# SMPS.net
KiCad netlist of a schematic drawn in Altium Designer
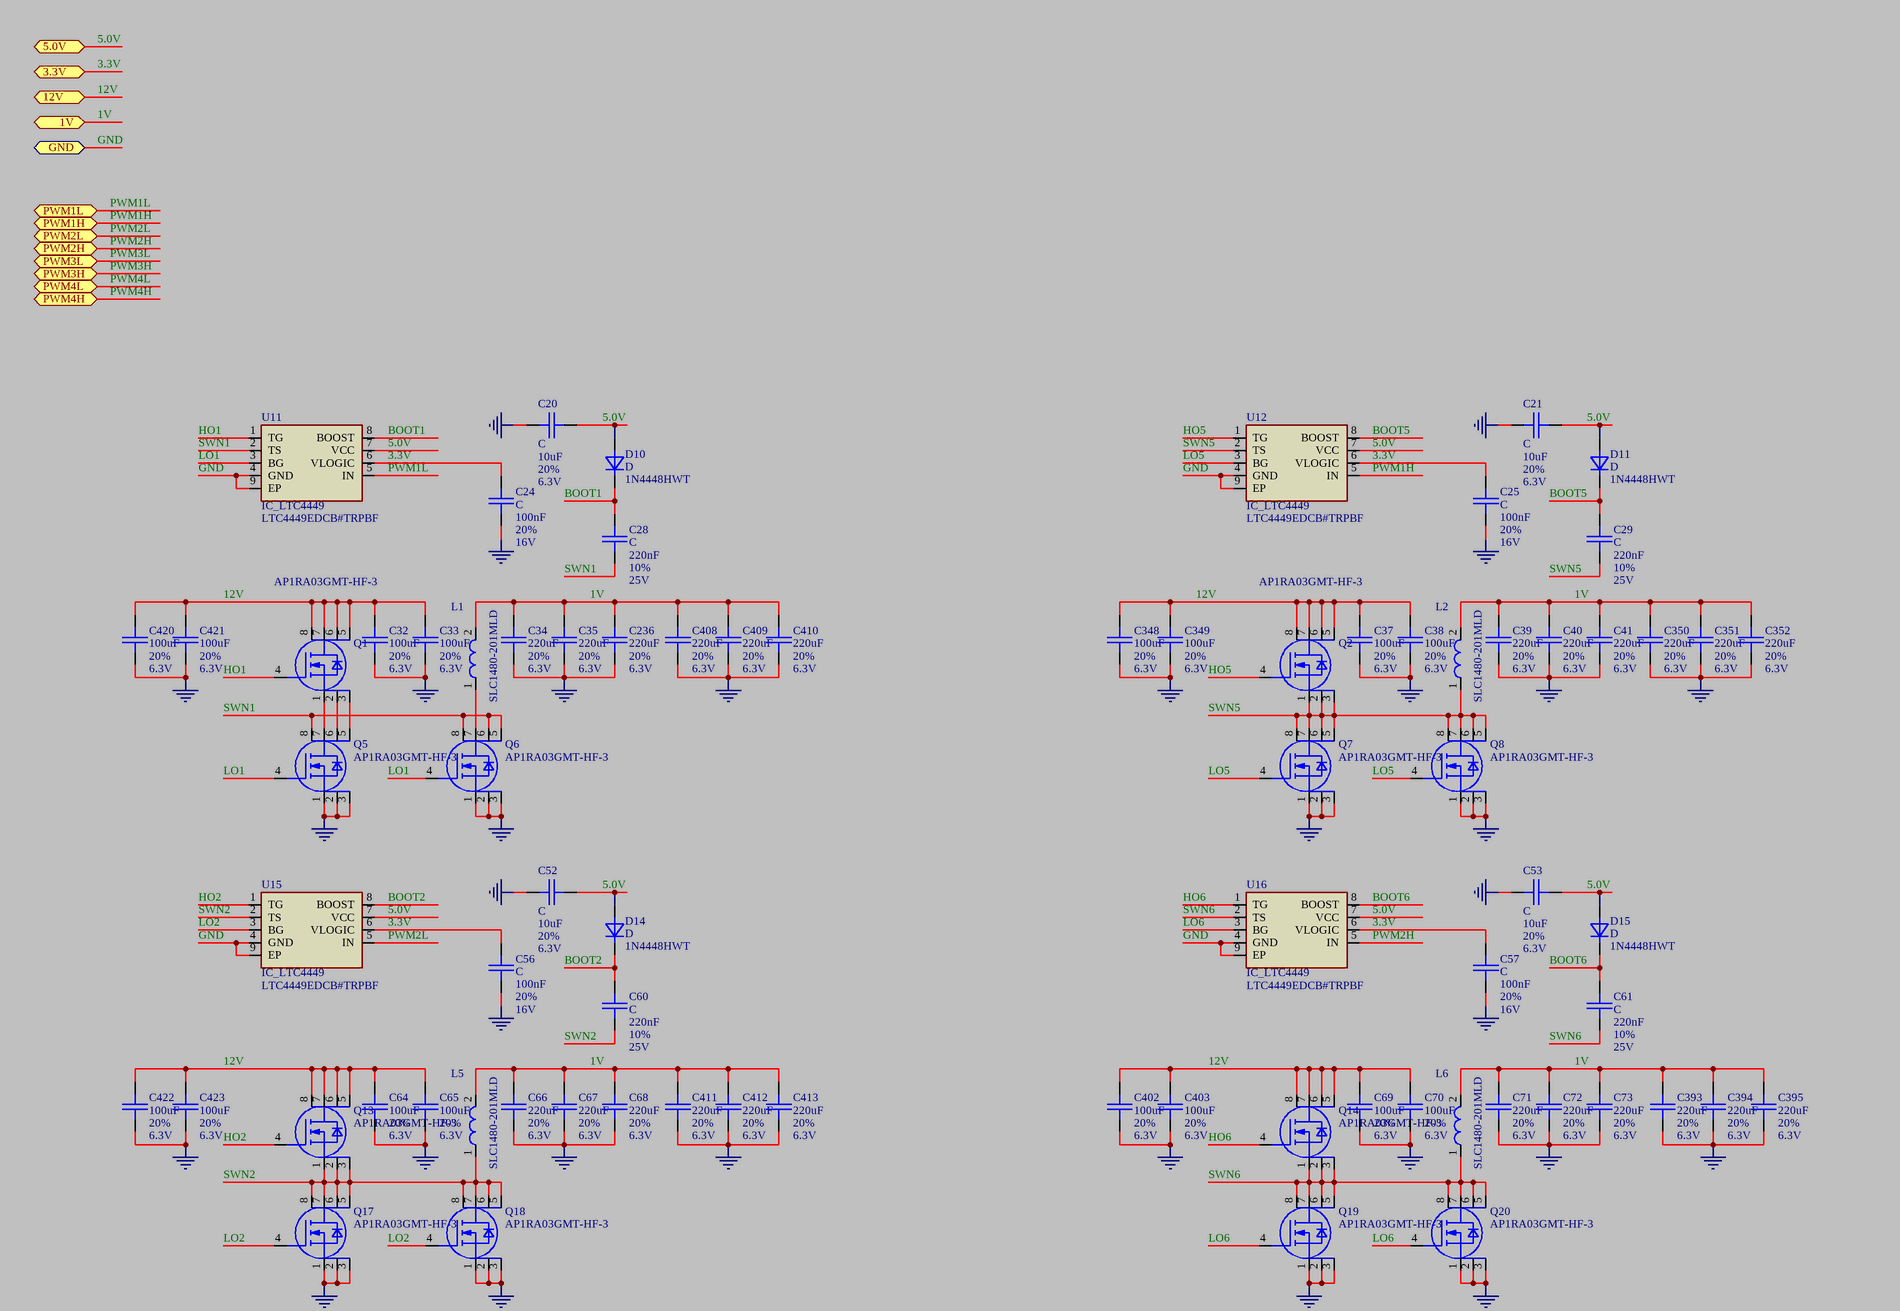
[diagram p0: SMPS.SchDoc, top left]
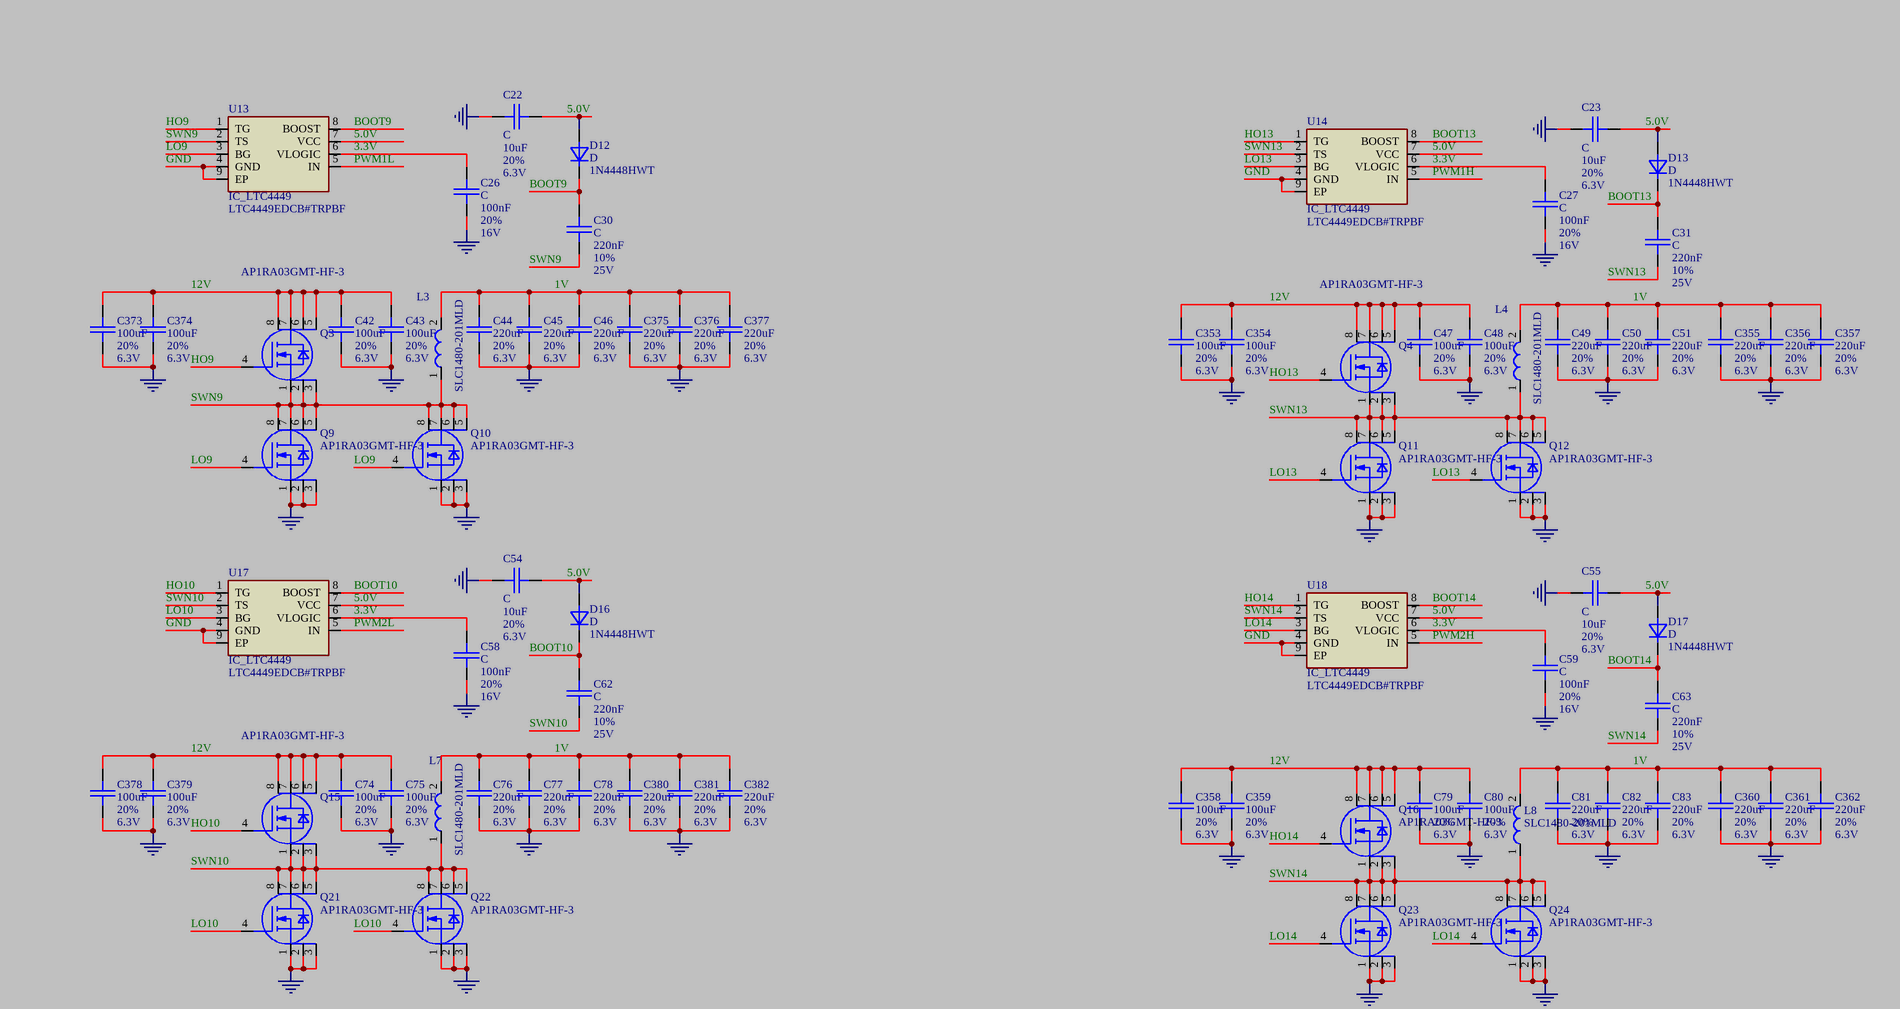
[diagram p1: SMPS.SchDoc, top right]
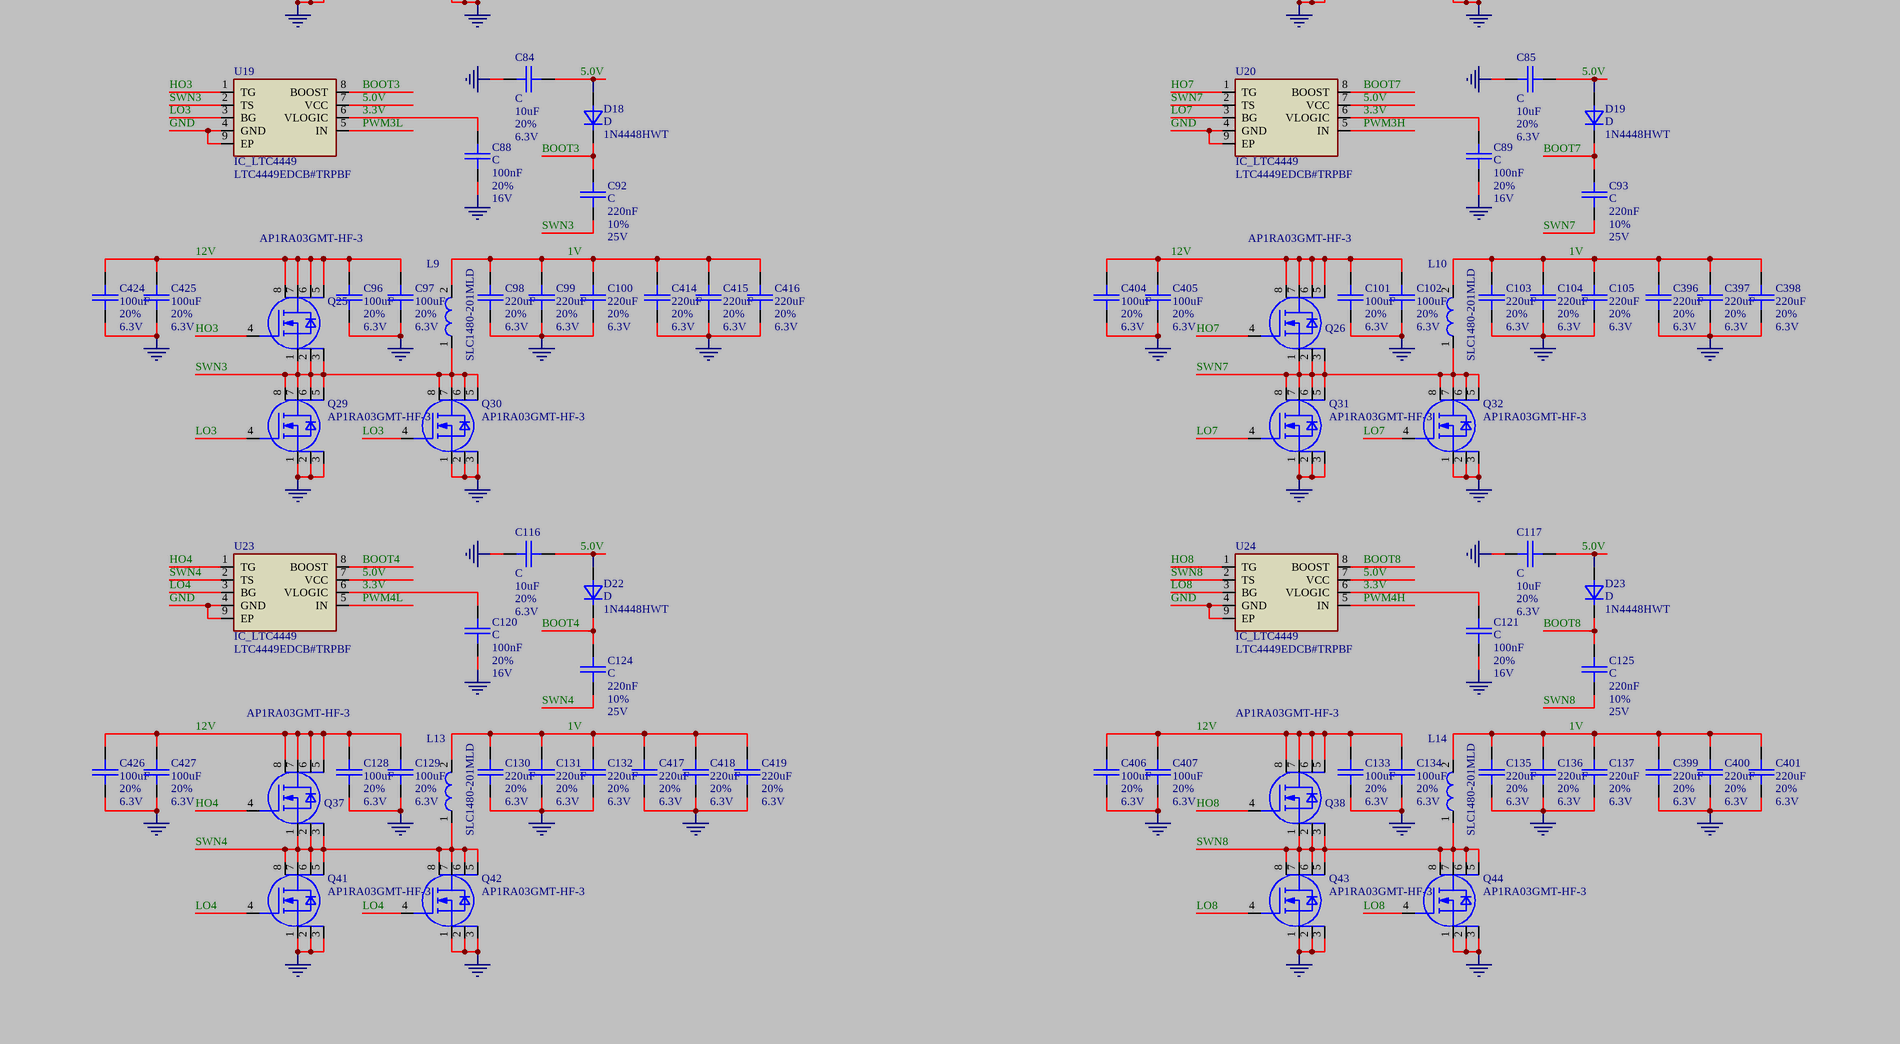
[diagram p2: SMPS.SchDoc, bottom left]
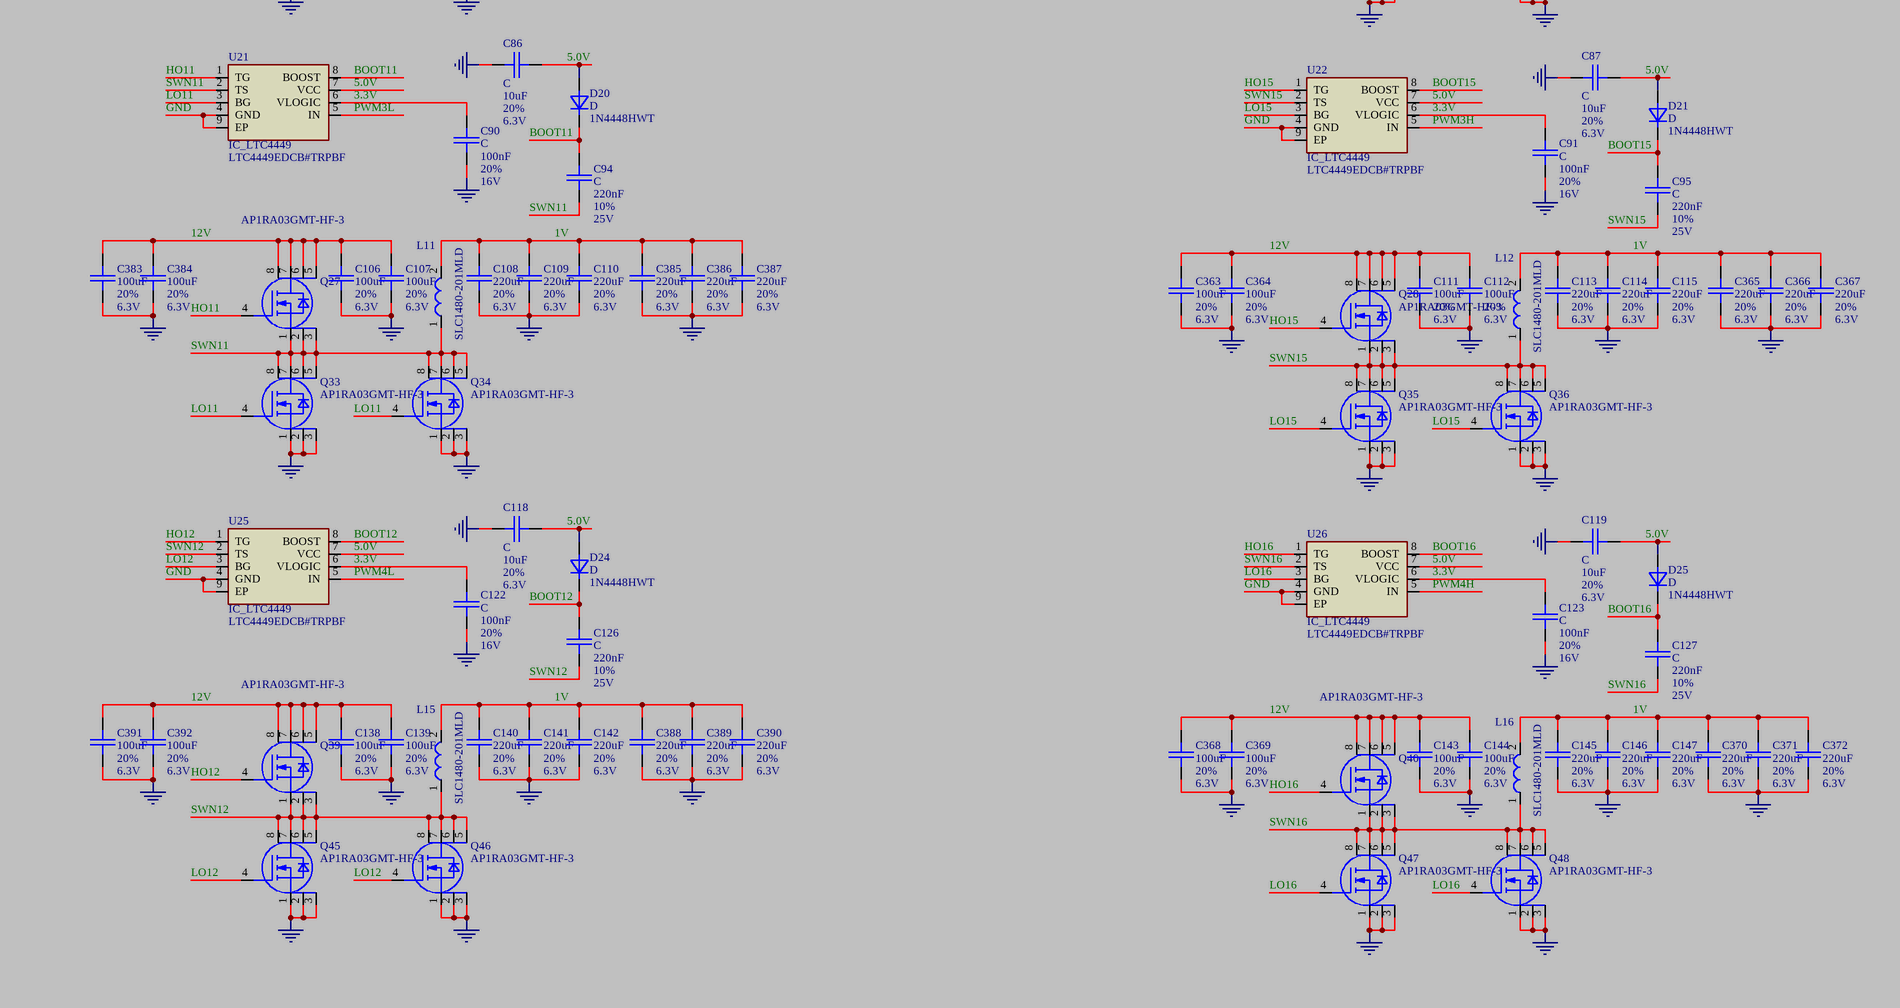
[diagram p3: SMPS.SchDoc, bottom right]

(export (version "E")
  (design (tool "Eeschema 10.0.6"))
  (components
    (comp (ref "C20")
      (value "C")
      (footprint "SMD_0603_CAPC1608X95N")
      (fields
        (field (name "DB_PART_NUMBER") "CAP000043646")
        (field (name "DB_VALUE") "10uF")
        (field (name "DB_TOLERANCE") "20%")
        (field (name "DB_VOLTAGE") "6.3V")
        (field (name "DB_MANUFACTURER_PART") "KEMET    C0603C106M9PAC")
      )
      (libsource (lib "Database_Libs1") (part "C"))
    )
    (comp (ref "C21")
      (value "C")
      (footprint "SMD_0603_CAPC1608X95N")
      (fields
        (field (name "DB_PART_NUMBER") "CAP000043646")
        (field (name "DB_VALUE") "10uF")
        (field (name "DB_TOLERANCE") "20%")
        (field (name "DB_VOLTAGE") "6.3V")
        (field (name "DB_MANUFACTURER_PART") "KEMET    C0603C106M9PAC")
      )
      (libsource (lib "Database_Libs1") (part "C"))
    )
    (comp (ref "C22")
      (value "C")
      (footprint "SMD_0603_CAPC1608X95N")
      (fields
        (field (name "DB_PART_NUMBER") "CAP000043646")
        (field (name "DB_VALUE") "10uF")
        (field (name "DB_TOLERANCE") "20%")
        (field (name "DB_VOLTAGE") "6.3V")
        (field (name "DB_MANUFACTURER_PART") "KEMET    C0603C106M9PAC")
      )
      (libsource (lib "Database_Libs1") (part "C"))
    )
    (comp (ref "C23")
      (value "C")
      (footprint "SMD_0603_CAPC1608X95N")
      (fields
        (field (name "DB_PART_NUMBER") "CAP000043646")
        (field (name "DB_VALUE") "10uF")
        (field (name "DB_TOLERANCE") "20%")
        (field (name "DB_VOLTAGE") "6.3V")
        (field (name "DB_MANUFACTURER_PART") "KEMET    C0603C106M9PAC")
      )
      (libsource (lib "Database_Libs1") (part "C"))
    )
    (comp (ref "C24")
      (value "C")
      (footprint "SMD_0402_CAPC1005X55N")
      (fields
        (field (name "DB_PART_NUMBER") "CAP000022751")
        (field (name "DB_VALUE") "100nF")
        (field (name "DB_TOLERANCE") "20%")
        (field (name "DB_VOLTAGE") "16V")
        (field (name "DB_MANUFACTURER_PART") "KEMET    C0402F104M4RAC")
      )
      (libsource (lib "Database_Libs1") (part "C"))
    )
    (comp (ref "C25")
      (value "C")
      (footprint "SMD_0402_CAPC1005X55N")
      (fields
        (field (name "DB_PART_NUMBER") "CAP000022751")
        (field (name "DB_VALUE") "100nF")
        (field (name "DB_TOLERANCE") "20%")
        (field (name "DB_VOLTAGE") "16V")
        (field (name "DB_MANUFACTURER_PART") "KEMET    C0402F104M4RAC")
      )
      (libsource (lib "Database_Libs1") (part "C"))
    )
    (comp (ref "C26")
      (value "C")
      (footprint "SMD_0402_CAPC1005X55N")
      (fields
        (field (name "DB_PART_NUMBER") "CAP000022751")
        (field (name "DB_VALUE") "100nF")
        (field (name "DB_TOLERANCE") "20%")
        (field (name "DB_VOLTAGE") "16V")
        (field (name "DB_MANUFACTURER_PART") "KEMET    C0402F104M4RAC")
      )
      (libsource (lib "Database_Libs1") (part "C"))
    )
    (comp (ref "C27")
      (value "C")
      (footprint "SMD_0402_CAPC1005X55N")
      (fields
        (field (name "DB_PART_NUMBER") "CAP000022751")
        (field (name "DB_VALUE") "100nF")
        (field (name "DB_TOLERANCE") "20%")
        (field (name "DB_VOLTAGE") "16V")
        (field (name "DB_MANUFACTURER_PART") "KEMET    C0402F104M4RAC")
      )
      (libsource (lib "Database_Libs1") (part "C"))
    )
    (comp (ref "C28")
      (value "C")
      (footprint "SMD_0603_CAPC1608X95N")
      (fields
        (field (name "DB_PART_NUMBER") "CAP000022968")
        (field (name "DB_VALUE") "220nF")
        (field (name "DB_TOLERANCE") "10%")
        (field (name "DB_VOLTAGE") "25V")
        (field (name "DB_MANUFACTURER_PART") "KEMET    C0603F224K3RAC")
      )
      (libsource (lib "Database_Libs1") (part "C"))
    )
    (comp (ref "C29")
      (value "C")
      (footprint "SMD_0603_CAPC1608X95N")
      (fields
        (field (name "DB_PART_NUMBER") "CAP000022968")
        (field (name "DB_VALUE") "220nF")
        (field (name "DB_TOLERANCE") "10%")
        (field (name "DB_VOLTAGE") "25V")
        (field (name "DB_MANUFACTURER_PART") "KEMET    C0603F224K3RAC")
      )
      (libsource (lib "Database_Libs1") (part "C"))
    )
    (comp (ref "C30")
      (value "C")
      (footprint "SMD_0603_CAPC1608X95N")
      (fields
        (field (name "DB_PART_NUMBER") "CAP000022968")
        (field (name "DB_VALUE") "220nF")
        (field (name "DB_TOLERANCE") "10%")
        (field (name "DB_VOLTAGE") "25V")
        (field (name "DB_MANUFACTURER_PART") "KEMET    C0603F224K3RAC")
      )
      (libsource (lib "Database_Libs1") (part "C"))
    )
    (comp (ref "C31")
      (value "C")
      (footprint "SMD_0603_CAPC1608X95N")
      (fields
        (field (name "DB_PART_NUMBER") "CAP000022968")
        (field (name "DB_VALUE") "220nF")
        (field (name "DB_TOLERANCE") "10%")
        (field (name "DB_VOLTAGE") "25V")
        (field (name "DB_MANUFACTURER_PART") "KEMET    C0603F224K3RAC")
      )
      (libsource (lib "Database_Libs1") (part "C"))
    )
    (comp (ref "C32")
      (value "C")
      (footprint "SMD_1210_CAPC3225X270N")
      (fields
        (field (name "DB_PART_NUMBER") "CAP000043701")
        (field (name "DB_VALUE") "100uF")
        (field (name "DB_TOLERANCE") "20%")
        (field (name "DB_VOLTAGE") "6.3V")
        (field (name "DB_MANUFACTURER_PART") "KEMET    C1210C107M9PAC")
      )
      (libsource (lib "Database_Libs1") (part "C"))
    )
    (comp (ref "C33")
      (value "C")
      (footprint "SMD_1210_CAPC3225X270N")
      (fields
        (field (name "DB_PART_NUMBER") "CAP000043701")
        (field (name "DB_VALUE") "100uF")
        (field (name "DB_TOLERANCE") "20%")
        (field (name "DB_VOLTAGE") "6.3V")
        (field (name "DB_MANUFACTURER_PART") "KEMET    C1210C107M9PAC")
      )
      (libsource (lib "Database_Libs1") (part "C"))
    )
    (comp (ref "C34")
      (value "C")
      (footprint "SMD_1210_CAPC3225X279N")
      (fields
        (field (name "DB_PART_NUMBER") "CAP000047355")
        (field (name "DB_VALUE") "220uF")
        (field (name "DB_TOLERANCE") "20%")
        (field (name "DB_VOLTAGE") "6.3V")
        (field (name "DB_MANUFACTURER_PART") "SAMSUNG    CL32A227MQVNNNE")
        (field (name "DB_APPROVED_BY") "VSN")
      )
      (libsource (lib "Database_Libs1") (part "C"))
    )
    (comp (ref "C35")
      (value "C")
      (footprint "SMD_1210_CAPC3225X279N")
      (fields
        (field (name "DB_PART_NUMBER") "CAP000047355")
        (field (name "DB_VALUE") "220uF")
        (field (name "DB_TOLERANCE") "20%")
        (field (name "DB_VOLTAGE") "6.3V")
        (field (name "DB_MANUFACTURER_PART") "SAMSUNG    CL32A227MQVNNNE")
        (field (name "DB_APPROVED_BY") "VSN")
      )
      (libsource (lib "Database_Libs1") (part "C"))
    )
    (comp (ref "C37")
      (value "C")
      (footprint "SMD_1210_CAPC3225X270N")
      (fields
        (field (name "DB_PART_NUMBER") "CAP000043701")
        (field (name "DB_VALUE") "100uF")
        (field (name "DB_TOLERANCE") "20%")
        (field (name "DB_VOLTAGE") "6.3V")
        (field (name "DB_MANUFACTURER_PART") "KEMET    C1210C107M9PAC")
      )
      (libsource (lib "Database_Libs1") (part "C"))
    )
    (comp (ref "C38")
      (value "C")
      (footprint "SMD_1210_CAPC3225X270N")
      (fields
        (field (name "DB_PART_NUMBER") "CAP000043701")
        (field (name "DB_VALUE") "100uF")
        (field (name "DB_TOLERANCE") "20%")
        (field (name "DB_VOLTAGE") "6.3V")
        (field (name "DB_MANUFACTURER_PART") "KEMET    C1210C107M9PAC")
      )
      (libsource (lib "Database_Libs1") (part "C"))
    )
    (comp (ref "C39")
      (value "C")
      (footprint "SMD_1210_CAPC3225X279N")
      (fields
        (field (name "DB_PART_NUMBER") "CAP000047355")
        (field (name "DB_VALUE") "220uF")
        (field (name "DB_TOLERANCE") "20%")
        (field (name "DB_VOLTAGE") "6.3V")
        (field (name "DB_MANUFACTURER_PART") "SAMSUNG    CL32A227MQVNNNE")
        (field (name "DB_APPROVED_BY") "VSN")
      )
      (libsource (lib "Database_Libs1") (part "C"))
    )
    (comp (ref "C40")
      (value "C")
      (footprint "SMD_1210_CAPC3225X279N")
      (fields
        (field (name "DB_PART_NUMBER") "CAP000047355")
        (field (name "DB_VALUE") "220uF")
        (field (name "DB_TOLERANCE") "20%")
        (field (name "DB_VOLTAGE") "6.3V")
        (field (name "DB_MANUFACTURER_PART") "SAMSUNG    CL32A227MQVNNNE")
        (field (name "DB_APPROVED_BY") "VSN")
      )
      (libsource (lib "Database_Libs1") (part "C"))
    )
    (comp (ref "C41")
      (value "C")
      (footprint "SMD_1210_CAPC3225X279N")
      (fields
        (field (name "DB_PART_NUMBER") "CAP000047355")
        (field (name "DB_VALUE") "220uF")
        (field (name "DB_TOLERANCE") "20%")
        (field (name "DB_VOLTAGE") "6.3V")
        (field (name "DB_MANUFACTURER_PART") "SAMSUNG    CL32A227MQVNNNE")
        (field (name "DB_APPROVED_BY") "VSN")
      )
      (libsource (lib "Database_Libs1") (part "C"))
    )
    (comp (ref "C42")
      (value "C")
      (footprint "SMD_1210_CAPC3225X270N")
      (fields
        (field (name "DB_PART_NUMBER") "CAP000043701")
        (field (name "DB_VALUE") "100uF")
        (field (name "DB_TOLERANCE") "20%")
        (field (name "DB_VOLTAGE") "6.3V")
        (field (name "DB_MANUFACTURER_PART") "KEMET    C1210C107M9PAC")
      )
      (libsource (lib "Database_Libs1") (part "C"))
    )
    (comp (ref "C43")
      (value "C")
      (footprint "SMD_1210_CAPC3225X270N")
      (fields
        (field (name "DB_PART_NUMBER") "CAP000043701")
        (field (name "DB_VALUE") "100uF")
        (field (name "DB_TOLERANCE") "20%")
        (field (name "DB_VOLTAGE") "6.3V")
        (field (name "DB_MANUFACTURER_PART") "KEMET    C1210C107M9PAC")
      )
      (libsource (lib "Database_Libs1") (part "C"))
    )
    (comp (ref "C44")
      (value "C")
      (footprint "SMD_1210_CAPC3225X279N")
      (fields
        (field (name "DB_PART_NUMBER") "CAP000047355")
        (field (name "DB_VALUE") "220uF")
        (field (name "DB_TOLERANCE") "20%")
        (field (name "DB_VOLTAGE") "6.3V")
        (field (name "DB_MANUFACTURER_PART") "SAMSUNG    CL32A227MQVNNNE")
        (field (name "DB_APPROVED_BY") "VSN")
      )
      (libsource (lib "Database_Libs1") (part "C"))
    )
    (comp (ref "C45")
      (value "C")
      (footprint "SMD_1210_CAPC3225X279N")
      (fields
        (field (name "DB_PART_NUMBER") "CAP000047355")
        (field (name "DB_VALUE") "220uF")
        (field (name "DB_TOLERANCE") "20%")
        (field (name "DB_VOLTAGE") "6.3V")
        (field (name "DB_MANUFACTURER_PART") "SAMSUNG    CL32A227MQVNNNE")
        (field (name "DB_APPROVED_BY") "VSN")
      )
      (libsource (lib "Database_Libs1") (part "C"))
    )
    (comp (ref "C46")
      (value "C")
      (footprint "SMD_1210_CAPC3225X279N")
      (fields
        (field (name "DB_PART_NUMBER") "CAP000047355")
        (field (name "DB_VALUE") "220uF")
        (field (name "DB_TOLERANCE") "20%")
        (field (name "DB_VOLTAGE") "6.3V")
        (field (name "DB_MANUFACTURER_PART") "SAMSUNG    CL32A227MQVNNNE")
        (field (name "DB_APPROVED_BY") "VSN")
      )
      (libsource (lib "Database_Libs1") (part "C"))
    )
    (comp (ref "C47")
      (value "C")
      (footprint "SMD_1210_CAPC3225X270N")
      (fields
        (field (name "DB_PART_NUMBER") "CAP000043701")
        (field (name "DB_VALUE") "100uF")
        (field (name "DB_TOLERANCE") "20%")
        (field (name "DB_VOLTAGE") "6.3V")
        (field (name "DB_MANUFACTURER_PART") "KEMET    C1210C107M9PAC")
      )
      (libsource (lib "Database_Libs1") (part "C"))
    )
    (comp (ref "C48")
      (value "C")
      (footprint "SMD_1210_CAPC3225X270N")
      (fields
        (field (name "DB_PART_NUMBER") "CAP000043701")
        (field (name "DB_VALUE") "100uF")
        (field (name "DB_TOLERANCE") "20%")
        (field (name "DB_VOLTAGE") "6.3V")
        (field (name "DB_MANUFACTURER_PART") "KEMET    C1210C107M9PAC")
      )
      (libsource (lib "Database_Libs1") (part "C"))
    )
    (comp (ref "C49")
      (value "C")
      (footprint "SMD_1210_CAPC3225X279N")
      (fields
        (field (name "DB_PART_NUMBER") "CAP000047355")
        (field (name "DB_VALUE") "220uF")
        (field (name "DB_TOLERANCE") "20%")
        (field (name "DB_VOLTAGE") "6.3V")
        (field (name "DB_MANUFACTURER_PART") "SAMSUNG    CL32A227MQVNNNE")
        (field (name "DB_APPROVED_BY") "VSN")
      )
      (libsource (lib "Database_Libs1") (part "C"))
    )
    (comp (ref "C50")
      (value "C")
      (footprint "SMD_1210_CAPC3225X279N")
      (fields
        (field (name "DB_PART_NUMBER") "CAP000047355")
        (field (name "DB_VALUE") "220uF")
        (field (name "DB_TOLERANCE") "20%")
        (field (name "DB_VOLTAGE") "6.3V")
        (field (name "DB_MANUFACTURER_PART") "SAMSUNG    CL32A227MQVNNNE")
        (field (name "DB_APPROVED_BY") "VSN")
      )
      (libsource (lib "Database_Libs1") (part "C"))
    )
    (comp (ref "C51")
      (value "C")
      (footprint "SMD_1210_CAPC3225X279N")
      (fields
        (field (name "DB_PART_NUMBER") "CAP000047355")
        (field (name "DB_VALUE") "220uF")
        (field (name "DB_TOLERANCE") "20%")
        (field (name "DB_VOLTAGE") "6.3V")
        (field (name "DB_MANUFACTURER_PART") "SAMSUNG    CL32A227MQVNNNE")
        (field (name "DB_APPROVED_BY") "VSN")
      )
      (libsource (lib "Database_Libs1") (part "C"))
    )
    (comp (ref "C52")
      (value "C")
      (footprint "SMD_0603_CAPC1608X95N")
      (fields
        (field (name "DB_PART_NUMBER") "CAP000043646")
        (field (name "DB_VALUE") "10uF")
        (field (name "DB_TOLERANCE") "20%")
        (field (name "DB_VOLTAGE") "6.3V")
        (field (name "DB_MANUFACTURER_PART") "KEMET    C0603C106M9PAC")
      )
      (libsource (lib "Database_Libs1") (part "C"))
    )
    (comp (ref "C53")
      (value "C")
      (footprint "SMD_0603_CAPC1608X95N")
      (fields
        (field (name "DB_PART_NUMBER") "CAP000043646")
        (field (name "DB_VALUE") "10uF")
        (field (name "DB_TOLERANCE") "20%")
        (field (name "DB_VOLTAGE") "6.3V")
        (field (name "DB_MANUFACTURER_PART") "KEMET    C0603C106M9PAC")
      )
      (libsource (lib "Database_Libs1") (part "C"))
    )
    (comp (ref "C54")
      (value "C")
      (footprint "SMD_0603_CAPC1608X95N")
      (fields
        (field (name "DB_PART_NUMBER") "CAP000043646")
        (field (name "DB_VALUE") "10uF")
        (field (name "DB_TOLERANCE") "20%")
        (field (name "DB_VOLTAGE") "6.3V")
        (field (name "DB_MANUFACTURER_PART") "KEMET    C0603C106M9PAC")
      )
      (libsource (lib "Database_Libs1") (part "C"))
    )
    (comp (ref "C55")
      (value "C")
      (footprint "SMD_0603_CAPC1608X95N")
      (fields
        (field (name "DB_PART_NUMBER") "CAP000043646")
        (field (name "DB_VALUE") "10uF")
        (field (name "DB_TOLERANCE") "20%")
        (field (name "DB_VOLTAGE") "6.3V")
        (field (name "DB_MANUFACTURER_PART") "KEMET    C0603C106M9PAC")
      )
      (libsource (lib "Database_Libs1") (part "C"))
    )
    (comp (ref "C56")
      (value "C")
      (footprint "SMD_0402_CAPC1005X55N")
      (fields
        (field (name "DB_PART_NUMBER") "CAP000022751")
        (field (name "DB_VALUE") "100nF")
        (field (name "DB_TOLERANCE") "20%")
        (field (name "DB_VOLTAGE") "16V")
        (field (name "DB_MANUFACTURER_PART") "KEMET    C0402F104M4RAC")
      )
      (libsource (lib "Database_Libs1") (part "C"))
    )
    (comp (ref "C57")
      (value "C")
      (footprint "SMD_0402_CAPC1005X55N")
      (fields
        (field (name "DB_PART_NUMBER") "CAP000022751")
        (field (name "DB_VALUE") "100nF")
        (field (name "DB_TOLERANCE") "20%")
        (field (name "DB_VOLTAGE") "16V")
        (field (name "DB_MANUFACTURER_PART") "KEMET    C0402F104M4RAC")
      )
      (libsource (lib "Database_Libs1") (part "C"))
    )
    (comp (ref "C58")
      (value "C")
      (footprint "SMD_0402_CAPC1005X55N")
      (fields
        (field (name "DB_PART_NUMBER") "CAP000022751")
        (field (name "DB_VALUE") "100nF")
        (field (name "DB_TOLERANCE") "20%")
        (field (name "DB_VOLTAGE") "16V")
        (field (name "DB_MANUFACTURER_PART") "KEMET    C0402F104M4RAC")
      )
      (libsource (lib "Database_Libs1") (part "C"))
    )
    (comp (ref "C59")
      (value "C")
      (footprint "SMD_0402_CAPC1005X55N")
      (fields
        (field (name "DB_PART_NUMBER") "CAP000022751")
        (field (name "DB_VALUE") "100nF")
        (field (name "DB_TOLERANCE") "20%")
        (field (name "DB_VOLTAGE") "16V")
        (field (name "DB_MANUFACTURER_PART") "KEMET    C0402F104M4RAC")
      )
      (libsource (lib "Database_Libs1") (part "C"))
    )
    (comp (ref "C60")
      (value "C")
      (footprint "SMD_0603_CAPC1608X95N")
      (fields
        (field (name "DB_PART_NUMBER") "CAP000022968")
        (field (name "DB_VALUE") "220nF")
        (field (name "DB_TOLERANCE") "10%")
        (field (name "DB_VOLTAGE") "25V")
        (field (name "DB_MANUFACTURER_PART") "KEMET    C0603F224K3RAC")
      )
      (libsource (lib "Database_Libs1") (part "C"))
    )
    (comp (ref "C61")
      (value "C")
      (footprint "SMD_0603_CAPC1608X95N")
      (fields
        (field (name "DB_PART_NUMBER") "CAP000022968")
        (field (name "DB_VALUE") "220nF")
        (field (name "DB_TOLERANCE") "10%")
        (field (name "DB_VOLTAGE") "25V")
        (field (name "DB_MANUFACTURER_PART") "KEMET    C0603F224K3RAC")
      )
      (libsource (lib "Database_Libs1") (part "C"))
    )
    (comp (ref "C62")
      (value "C")
      (footprint "SMD_0603_CAPC1608X95N")
      (fields
        (field (name "DB_PART_NUMBER") "CAP000022968")
        (field (name "DB_VALUE") "220nF")
        (field (name "DB_TOLERANCE") "10%")
        (field (name "DB_VOLTAGE") "25V")
        (field (name "DB_MANUFACTURER_PART") "KEMET    C0603F224K3RAC")
      )
      (libsource (lib "Database_Libs1") (part "C"))
    )
    (comp (ref "C63")
      (value "C")
      (footprint "SMD_0603_CAPC1608X95N")
      (fields
        (field (name "DB_PART_NUMBER") "CAP000022968")
        (field (name "DB_VALUE") "220nF")
        (field (name "DB_TOLERANCE") "10%")
        (field (name "DB_VOLTAGE") "25V")
        (field (name "DB_MANUFACTURER_PART") "KEMET    C0603F224K3RAC")
      )
      (libsource (lib "Database_Libs1") (part "C"))
    )
    (comp (ref "C64")
      (value "C")
      (footprint "SMD_1210_CAPC3225X270N")
      (fields
        (field (name "DB_PART_NUMBER") "CAP000043701")
        (field (name "DB_VALUE") "100uF")
        (field (name "DB_TOLERANCE") "20%")
        (field (name "DB_VOLTAGE") "6.3V")
        (field (name "DB_MANUFACTURER_PART") "KEMET    C1210C107M9PAC")
      )
      (libsource (lib "Database_Libs1") (part "C"))
    )
    (comp (ref "C65")
      (value "C")
      (footprint "SMD_1210_CAPC3225X270N")
      (fields
        (field (name "DB_PART_NUMBER") "CAP000043701")
        (field (name "DB_VALUE") "100uF")
        (field (name "DB_TOLERANCE") "20%")
        (field (name "DB_VOLTAGE") "6.3V")
        (field (name "DB_MANUFACTURER_PART") "KEMET    C1210C107M9PAC")
      )
      (libsource (lib "Database_Libs1") (part "C"))
    )
    (comp (ref "C66")
      (value "C")
      (footprint "SMD_1210_CAPC3225X279N")
      (fields
        (field (name "DB_PART_NUMBER") "CAP000047355")
        (field (name "DB_VALUE") "220uF")
        (field (name "DB_TOLERANCE") "20%")
        (field (name "DB_VOLTAGE") "6.3V")
        (field (name "DB_MANUFACTURER_PART") "SAMSUNG    CL32A227MQVNNNE")
        (field (name "DB_APPROVED_BY") "VSN")
      )
      (libsource (lib "Database_Libs1") (part "C"))
    )
    (comp (ref "C67")
      (value "C")
      (footprint "SMD_1210_CAPC3225X279N")
      (fields
        (field (name "DB_PART_NUMBER") "CAP000047355")
        (field (name "DB_VALUE") "220uF")
        (field (name "DB_TOLERANCE") "20%")
        (field (name "DB_VOLTAGE") "6.3V")
        (field (name "DB_MANUFACTURER_PART") "SAMSUNG    CL32A227MQVNNNE")
        (field (name "DB_APPROVED_BY") "VSN")
      )
      (libsource (lib "Database_Libs1") (part "C"))
    )
    (comp (ref "C68")
      (value "C")
      (footprint "SMD_1210_CAPC3225X279N")
      (fields
        (field (name "DB_PART_NUMBER") "CAP000047355")
        (field (name "DB_VALUE") "220uF")
        (field (name "DB_TOLERANCE") "20%")
        (field (name "DB_VOLTAGE") "6.3V")
        (field (name "DB_MANUFACTURER_PART") "SAMSUNG    CL32A227MQVNNNE")
        (field (name "DB_APPROVED_BY") "VSN")
      )
      (libsource (lib "Database_Libs1") (part "C"))
    )
    (comp (ref "C69")
      (value "C")
      (footprint "SMD_1210_CAPC3225X270N")
      (fields
        (field (name "DB_PART_NUMBER") "CAP000043701")
        (field (name "DB_VALUE") "100uF")
        (field (name "DB_TOLERANCE") "20%")
        (field (name "DB_VOLTAGE") "6.3V")
        (field (name "DB_MANUFACTURER_PART") "KEMET    C1210C107M9PAC")
      )
      (libsource (lib "Database_Libs1") (part "C"))
    )
    (comp (ref "C70")
      (value "C")
      (footprint "SMD_1210_CAPC3225X270N")
      (fields
        (field (name "DB_PART_NUMBER") "CAP000043701")
        (field (name "DB_VALUE") "100uF")
        (field (name "DB_TOLERANCE") "20%")
        (field (name "DB_VOLTAGE") "6.3V")
        (field (name "DB_MANUFACTURER_PART") "KEMET    C1210C107M9PAC")
      )
      (libsource (lib "Database_Libs1") (part "C"))
    )
    (comp (ref "C71")
      (value "C")
      (footprint "SMD_1210_CAPC3225X279N")
      (fields
        (field (name "DB_PART_NUMBER") "CAP000047355")
        (field (name "DB_VALUE") "220uF")
        (field (name "DB_TOLERANCE") "20%")
        (field (name "DB_VOLTAGE") "6.3V")
        (field (name "DB_MANUFACTURER_PART") "SAMSUNG    CL32A227MQVNNNE")
        (field (name "DB_APPROVED_BY") "VSN")
      )
      (libsource (lib "Database_Libs1") (part "C"))
    )
    (comp (ref "C72")
      (value "C")
      (footprint "SMD_1210_CAPC3225X279N")
      (fields
        (field (name "DB_PART_NUMBER") "CAP000047355")
        (field (name "DB_VALUE") "220uF")
        (field (name "DB_TOLERANCE") "20%")
        (field (name "DB_VOLTAGE") "6.3V")
        (field (name "DB_MANUFACTURER_PART") "SAMSUNG    CL32A227MQVNNNE")
        (field (name "DB_APPROVED_BY") "VSN")
      )
      (libsource (lib "Database_Libs1") (part "C"))
    )
    (comp (ref "C73")
      (value "C")
      (footprint "SMD_1210_CAPC3225X279N")
      (fields
        (field (name "DB_PART_NUMBER") "CAP000047355")
        (field (name "DB_VALUE") "220uF")
        (field (name "DB_TOLERANCE") "20%")
        (field (name "DB_VOLTAGE") "6.3V")
        (field (name "DB_MANUFACTURER_PART") "SAMSUNG    CL32A227MQVNNNE")
        (field (name "DB_APPROVED_BY") "VSN")
      )
      (libsource (lib "Database_Libs1") (part "C"))
    )
    (comp (ref "C74")
      (value "C")
      (footprint "SMD_1210_CAPC3225X270N")
      (fields
        (field (name "DB_PART_NUMBER") "CAP000043701")
        (field (name "DB_VALUE") "100uF")
        (field (name "DB_TOLERANCE") "20%")
        (field (name "DB_VOLTAGE") "6.3V")
        (field (name "DB_MANUFACTURER_PART") "KEMET    C1210C107M9PAC")
      )
      (libsource (lib "Database_Libs1") (part "C"))
    )
    (comp (ref "C75")
      (value "C")
      (footprint "SMD_1210_CAPC3225X270N")
      (fields
        (field (name "DB_PART_NUMBER") "CAP000043701")
        (field (name "DB_VALUE") "100uF")
        (field (name "DB_TOLERANCE") "20%")
        (field (name "DB_VOLTAGE") "6.3V")
        (field (name "DB_MANUFACTURER_PART") "KEMET    C1210C107M9PAC")
      )
      (libsource (lib "Database_Libs1") (part "C"))
    )
    (comp (ref "C76")
      (value "C")
      (footprint "SMD_1210_CAPC3225X279N")
      (fields
        (field (name "DB_PART_NUMBER") "CAP000047355")
        (field (name "DB_VALUE") "220uF")
        (field (name "DB_TOLERANCE") "20%")
        (field (name "DB_VOLTAGE") "6.3V")
        (field (name "DB_MANUFACTURER_PART") "SAMSUNG    CL32A227MQVNNNE")
        (field (name "DB_APPROVED_BY") "VSN")
      )
      (libsource (lib "Database_Libs1") (part "C"))
    )
    (comp (ref "C77")
      (value "C")
      (footprint "SMD_1210_CAPC3225X279N")
      (fields
        (field (name "DB_PART_NUMBER") "CAP000047355")
        (field (name "DB_VALUE") "220uF")
        (field (name "DB_TOLERANCE") "20%")
        (field (name "DB_VOLTAGE") "6.3V")
        (field (name "DB_MANUFACTURER_PART") "SAMSUNG    CL32A227MQVNNNE")
        (field (name "DB_APPROVED_BY") "VSN")
      )
      (libsource (lib "Database_Libs1") (part "C"))
    )
    (comp (ref "C78")
      (value "C")
      (footprint "SMD_1210_CAPC3225X279N")
      (fields
        (field (name "DB_PART_NUMBER") "CAP000047355")
        (field (name "DB_VALUE") "220uF")
        (field (name "DB_TOLERANCE") "20%")
        (field (name "DB_VOLTAGE") "6.3V")
        (field (name "DB_MANUFACTURER_PART") "SAMSUNG    CL32A227MQVNNNE")
        (field (name "DB_APPROVED_BY") "VSN")
      )
      (libsource (lib "Database_Libs1") (part "C"))
    )
    (comp (ref "C79")
      (value "C")
      (footprint "SMD_1210_CAPC3225X270N")
      (fields
        (field (name "DB_PART_NUMBER") "CAP000043701")
        (field (name "DB_VALUE") "100uF")
        (field (name "DB_TOLERANCE") "20%")
        (field (name "DB_VOLTAGE") "6.3V")
        (field (name "DB_MANUFACTURER_PART") "KEMET    C1210C107M9PAC")
      )
      (libsource (lib "Database_Libs1") (part "C"))
    )
    (comp (ref "C80")
      (value "C")
      (footprint "SMD_1210_CAPC3225X270N")
      (fields
        (field (name "DB_PART_NUMBER") "CAP000043701")
        (field (name "DB_VALUE") "100uF")
        (field (name "DB_TOLERANCE") "20%")
        (field (name "DB_VOLTAGE") "6.3V")
        (field (name "DB_MANUFACTURER_PART") "KEMET    C1210C107M9PAC")
      )
      (libsource (lib "Database_Libs1") (part "C"))
    )
    (comp (ref "C81")
      (value "C")
      (footprint "SMD_1210_CAPC3225X279N")
      (fields
        (field (name "DB_PART_NUMBER") "CAP000047355")
        (field (name "DB_VALUE") "220uF")
        (field (name "DB_TOLERANCE") "20%")
        (field (name "DB_VOLTAGE") "6.3V")
        (field (name "DB_MANUFACTURER_PART") "SAMSUNG    CL32A227MQVNNNE")
        (field (name "DB_APPROVED_BY") "VSN")
      )
      (libsource (lib "Database_Libs1") (part "C"))
    )
    (comp (ref "C82")
      (value "C")
      (footprint "SMD_1210_CAPC3225X279N")
      (fields
        (field (name "DB_PART_NUMBER") "CAP000047355")
        (field (name "DB_VALUE") "220uF")
        (field (name "DB_TOLERANCE") "20%")
        (field (name "DB_VOLTAGE") "6.3V")
        (field (name "DB_MANUFACTURER_PART") "SAMSUNG    CL32A227MQVNNNE")
        (field (name "DB_APPROVED_BY") "VSN")
      )
      (libsource (lib "Database_Libs1") (part "C"))
    )
    (comp (ref "C83")
      (value "C")
      (footprint "SMD_1210_CAPC3225X279N")
      (fields
        (field (name "DB_PART_NUMBER") "CAP000047355")
        (field (name "DB_VALUE") "220uF")
        (field (name "DB_TOLERANCE") "20%")
        (field (name "DB_VOLTAGE") "6.3V")
        (field (name "DB_MANUFACTURER_PART") "SAMSUNG    CL32A227MQVNNNE")
        (field (name "DB_APPROVED_BY") "VSN")
      )
      (libsource (lib "Database_Libs1") (part "C"))
    )
    (comp (ref "C84")
      (value "C")
      (footprint "SMD_0603_CAPC1608X95N")
      (fields
        (field (name "DB_PART_NUMBER") "CAP000043646")
        (field (name "DB_VALUE") "10uF")
        (field (name "DB_TOLERANCE") "20%")
        (field (name "DB_VOLTAGE") "6.3V")
        (field (name "DB_MANUFACTURER_PART") "KEMET    C0603C106M9PAC")
      )
      (libsource (lib "Database_Libs1") (part "C"))
    )
    (comp (ref "C85")
      (value "C")
      (footprint "SMD_0603_CAPC1608X95N")
      (fields
        (field (name "DB_PART_NUMBER") "CAP000043646")
        (field (name "DB_VALUE") "10uF")
        (field (name "DB_TOLERANCE") "20%")
        (field (name "DB_VOLTAGE") "6.3V")
        (field (name "DB_MANUFACTURER_PART") "KEMET    C0603C106M9PAC")
      )
      (libsource (lib "Database_Libs1") (part "C"))
    )
    (comp (ref "C86")
      (value "C")
      (footprint "SMD_0603_CAPC1608X95N")
      (fields
        (field (name "DB_PART_NUMBER") "CAP000043646")
        (field (name "DB_VALUE") "10uF")
        (field (name "DB_TOLERANCE") "20%")
        (field (name "DB_VOLTAGE") "6.3V")
        (field (name "DB_MANUFACTURER_PART") "KEMET    C0603C106M9PAC")
      )
      (libsource (lib "Database_Libs1") (part "C"))
    )
    (comp (ref "C87")
      (value "C")
      (footprint "SMD_0603_CAPC1608X95N")
      (fields
        (field (name "DB_PART_NUMBER") "CAP000043646")
        (field (name "DB_VALUE") "10uF")
        (field (name "DB_TOLERANCE") "20%")
        (field (name "DB_VOLTAGE") "6.3V")
        (field (name "DB_MANUFACTURER_PART") "KEMET    C0603C106M9PAC")
      )
      (libsource (lib "Database_Libs1") (part "C"))
    )
    (comp (ref "C88")
      (value "C")
      (footprint "SMD_0402_CAPC1005X55N")
      (fields
        (field (name "DB_PART_NUMBER") "CAP000022751")
        (field (name "DB_VALUE") "100nF")
        (field (name "DB_TOLERANCE") "20%")
        (field (name "DB_VOLTAGE") "16V")
        (field (name "DB_MANUFACTURER_PART") "KEMET    C0402F104M4RAC")
      )
      (libsource (lib "Database_Libs1") (part "C"))
    )
    (comp (ref "C89")
      (value "C")
      (footprint "SMD_0402_CAPC1005X55N")
      (fields
        (field (name "DB_PART_NUMBER") "CAP000022751")
        (field (name "DB_VALUE") "100nF")
        (field (name "DB_TOLERANCE") "20%")
        (field (name "DB_VOLTAGE") "16V")
        (field (name "DB_MANUFACTURER_PART") "KEMET    C0402F104M4RAC")
      )
      (libsource (lib "Database_Libs1") (part "C"))
    )
    (comp (ref "C90")
      (value "C")
      (footprint "SMD_0402_CAPC1005X55N")
      (fields
        (field (name "DB_PART_NUMBER") "CAP000022751")
        (field (name "DB_VALUE") "100nF")
        (field (name "DB_TOLERANCE") "20%")
        (field (name "DB_VOLTAGE") "16V")
        (field (name "DB_MANUFACTURER_PART") "KEMET    C0402F104M4RAC")
      )
      (libsource (lib "Database_Libs1") (part "C"))
    )
    (comp (ref "C91")
      (value "C")
      (footprint "SMD_0402_CAPC1005X55N")
      (fields
        (field (name "DB_PART_NUMBER") "CAP000022751")
        (field (name "DB_VALUE") "100nF")
        (field (name "DB_TOLERANCE") "20%")
        (field (name "DB_VOLTAGE") "16V")
        (field (name "DB_MANUFACTURER_PART") "KEMET    C0402F104M4RAC")
      )
      (libsource (lib "Database_Libs1") (part "C"))
    )
    (comp (ref "C92")
      (value "C")
      (footprint "SMD_0603_CAPC1608X95N")
      (fields
        (field (name "DB_PART_NUMBER") "CAP000022968")
        (field (name "DB_VALUE") "220nF")
        (field (name "DB_TOLERANCE") "10%")
        (field (name "DB_VOLTAGE") "25V")
        (field (name "DB_MANUFACTURER_PART") "KEMET    C0603F224K3RAC")
      )
      (libsource (lib "Database_Libs1") (part "C"))
    )
    (comp (ref "C93")
      (value "C")
      (footprint "SMD_0603_CAPC1608X95N")
      (fields
        (field (name "DB_PART_NUMBER") "CAP000022968")
        (field (name "DB_VALUE") "220nF")
        (field (name "DB_TOLERANCE") "10%")
        (field (name "DB_VOLTAGE") "25V")
        (field (name "DB_MANUFACTURER_PART") "KEMET    C0603F224K3RAC")
      )
      (libsource (lib "Database_Libs1") (part "C"))
    )
    (comp (ref "C94")
      (value "C")
      (footprint "SMD_0603_CAPC1608X95N")
      (fields
        (field (name "DB_PART_NUMBER") "CAP000022968")
        (field (name "DB_VALUE") "220nF")
        (field (name "DB_TOLERANCE") "10%")
        (field (name "DB_VOLTAGE") "25V")
        (field (name "DB_MANUFACTURER_PART") "KEMET    C0603F224K3RAC")
      )
      (libsource (lib "Database_Libs1") (part "C"))
    )
    (comp (ref "C95")
      (value "C")
      (footprint "SMD_0603_CAPC1608X95N")
      (fields
        (field (name "DB_PART_NUMBER") "CAP000022968")
        (field (name "DB_VALUE") "220nF")
        (field (name "DB_TOLERANCE") "10%")
        (field (name "DB_VOLTAGE") "25V")
        (field (name "DB_MANUFACTURER_PART") "KEMET    C0603F224K3RAC")
      )
      (libsource (lib "Database_Libs1") (part "C"))
    )
    (comp (ref "C96")
      (value "C")
      (footprint "SMD_1210_CAPC3225X270N")
      (fields
        (field (name "DB_PART_NUMBER") "CAP000043701")
        (field (name "DB_VALUE") "100uF")
        (field (name "DB_TOLERANCE") "20%")
        (field (name "DB_VOLTAGE") "6.3V")
        (field (name "DB_MANUFACTURER_PART") "KEMET    C1210C107M9PAC")
      )
      (libsource (lib "Database_Libs1") (part "C"))
    )
    (comp (ref "C97")
      (value "C")
      (footprint "SMD_1210_CAPC3225X270N")
      (fields
        (field (name "DB_PART_NUMBER") "CAP000043701")
        (field (name "DB_VALUE") "100uF")
        (field (name "DB_TOLERANCE") "20%")
        (field (name "DB_VOLTAGE") "6.3V")
        (field (name "DB_MANUFACTURER_PART") "KEMET    C1210C107M9PAC")
      )
      (libsource (lib "Database_Libs1") (part "C"))
    )
    (comp (ref "C98")
      (value "C")
      (footprint "SMD_1210_CAPC3225X279N")
      (fields
        (field (name "DB_PART_NUMBER") "CAP000047355")
        (field (name "DB_VALUE") "220uF")
        (field (name "DB_TOLERANCE") "20%")
        (field (name "DB_VOLTAGE") "6.3V")
        (field (name "DB_MANUFACTURER_PART") "SAMSUNG    CL32A227MQVNNNE")
        (field (name "DB_APPROVED_BY") "VSN")
      )
      (libsource (lib "Database_Libs1") (part "C"))
    )
    (comp (ref "C99")
      (value "C")
      (footprint "SMD_1210_CAPC3225X279N")
      (fields
        (field (name "DB_PART_NUMBER") "CAP000047355")
        (field (name "DB_VALUE") "220uF")
        (field (name "DB_TOLERANCE") "20%")
        (field (name "DB_VOLTAGE") "6.3V")
        (field (name "DB_MANUFACTURER_PART") "SAMSUNG    CL32A227MQVNNNE")
        (field (name "DB_APPROVED_BY") "VSN")
      )
      (libsource (lib "Database_Libs1") (part "C"))
    )
    (comp (ref "C100")
      (value "C")
      (footprint "SMD_1210_CAPC3225X279N")
      (fields
        (field (name "DB_PART_NUMBER") "CAP000047355")
        (field (name "DB_VALUE") "220uF")
        (field (name "DB_TOLERANCE") "20%")
        (field (name "DB_VOLTAGE") "6.3V")
        (field (name "DB_MANUFACTURER_PART") "SAMSUNG    CL32A227MQVNNNE")
        (field (name "DB_APPROVED_BY") "VSN")
      )
      (libsource (lib "Database_Libs1") (part "C"))
    )
    (comp (ref "C101")
      (value "C")
      (footprint "SMD_1210_CAPC3225X270N")
      (fields
        (field (name "DB_PART_NUMBER") "CAP000043701")
        (field (name "DB_VALUE") "100uF")
        (field (name "DB_TOLERANCE") "20%")
        (field (name "DB_VOLTAGE") "6.3V")
        (field (name "DB_MANUFACTURER_PART") "KEMET    C1210C107M9PAC")
      )
      (libsource (lib "Database_Libs1") (part "C"))
    )
    (comp (ref "C102")
      (value "C")
      (footprint "SMD_1210_CAPC3225X270N")
      (fields
        (field (name "DB_PART_NUMBER") "CAP000043701")
        (field (name "DB_VALUE") "100uF")
        (field (name "DB_TOLERANCE") "20%")
        (field (name "DB_VOLTAGE") "6.3V")
        (field (name "DB_MANUFACTURER_PART") "KEMET    C1210C107M9PAC")
      )
      (libsource (lib "Database_Libs1") (part "C"))
    )
    (comp (ref "C103")
      (value "C")
      (footprint "SMD_1210_CAPC3225X279N")
      (fields
        (field (name "DB_PART_NUMBER") "CAP000047355")
        (field (name "DB_VALUE") "220uF")
        (field (name "DB_TOLERANCE") "20%")
        (field (name "DB_VOLTAGE") "6.3V")
        (field (name "DB_MANUFACTURER_PART") "SAMSUNG    CL32A227MQVNNNE")
        (field (name "DB_APPROVED_BY") "VSN")
      )
      (libsource (lib "Database_Libs1") (part "C"))
    )
    (comp (ref "C104")
      (value "C")
      (footprint "SMD_1210_CAPC3225X279N")
      (fields
        (field (name "DB_PART_NUMBER") "CAP000047355")
        (field (name "DB_VALUE") "220uF")
        (field (name "DB_TOLERANCE") "20%")
        (field (name "DB_VOLTAGE") "6.3V")
        (field (name "DB_MANUFACTURER_PART") "SAMSUNG    CL32A227MQVNNNE")
        (field (name "DB_APPROVED_BY") "VSN")
      )
      (libsource (lib "Database_Libs1") (part "C"))
    )
    (comp (ref "C105")
      (value "C")
      (footprint "SMD_1210_CAPC3225X279N")
      (fields
        (field (name "DB_PART_NUMBER") "CAP000047355")
        (field (name "DB_VALUE") "220uF")
        (field (name "DB_TOLERANCE") "20%")
        (field (name "DB_VOLTAGE") "6.3V")
        (field (name "DB_MANUFACTURER_PART") "SAMSUNG    CL32A227MQVNNNE")
        (field (name "DB_APPROVED_BY") "VSN")
      )
      (libsource (lib "Database_Libs1") (part "C"))
    )
    (comp (ref "C106")
      (value "C")
      (footprint "SMD_1210_CAPC3225X270N")
      (fields
        (field (name "DB_PART_NUMBER") "CAP000043701")
        (field (name "DB_VALUE") "100uF")
        (field (name "DB_TOLERANCE") "20%")
        (field (name "DB_VOLTAGE") "6.3V")
        (field (name "DB_MANUFACTURER_PART") "KEMET    C1210C107M9PAC")
      )
      (libsource (lib "Database_Libs1") (part "C"))
    )
    (comp (ref "C107")
      (value "C")
      (footprint "SMD_1210_CAPC3225X270N")
      (fields
        (field (name "DB_PART_NUMBER") "CAP000043701")
        (field (name "DB_VALUE") "100uF")
        (field (name "DB_TOLERANCE") "20%")
        (field (name "DB_VOLTAGE") "6.3V")
        (field (name "DB_MANUFACTURER_PART") "KEMET    C1210C107M9PAC")
      )
      (libsource (lib "Database_Libs1") (part "C"))
    )
    (comp (ref "C108")
      (value "C")
      (footprint "SMD_1210_CAPC3225X279N")
      (fields
        (field (name "DB_PART_NUMBER") "CAP000047355")
        (field (name "DB_VALUE") "220uF")
        (field (name "DB_TOLERANCE") "20%")
        (field (name "DB_VOLTAGE") "6.3V")
        (field (name "DB_MANUFACTURER_PART") "SAMSUNG    CL32A227MQVNNNE")
        (field (name "DB_APPROVED_BY") "VSN")
      )
      (libsource (lib "Database_Libs1") (part "C"))
    )
    (comp (ref "C109")
      (value "C")
      (footprint "SMD_1210_CAPC3225X279N")
      (fields
        (field (name "DB_PART_NUMBER") "CAP000047355")
        (field (name "DB_VALUE") "220uF")
        (field (name "DB_TOLERANCE") "20%")
        (field (name "DB_VOLTAGE") "6.3V")
        (field (name "DB_MANUFACTURER_PART") "SAMSUNG    CL32A227MQVNNNE")
        (field (name "DB_APPROVED_BY") "VSN")
      )
      (libsource (lib "Database_Libs1") (part "C"))
    )
    (comp (ref "C110")
      (value "C")
      (footprint "SMD_1210_CAPC3225X279N")
      (fields
        (field (name "DB_PART_NUMBER") "CAP000047355")
        (field (name "DB_VALUE") "220uF")
        (field (name "DB_TOLERANCE") "20%")
        (field (name "DB_VOLTAGE") "6.3V")
        (field (name "DB_MANUFACTURER_PART") "SAMSUNG    CL32A227MQVNNNE")
        (field (name "DB_APPROVED_BY") "VSN")
      )
      (libsource (lib "Database_Libs1") (part "C"))
    )
    (comp (ref "C111")
      (value "C")
      (footprint "SMD_1210_CAPC3225X270N")
      (fields
        (field (name "DB_PART_NUMBER") "CAP000043701")
        (field (name "DB_VALUE") "100uF")
        (field (name "DB_TOLERANCE") "20%")
        (field (name "DB_VOLTAGE") "6.3V")
        (field (name "DB_MANUFACTURER_PART") "KEMET    C1210C107M9PAC")
      )
      (libsource (lib "Database_Libs1") (part "C"))
    )
    (comp (ref "C112")
      (value "C")
      (footprint "SMD_1210_CAPC3225X270N")
      (fields
        (field (name "DB_PART_NUMBER") "CAP000043701")
        (field (name "DB_VALUE") "100uF")
        (field (name "DB_TOLERANCE") "20%")
        (field (name "DB_VOLTAGE") "6.3V")
        (field (name "DB_MANUFACTURER_PART") "KEMET    C1210C107M9PAC")
      )
      (libsource (lib "Database_Libs1") (part "C"))
    )
    (comp (ref "C113")
      (value "C")
      (footprint "SMD_1210_CAPC3225X279N")
      (fields
        (field (name "DB_PART_NUMBER") "CAP000047355")
        (field (name "DB_VALUE") "220uF")
        (field (name "DB_TOLERANCE") "20%")
        (field (name "DB_VOLTAGE") "6.3V")
        (field (name "DB_MANUFACTURER_PART") "SAMSUNG    CL32A227MQVNNNE")
        (field (name "DB_APPROVED_BY") "VSN")
      )
      (libsource (lib "Database_Libs1") (part "C"))
    )
    (comp (ref "C114")
      (value "C")
      (footprint "SMD_1210_CAPC3225X279N")
      (fields
        (field (name "DB_PART_NUMBER") "CAP000047355")
        (field (name "DB_VALUE") "220uF")
        (field (name "DB_TOLERANCE") "20%")
        (field (name "DB_VOLTAGE") "6.3V")
        (field (name "DB_MANUFACTURER_PART") "SAMSUNG    CL32A227MQVNNNE")
        (field (name "DB_APPROVED_BY") "VSN")
      )
      (libsource (lib "Database_Libs1") (part "C"))
    )
    (comp (ref "C115")
      (value "C")
      (footprint "SMD_1210_CAPC3225X279N")
      (fields
        (field (name "DB_PART_NUMBER") "CAP000047355")
        (field (name "DB_VALUE") "220uF")
        (field (name "DB_TOLERANCE") "20%")
        (field (name "DB_VOLTAGE") "6.3V")
        (field (name "DB_MANUFACTURER_PART") "SAMSUNG    CL32A227MQVNNNE")
        (field (name "DB_APPROVED_BY") "VSN")
      )
      (libsource (lib "Database_Libs1") (part "C"))
    )
    (comp (ref "C116")
      (value "C")
      (footprint "SMD_0603_CAPC1608X95N")
      (fields
        (field (name "DB_PART_NUMBER") "CAP000043646")
        (field (name "DB_VALUE") "10uF")
        (field (name "DB_TOLERANCE") "20%")
        (field (name "DB_VOLTAGE") "6.3V")
        (field (name "DB_MANUFACTURER_PART") "KEMET    C0603C106M9PAC")
      )
      (libsource (lib "Database_Libs1") (part "C"))
    )
    (comp (ref "C117")
      (value "C")
      (footprint "SMD_0603_CAPC1608X95N")
      (fields
        (field (name "DB_PART_NUMBER") "CAP000043646")
        (field (name "DB_VALUE") "10uF")
        (field (name "DB_TOLERANCE") "20%")
        (field (name "DB_VOLTAGE") "6.3V")
        (field (name "DB_MANUFACTURER_PART") "KEMET    C0603C106M9PAC")
      )
      (libsource (lib "Database_Libs1") (part "C"))
    )
    (comp (ref "C118")
      (value "C")
      (footprint "SMD_0603_CAPC1608X95N")
      (fields
        (field (name "DB_PART_NUMBER") "CAP000043646")
        (field (name "DB_VALUE") "10uF")
        (field (name "DB_TOLERANCE") "20%")
        (field (name "DB_VOLTAGE") "6.3V")
        (field (name "DB_MANUFACTURER_PART") "KEMET    C0603C106M9PAC")
      )
      (libsource (lib "Database_Libs1") (part "C"))
    )
    (comp (ref "C119")
      (value "C")
      (footprint "SMD_0603_CAPC1608X95N")
      (fields
        (field (name "DB_PART_NUMBER") "CAP000043646")
        (field (name "DB_VALUE") "10uF")
        (field (name "DB_TOLERANCE") "20%")
        (field (name "DB_VOLTAGE") "6.3V")
        (field (name "DB_MANUFACTURER_PART") "KEMET    C0603C106M9PAC")
      )
      (libsource (lib "Database_Libs1") (part "C"))
    )
    (comp (ref "C120")
      (value "C")
      (footprint "SMD_0402_CAPC1005X55N")
      (fields
        (field (name "DB_PART_NUMBER") "CAP000022751")
        (field (name "DB_VALUE") "100nF")
        (field (name "DB_TOLERANCE") "20%")
        (field (name "DB_VOLTAGE") "16V")
        (field (name "DB_MANUFACTURER_PART") "KEMET    C0402F104M4RAC")
      )
      (libsource (lib "Database_Libs1") (part "C"))
    )
    (comp (ref "C121")
      (value "C")
      (footprint "SMD_0402_CAPC1005X55N")
      (fields
        (field (name "DB_PART_NUMBER") "CAP000022751")
        (field (name "DB_VALUE") "100nF")
        (field (name "DB_TOLERANCE") "20%")
        (field (name "DB_VOLTAGE") "16V")
        (field (name "DB_MANUFACTURER_PART") "KEMET    C0402F104M4RAC")
      )
      (libsource (lib "Database_Libs1") (part "C"))
    )
    (comp (ref "C122")
      (value "C")
      (footprint "SMD_0402_CAPC1005X55N")
      (fields
        (field (name "DB_PART_NUMBER") "CAP000022751")
        (field (name "DB_VALUE") "100nF")
        (field (name "DB_TOLERANCE") "20%")
        (field (name "DB_VOLTAGE") "16V")
        (field (name "DB_MANUFACTURER_PART") "KEMET    C0402F104M4RAC")
      )
      (libsource (lib "Database_Libs1") (part "C"))
    )
    (comp (ref "C123")
      (value "C")
      (footprint "SMD_0402_CAPC1005X55N")
      (fields
        (field (name "DB_PART_NUMBER") "CAP000022751")
        (field (name "DB_VALUE") "100nF")
        (field (name "DB_TOLERANCE") "20%")
        (field (name "DB_VOLTAGE") "16V")
        (field (name "DB_MANUFACTURER_PART") "KEMET    C0402F104M4RAC")
      )
      (libsource (lib "Database_Libs1") (part "C"))
    )
    (comp (ref "C124")
      (value "C")
      (footprint "SMD_0603_CAPC1608X95N")
      (fields
        (field (name "DB_PART_NUMBER") "CAP000022968")
        (field (name "DB_VALUE") "220nF")
        (field (name "DB_TOLERANCE") "10%")
        (field (name "DB_VOLTAGE") "25V")
        (field (name "DB_MANUFACTURER_PART") "KEMET    C0603F224K3RAC")
      )
      (libsource (lib "Database_Libs1") (part "C"))
    )
    (comp (ref "C125")
      (value "C")
      (footprint "SMD_0603_CAPC1608X95N")
      (fields
        (field (name "DB_PART_NUMBER") "CAP000022968")
        (field (name "DB_VALUE") "220nF")
        (field (name "DB_TOLERANCE") "10%")
        (field (name "DB_VOLTAGE") "25V")
        (field (name "DB_MANUFACTURER_PART") "KEMET    C0603F224K3RAC")
      )
      (libsource (lib "Database_Libs1") (part "C"))
    )
    (comp (ref "C126")
      (value "C")
      (footprint "SMD_0603_CAPC1608X95N")
      (fields
        (field (name "DB_PART_NUMBER") "CAP000022968")
        (field (name "DB_VALUE") "220nF")
        (field (name "DB_TOLERANCE") "10%")
        (field (name "DB_VOLTAGE") "25V")
        (field (name "DB_MANUFACTURER_PART") "KEMET    C0603F224K3RAC")
      )
      (libsource (lib "Database_Libs1") (part "C"))
    )
    (comp (ref "C127")
      (value "C")
      (footprint "SMD_0603_CAPC1608X95N")
      (fields
        (field (name "DB_PART_NUMBER") "CAP000022968")
        (field (name "DB_VALUE") "220nF")
        (field (name "DB_TOLERANCE") "10%")
        (field (name "DB_VOLTAGE") "25V")
        (field (name "DB_MANUFACTURER_PART") "KEMET    C0603F224K3RAC")
      )
      (libsource (lib "Database_Libs1") (part "C"))
    )
    (comp (ref "C128")
      (value "C")
      (footprint "SMD_1210_CAPC3225X270N")
      (fields
        (field (name "DB_PART_NUMBER") "CAP000043701")
        (field (name "DB_VALUE") "100uF")
        (field (name "DB_TOLERANCE") "20%")
        (field (name "DB_VOLTAGE") "6.3V")
        (field (name "DB_MANUFACTURER_PART") "KEMET    C1210C107M9PAC")
      )
      (libsource (lib "Database_Libs1") (part "C"))
    )
    (comp (ref "C129")
      (value "C")
      (footprint "SMD_1210_CAPC3225X270N")
      (fields
        (field (name "DB_PART_NUMBER") "CAP000043701")
        (field (name "DB_VALUE") "100uF")
        (field (name "DB_TOLERANCE") "20%")
        (field (name "DB_VOLTAGE") "6.3V")
        (field (name "DB_MANUFACTURER_PART") "KEMET    C1210C107M9PAC")
      )
      (libsource (lib "Database_Libs1") (part "C"))
    )
    (comp (ref "C130")
      (value "C")
      (footprint "SMD_1210_CAPC3225X279N")
      (fields
        (field (name "DB_PART_NUMBER") "CAP000047355")
        (field (name "DB_VALUE") "220uF")
        (field (name "DB_TOLERANCE") "20%")
        (field (name "DB_VOLTAGE") "6.3V")
        (field (name "DB_MANUFACTURER_PART") "SAMSUNG    CL32A227MQVNNNE")
        (field (name "DB_APPROVED_BY") "VSN")
      )
      (libsource (lib "Database_Libs1") (part "C"))
    )
    (comp (ref "C131")
      (value "C")
      (footprint "SMD_1210_CAPC3225X279N")
      (fields
        (field (name "DB_PART_NUMBER") "CAP000047355")
        (field (name "DB_VALUE") "220uF")
        (field (name "DB_TOLERANCE") "20%")
        (field (name "DB_VOLTAGE") "6.3V")
        (field (name "DB_MANUFACTURER_PART") "SAMSUNG    CL32A227MQVNNNE")
        (field (name "DB_APPROVED_BY") "VSN")
      )
      (libsource (lib "Database_Libs1") (part "C"))
    )
    (comp (ref "C132")
      (value "C")
      (footprint "SMD_1210_CAPC3225X279N")
      (fields
        (field (name "DB_PART_NUMBER") "CAP000047355")
        (field (name "DB_VALUE") "220uF")
        (field (name "DB_TOLERANCE") "20%")
        (field (name "DB_VOLTAGE") "6.3V")
        (field (name "DB_MANUFACTURER_PART") "SAMSUNG    CL32A227MQVNNNE")
        (field (name "DB_APPROVED_BY") "VSN")
      )
      (libsource (lib "Database_Libs1") (part "C"))
    )
    (comp (ref "C133")
      (value "C")
      (footprint "SMD_1210_CAPC3225X270N")
      (fields
        (field (name "DB_PART_NUMBER") "CAP000043701")
        (field (name "DB_VALUE") "100uF")
        (field (name "DB_TOLERANCE") "20%")
        (field (name "DB_VOLTAGE") "6.3V")
        (field (name "DB_MANUFACTURER_PART") "KEMET    C1210C107M9PAC")
      )
      (libsource (lib "Database_Libs1") (part "C"))
    )
    (comp (ref "C134")
      (value "C")
      (footprint "SMD_1210_CAPC3225X270N")
      (fields
        (field (name "DB_PART_NUMBER") "CAP000043701")
        (field (name "DB_VALUE") "100uF")
        (field (name "DB_TOLERANCE") "20%")
        (field (name "DB_VOLTAGE") "6.3V")
        (field (name "DB_MANUFACTURER_PART") "KEMET    C1210C107M9PAC")
      )
      (libsource (lib "Database_Libs1") (part "C"))
    )
    (comp (ref "C135")
      (value "C")
      (footprint "SMD_1210_CAPC3225X279N")
      (fields
        (field (name "DB_PART_NUMBER") "CAP000047355")
        (field (name "DB_VALUE") "220uF")
        (field (name "DB_TOLERANCE") "20%")
        (field (name "DB_VOLTAGE") "6.3V")
        (field (name "DB_MANUFACTURER_PART") "SAMSUNG    CL32A227MQVNNNE")
        (field (name "DB_APPROVED_BY") "VSN")
      )
      (libsource (lib "Database_Libs1") (part "C"))
    )
    (comp (ref "C136")
      (value "C")
      (footprint "SMD_1210_CAPC3225X279N")
      (fields
        (field (name "DB_PART_NUMBER") "CAP000047355")
        (field (name "DB_VALUE") "220uF")
        (field (name "DB_TOLERANCE") "20%")
        (field (name "DB_VOLTAGE") "6.3V")
        (field (name "DB_MANUFACTURER_PART") "SAMSUNG    CL32A227MQVNNNE")
        (field (name "DB_APPROVED_BY") "VSN")
      )
      (libsource (lib "Database_Libs1") (part "C"))
    )
    (comp (ref "C137")
      (value "C")
      (footprint "SMD_1210_CAPC3225X279N")
      (fields
        (field (name "DB_PART_NUMBER") "CAP000047355")
        (field (name "DB_VALUE") "220uF")
        (field (name "DB_TOLERANCE") "20%")
        (field (name "DB_VOLTAGE") "6.3V")
        (field (name "DB_MANUFACTURER_PART") "SAMSUNG    CL32A227MQVNNNE")
        (field (name "DB_APPROVED_BY") "VSN")
      )
      (libsource (lib "Database_Libs1") (part "C"))
    )
    (comp (ref "C138")
      (value "C")
      (footprint "SMD_1210_CAPC3225X270N")
      (fields
        (field (name "DB_PART_NUMBER") "CAP000043701")
        (field (name "DB_VALUE") "100uF")
        (field (name "DB_TOLERANCE") "20%")
        (field (name "DB_VOLTAGE") "6.3V")
        (field (name "DB_MANUFACTURER_PART") "KEMET    C1210C107M9PAC")
      )
      (libsource (lib "Database_Libs1") (part "C"))
    )
    (comp (ref "C139")
      (value "C")
      (footprint "SMD_1210_CAPC3225X270N")
      (fields
        (field (name "DB_PART_NUMBER") "CAP000043701")
        (field (name "DB_VALUE") "100uF")
        (field (name "DB_TOLERANCE") "20%")
        (field (name "DB_VOLTAGE") "6.3V")
        (field (name "DB_MANUFACTURER_PART") "KEMET    C1210C107M9PAC")
      )
      (libsource (lib "Database_Libs1") (part "C"))
    )
    (comp (ref "C140")
      (value "C")
      (footprint "SMD_1210_CAPC3225X279N")
      (fields
        (field (name "DB_PART_NUMBER") "CAP000047355")
        (field (name "DB_VALUE") "220uF")
        (field (name "DB_TOLERANCE") "20%")
        (field (name "DB_VOLTAGE") "6.3V")
        (field (name "DB_MANUFACTURER_PART") "SAMSUNG    CL32A227MQVNNNE")
        (field (name "DB_APPROVED_BY") "VSN")
      )
      (libsource (lib "Database_Libs1") (part "C"))
    )
    (comp (ref "C141")
      (value "C")
      (footprint "SMD_1210_CAPC3225X279N")
      (fields
        (field (name "DB_PART_NUMBER") "CAP000047355")
        (field (name "DB_VALUE") "220uF")
        (field (name "DB_TOLERANCE") "20%")
        (field (name "DB_VOLTAGE") "6.3V")
        (field (name "DB_MANUFACTURER_PART") "SAMSUNG    CL32A227MQVNNNE")
        (field (name "DB_APPROVED_BY") "VSN")
      )
      (libsource (lib "Database_Libs1") (part "C"))
    )
    (comp (ref "C142")
      (value "C")
      (footprint "SMD_1210_CAPC3225X279N")
      (fields
        (field (name "DB_PART_NUMBER") "CAP000047355")
        (field (name "DB_VALUE") "220uF")
        (field (name "DB_TOLERANCE") "20%")
        (field (name "DB_VOLTAGE") "6.3V")
        (field (name "DB_MANUFACTURER_PART") "SAMSUNG    CL32A227MQVNNNE")
        (field (name "DB_APPROVED_BY") "VSN")
      )
      (libsource (lib "Database_Libs1") (part "C"))
    )
    (comp (ref "C143")
      (value "C")
      (footprint "SMD_1210_CAPC3225X270N")
      (fields
        (field (name "DB_PART_NUMBER") "CAP000043701")
        (field (name "DB_VALUE") "100uF")
        (field (name "DB_TOLERANCE") "20%")
        (field (name "DB_VOLTAGE") "6.3V")
        (field (name "DB_MANUFACTURER_PART") "KEMET    C1210C107M9PAC")
      )
      (libsource (lib "Database_Libs1") (part "C"))
    )
    (comp (ref "C144")
      (value "C")
      (footprint "SMD_1210_CAPC3225X270N")
      (fields
        (field (name "DB_PART_NUMBER") "CAP000043701")
        (field (name "DB_VALUE") "100uF")
        (field (name "DB_TOLERANCE") "20%")
        (field (name "DB_VOLTAGE") "6.3V")
        (field (name "DB_MANUFACTURER_PART") "KEMET    C1210C107M9PAC")
      )
      (libsource (lib "Database_Libs1") (part "C"))
    )
    (comp (ref "C145")
      (value "C")
      (footprint "SMD_1210_CAPC3225X279N")
      (fields
        (field (name "DB_PART_NUMBER") "CAP000047355")
        (field (name "DB_VALUE") "220uF")
        (field (name "DB_TOLERANCE") "20%")
        (field (name "DB_VOLTAGE") "6.3V")
        (field (name "DB_MANUFACTURER_PART") "SAMSUNG    CL32A227MQVNNNE")
        (field (name "DB_APPROVED_BY") "VSN")
      )
      (libsource (lib "Database_Libs1") (part "C"))
    )
    (comp (ref "C146")
      (value "C")
      (footprint "SMD_1210_CAPC3225X279N")
      (fields
        (field (name "DB_PART_NUMBER") "CAP000047355")
        (field (name "DB_VALUE") "220uF")
        (field (name "DB_TOLERANCE") "20%")
        (field (name "DB_VOLTAGE") "6.3V")
        (field (name "DB_MANUFACTURER_PART") "SAMSUNG    CL32A227MQVNNNE")
        (field (name "DB_APPROVED_BY") "VSN")
      )
      (libsource (lib "Database_Libs1") (part "C"))
    )
    (comp (ref "C147")
      (value "C")
      (footprint "SMD_1210_CAPC3225X279N")
      (fields
        (field (name "DB_PART_NUMBER") "CAP000047355")
        (field (name "DB_VALUE") "220uF")
        (field (name "DB_TOLERANCE") "20%")
        (field (name "DB_VOLTAGE") "6.3V")
        (field (name "DB_MANUFACTURER_PART") "SAMSUNG    CL32A227MQVNNNE")
        (field (name "DB_APPROVED_BY") "VSN")
      )
      (libsource (lib "Database_Libs1") (part "C"))
    )
    (comp (ref "C236")
      (value "C")
      (footprint "SMD_1210_CAPC3225X279N")
      (fields
        (field (name "DB_PART_NUMBER") "CAP000047355")
        (field (name "DB_VALUE") "220uF")
        (field (name "DB_TOLERANCE") "20%")
        (field (name "DB_VOLTAGE") "6.3V")
        (field (name "DB_MANUFACTURER_PART") "SAMSUNG    CL32A227MQVNNNE")
        (field (name "DB_APPROVED_BY") "VSN")
      )
      (libsource (lib "Database_Libs1") (part "C"))
    )
    (comp (ref "C348")
      (value "C")
      (footprint "SMD_1210_CAPC3225X270N")
      (fields
        (field (name "DB_PART_NUMBER") "CAP000043701")
        (field (name "DB_VALUE") "100uF")
        (field (name "DB_TOLERANCE") "20%")
        (field (name "DB_VOLTAGE") "6.3V")
        (field (name "DB_MANUFACTURER_PART") "KEMET    C1210C107M9PAC")
      )
      (libsource (lib "Database_Libs1") (part "C"))
    )
    (comp (ref "C349")
      (value "C")
      (footprint "SMD_1210_CAPC3225X270N")
      (fields
        (field (name "DB_PART_NUMBER") "CAP000043701")
        (field (name "DB_VALUE") "100uF")
        (field (name "DB_TOLERANCE") "20%")
        (field (name "DB_VOLTAGE") "6.3V")
        (field (name "DB_MANUFACTURER_PART") "KEMET    C1210C107M9PAC")
      )
      (libsource (lib "Database_Libs1") (part "C"))
    )
    (comp (ref "C350")
      (value "C")
      (footprint "SMD_1210_CAPC3225X279N")
      (fields
        (field (name "DB_PART_NUMBER") "CAP000047355")
        (field (name "DB_VALUE") "220uF")
        (field (name "DB_TOLERANCE") "20%")
        (field (name "DB_VOLTAGE") "6.3V")
        (field (name "DB_MANUFACTURER_PART") "SAMSUNG    CL32A227MQVNNNE")
        (field (name "DB_APPROVED_BY") "VSN")
      )
      (libsource (lib "Database_Libs1") (part "C"))
    )
    (comp (ref "C351")
      (value "C")
      (footprint "SMD_1210_CAPC3225X279N")
      (fields
        (field (name "DB_PART_NUMBER") "CAP000047355")
        (field (name "DB_VALUE") "220uF")
        (field (name "DB_TOLERANCE") "20%")
        (field (name "DB_VOLTAGE") "6.3V")
        (field (name "DB_MANUFACTURER_PART") "SAMSUNG    CL32A227MQVNNNE")
        (field (name "DB_APPROVED_BY") "VSN")
      )
      (libsource (lib "Database_Libs1") (part "C"))
    )
    (comp (ref "C352")
      (value "C")
      (footprint "SMD_1210_CAPC3225X279N")
      (fields
        (field (name "DB_PART_NUMBER") "CAP000047355")
        (field (name "DB_VALUE") "220uF")
        (field (name "DB_TOLERANCE") "20%")
        (field (name "DB_VOLTAGE") "6.3V")
        (field (name "DB_MANUFACTURER_PART") "SAMSUNG    CL32A227MQVNNNE")
        (field (name "DB_APPROVED_BY") "VSN")
      )
      (libsource (lib "Database_Libs1") (part "C"))
    )
    (comp (ref "C353")
      (value "C")
      (footprint "SMD_1210_CAPC3225X270N")
      (fields
        (field (name "DB_PART_NUMBER") "CAP000043701")
        (field (name "DB_VALUE") "100uF")
        (field (name "DB_TOLERANCE") "20%")
        (field (name "DB_VOLTAGE") "6.3V")
        (field (name "DB_MANUFACTURER_PART") "KEMET    C1210C107M9PAC")
      )
      (libsource (lib "Database_Libs1") (part "C"))
    )
    (comp (ref "C354")
      (value "C")
      (footprint "SMD_1210_CAPC3225X270N")
      (fields
        (field (name "DB_PART_NUMBER") "CAP000043701")
        (field (name "DB_VALUE") "100uF")
        (field (name "DB_TOLERANCE") "20%")
        (field (name "DB_VOLTAGE") "6.3V")
        (field (name "DB_MANUFACTURER_PART") "KEMET    C1210C107M9PAC")
      )
      (libsource (lib "Database_Libs1") (part "C"))
    )
    (comp (ref "C355")
      (value "C")
      (footprint "SMD_1210_CAPC3225X279N")
      (fields
        (field (name "DB_PART_NUMBER") "CAP000047355")
        (field (name "DB_VALUE") "220uF")
        (field (name "DB_TOLERANCE") "20%")
        (field (name "DB_VOLTAGE") "6.3V")
        (field (name "DB_MANUFACTURER_PART") "SAMSUNG    CL32A227MQVNNNE")
        (field (name "DB_APPROVED_BY") "VSN")
      )
      (libsource (lib "Database_Libs1") (part "C"))
    )
    (comp (ref "C356")
      (value "C")
      (footprint "SMD_1210_CAPC3225X279N")
      (fields
        (field (name "DB_PART_NUMBER") "CAP000047355")
        (field (name "DB_VALUE") "220uF")
        (field (name "DB_TOLERANCE") "20%")
        (field (name "DB_VOLTAGE") "6.3V")
        (field (name "DB_MANUFACTURER_PART") "SAMSUNG    CL32A227MQVNNNE")
        (field (name "DB_APPROVED_BY") "VSN")
      )
      (libsource (lib "Database_Libs1") (part "C"))
    )
    (comp (ref "C357")
      (value "C")
      (footprint "SMD_1210_CAPC3225X279N")
      (fields
        (field (name "DB_PART_NUMBER") "CAP000047355")
        (field (name "DB_VALUE") "220uF")
        (field (name "DB_TOLERANCE") "20%")
        (field (name "DB_VOLTAGE") "6.3V")
        (field (name "DB_MANUFACTURER_PART") "SAMSUNG    CL32A227MQVNNNE")
        (field (name "DB_APPROVED_BY") "VSN")
      )
      (libsource (lib "Database_Libs1") (part "C"))
    )
    (comp (ref "C358")
      (value "C")
      (footprint "SMD_1210_CAPC3225X270N")
      (fields
        (field (name "DB_PART_NUMBER") "CAP000043701")
        (field (name "DB_VALUE") "100uF")
        (field (name "DB_TOLERANCE") "20%")
        (field (name "DB_VOLTAGE") "6.3V")
        (field (name "DB_MANUFACTURER_PART") "KEMET    C1210C107M9PAC")
      )
      (libsource (lib "Database_Libs1") (part "C"))
    )
    (comp (ref "C359")
      (value "C")
      (footprint "SMD_1210_CAPC3225X270N")
      (fields
        (field (name "DB_PART_NUMBER") "CAP000043701")
        (field (name "DB_VALUE") "100uF")
        (field (name "DB_TOLERANCE") "20%")
        (field (name "DB_VOLTAGE") "6.3V")
        (field (name "DB_MANUFACTURER_PART") "KEMET    C1210C107M9PAC")
      )
      (libsource (lib "Database_Libs1") (part "C"))
    )
    (comp (ref "C360")
      (value "C")
      (footprint "SMD_1210_CAPC3225X279N")
      (fields
        (field (name "DB_PART_NUMBER") "CAP000047355")
        (field (name "DB_VALUE") "220uF")
        (field (name "DB_TOLERANCE") "20%")
        (field (name "DB_VOLTAGE") "6.3V")
        (field (name "DB_MANUFACTURER_PART") "SAMSUNG    CL32A227MQVNNNE")
        (field (name "DB_APPROVED_BY") "VSN")
      )
      (libsource (lib "Database_Libs1") (part "C"))
    )
    (comp (ref "C361")
      (value "C")
      (footprint "SMD_1210_CAPC3225X279N")
      (fields
        (field (name "DB_PART_NUMBER") "CAP000047355")
        (field (name "DB_VALUE") "220uF")
        (field (name "DB_TOLERANCE") "20%")
        (field (name "DB_VOLTAGE") "6.3V")
        (field (name "DB_MANUFACTURER_PART") "SAMSUNG    CL32A227MQVNNNE")
        (field (name "DB_APPROVED_BY") "VSN")
      )
      (libsource (lib "Database_Libs1") (part "C"))
    )
    (comp (ref "C362")
      (value "C")
      (footprint "SMD_1210_CAPC3225X279N")
      (fields
        (field (name "DB_PART_NUMBER") "CAP000047355")
        (field (name "DB_VALUE") "220uF")
        (field (name "DB_TOLERANCE") "20%")
        (field (name "DB_VOLTAGE") "6.3V")
        (field (name "DB_MANUFACTURER_PART") "SAMSUNG    CL32A227MQVNNNE")
        (field (name "DB_APPROVED_BY") "VSN")
      )
      (libsource (lib "Database_Libs1") (part "C"))
    )
    (comp (ref "C363")
      (value "C")
      (footprint "SMD_1210_CAPC3225X270N")
      (fields
        (field (name "DB_PART_NUMBER") "CAP000043701")
        (field (name "DB_VALUE") "100uF")
        (field (name "DB_TOLERANCE") "20%")
        (field (name "DB_VOLTAGE") "6.3V")
        (field (name "DB_MANUFACTURER_PART") "KEMET    C1210C107M9PAC")
      )
      (libsource (lib "Database_Libs1") (part "C"))
    )
    (comp (ref "C364")
      (value "C")
      (footprint "SMD_1210_CAPC3225X270N")
      (fields
        (field (name "DB_PART_NUMBER") "CAP000043701")
        (field (name "DB_VALUE") "100uF")
        (field (name "DB_TOLERANCE") "20%")
        (field (name "DB_VOLTAGE") "6.3V")
        (field (name "DB_MANUFACTURER_PART") "KEMET    C1210C107M9PAC")
      )
      (libsource (lib "Database_Libs1") (part "C"))
    )
    (comp (ref "C365")
      (value "C")
      (footprint "SMD_1210_CAPC3225X279N")
      (fields
        (field (name "DB_PART_NUMBER") "CAP000047355")
        (field (name "DB_VALUE") "220uF")
        (field (name "DB_TOLERANCE") "20%")
        (field (name "DB_VOLTAGE") "6.3V")
        (field (name "DB_MANUFACTURER_PART") "SAMSUNG    CL32A227MQVNNNE")
        (field (name "DB_APPROVED_BY") "VSN")
      )
      (libsource (lib "Database_Libs1") (part "C"))
    )
    (comp (ref "C366")
      (value "C")
      (footprint "SMD_1210_CAPC3225X279N")
      (fields
        (field (name "DB_PART_NUMBER") "CAP000047355")
        (field (name "DB_VALUE") "220uF")
        (field (name "DB_TOLERANCE") "20%")
        (field (name "DB_VOLTAGE") "6.3V")
        (field (name "DB_MANUFACTURER_PART") "SAMSUNG    CL32A227MQVNNNE")
        (field (name "DB_APPROVED_BY") "VSN")
      )
      (libsource (lib "Database_Libs1") (part "C"))
    )
    (comp (ref "C367")
      (value "C")
      (footprint "SMD_1210_CAPC3225X279N")
      (fields
        (field (name "DB_PART_NUMBER") "CAP000047355")
        (field (name "DB_VALUE") "220uF")
        (field (name "DB_TOLERANCE") "20%")
        (field (name "DB_VOLTAGE") "6.3V")
        (field (name "DB_MANUFACTURER_PART") "SAMSUNG    CL32A227MQVNNNE")
        (field (name "DB_APPROVED_BY") "VSN")
      )
      (libsource (lib "Database_Libs1") (part "C"))
    )
    (comp (ref "C368")
      (value "C")
      (footprint "SMD_1210_CAPC3225X270N")
      (fields
        (field (name "DB_PART_NUMBER") "CAP000043701")
        (field (name "DB_VALUE") "100uF")
        (field (name "DB_TOLERANCE") "20%")
        (field (name "DB_VOLTAGE") "6.3V")
        (field (name "DB_MANUFACTURER_PART") "KEMET    C1210C107M9PAC")
      )
      (libsource (lib "Database_Libs1") (part "C"))
    )
    (comp (ref "C369")
      (value "C")
      (footprint "SMD_1210_CAPC3225X270N")
      (fields
        (field (name "DB_PART_NUMBER") "CAP000043701")
        (field (name "DB_VALUE") "100uF")
        (field (name "DB_TOLERANCE") "20%")
        (field (name "DB_VOLTAGE") "6.3V")
        (field (name "DB_MANUFACTURER_PART") "KEMET    C1210C107M9PAC")
      )
      (libsource (lib "Database_Libs1") (part "C"))
    )
    (comp (ref "C370")
      (value "C")
      (footprint "SMD_1210_CAPC3225X279N")
      (fields
        (field (name "DB_PART_NUMBER") "CAP000047355")
        (field (name "DB_VALUE") "220uF")
        (field (name "DB_TOLERANCE") "20%")
        (field (name "DB_VOLTAGE") "6.3V")
        (field (name "DB_MANUFACTURER_PART") "SAMSUNG    CL32A227MQVNNNE")
        (field (name "DB_APPROVED_BY") "VSN")
      )
      (libsource (lib "Database_Libs1") (part "C"))
    )
    (comp (ref "C371")
      (value "C")
      (footprint "SMD_1210_CAPC3225X279N")
      (fields
        (field (name "DB_PART_NUMBER") "CAP000047355")
        (field (name "DB_VALUE") "220uF")
        (field (name "DB_TOLERANCE") "20%")
        (field (name "DB_VOLTAGE") "6.3V")
        (field (name "DB_MANUFACTURER_PART") "SAMSUNG    CL32A227MQVNNNE")
        (field (name "DB_APPROVED_BY") "VSN")
      )
      (libsource (lib "Database_Libs1") (part "C"))
    )
    (comp (ref "C372")
      (value "C")
      (footprint "SMD_1210_CAPC3225X279N")
      (fields
        (field (name "DB_PART_NUMBER") "CAP000047355")
        (field (name "DB_VALUE") "220uF")
        (field (name "DB_TOLERANCE") "20%")
        (field (name "DB_VOLTAGE") "6.3V")
        (field (name "DB_MANUFACTURER_PART") "SAMSUNG    CL32A227MQVNNNE")
        (field (name "DB_APPROVED_BY") "VSN")
      )
      (libsource (lib "Database_Libs1") (part "C"))
    )
    (comp (ref "C373")
      (value "C")
      (footprint "SMD_1210_CAPC3225X270N")
      (fields
        (field (name "DB_PART_NUMBER") "CAP000043701")
        (field (name "DB_VALUE") "100uF")
        (field (name "DB_TOLERANCE") "20%")
        (field (name "DB_VOLTAGE") "6.3V")
        (field (name "DB_MANUFACTURER_PART") "KEMET    C1210C107M9PAC")
      )
      (libsource (lib "Database_Libs1") (part "C"))
    )
    (comp (ref "C374")
      (value "C")
      (footprint "SMD_1210_CAPC3225X270N")
      (fields
        (field (name "DB_PART_NUMBER") "CAP000043701")
        (field (name "DB_VALUE") "100uF")
        (field (name "DB_TOLERANCE") "20%")
        (field (name "DB_VOLTAGE") "6.3V")
        (field (name "DB_MANUFACTURER_PART") "KEMET    C1210C107M9PAC")
      )
      (libsource (lib "Database_Libs1") (part "C"))
    )
    (comp (ref "C375")
      (value "C")
      (footprint "SMD_1210_CAPC3225X279N")
      (fields
        (field (name "DB_PART_NUMBER") "CAP000047355")
        (field (name "DB_VALUE") "220uF")
        (field (name "DB_TOLERANCE") "20%")
        (field (name "DB_VOLTAGE") "6.3V")
        (field (name "DB_MANUFACTURER_PART") "SAMSUNG    CL32A227MQVNNNE")
        (field (name "DB_APPROVED_BY") "VSN")
      )
      (libsource (lib "Database_Libs1") (part "C"))
    )
    (comp (ref "C376")
      (value "C")
      (footprint "SMD_1210_CAPC3225X279N")
      (fields
        (field (name "DB_PART_NUMBER") "CAP000047355")
        (field (name "DB_VALUE") "220uF")
        (field (name "DB_TOLERANCE") "20%")
        (field (name "DB_VOLTAGE") "6.3V")
        (field (name "DB_MANUFACTURER_PART") "SAMSUNG    CL32A227MQVNNNE")
        (field (name "DB_APPROVED_BY") "VSN")
      )
      (libsource (lib "Database_Libs1") (part "C"))
    )
    (comp (ref "C377")
      (value "C")
      (footprint "SMD_1210_CAPC3225X279N")
      (fields
        (field (name "DB_PART_NUMBER") "CAP000047355")
        (field (name "DB_VALUE") "220uF")
        (field (name "DB_TOLERANCE") "20%")
        (field (name "DB_VOLTAGE") "6.3V")
        (field (name "DB_MANUFACTURER_PART") "SAMSUNG    CL32A227MQVNNNE")
        (field (name "DB_APPROVED_BY") "VSN")
      )
      (libsource (lib "Database_Libs1") (part "C"))
    )
    (comp (ref "C378")
      (value "C")
      (footprint "SMD_1210_CAPC3225X270N")
      (fields
        (field (name "DB_PART_NUMBER") "CAP000043701")
        (field (name "DB_VALUE") "100uF")
        (field (name "DB_TOLERANCE") "20%")
        (field (name "DB_VOLTAGE") "6.3V")
        (field (name "DB_MANUFACTURER_PART") "KEMET    C1210C107M9PAC")
      )
      (libsource (lib "Database_Libs1") (part "C"))
    )
    (comp (ref "C379")
      (value "C")
      (footprint "SMD_1210_CAPC3225X270N")
      (fields
        (field (name "DB_PART_NUMBER") "CAP000043701")
        (field (name "DB_VALUE") "100uF")
        (field (name "DB_TOLERANCE") "20%")
        (field (name "DB_VOLTAGE") "6.3V")
        (field (name "DB_MANUFACTURER_PART") "KEMET    C1210C107M9PAC")
      )
      (libsource (lib "Database_Libs1") (part "C"))
    )
    (comp (ref "C380")
      (value "C")
      (footprint "SMD_1210_CAPC3225X279N")
      (fields
        (field (name "DB_PART_NUMBER") "CAP000047355")
        (field (name "DB_VALUE") "220uF")
        (field (name "DB_TOLERANCE") "20%")
        (field (name "DB_VOLTAGE") "6.3V")
        (field (name "DB_MANUFACTURER_PART") "SAMSUNG    CL32A227MQVNNNE")
        (field (name "DB_APPROVED_BY") "VSN")
      )
      (libsource (lib "Database_Libs1") (part "C"))
    )
    (comp (ref "C381")
      (value "C")
      (footprint "SMD_1210_CAPC3225X279N")
      (fields
        (field (name "DB_PART_NUMBER") "CAP000047355")
        (field (name "DB_VALUE") "220uF")
        (field (name "DB_TOLERANCE") "20%")
        (field (name "DB_VOLTAGE") "6.3V")
        (field (name "DB_MANUFACTURER_PART") "SAMSUNG    CL32A227MQVNNNE")
        (field (name "DB_APPROVED_BY") "VSN")
      )
      (libsource (lib "Database_Libs1") (part "C"))
    )
    (comp (ref "C382")
      (value "C")
      (footprint "SMD_1210_CAPC3225X279N")
      (fields
        (field (name "DB_PART_NUMBER") "CAP000047355")
        (field (name "DB_VALUE") "220uF")
        (field (name "DB_TOLERANCE") "20%")
        (field (name "DB_VOLTAGE") "6.3V")
        (field (name "DB_MANUFACTURER_PART") "SAMSUNG    CL32A227MQVNNNE")
        (field (name "DB_APPROVED_BY") "VSN")
      )
      (libsource (lib "Database_Libs1") (part "C"))
    )
    (comp (ref "C383")
      (value "C")
      (footprint "SMD_1210_CAPC3225X270N")
      (fields
        (field (name "DB_PART_NUMBER") "CAP000043701")
        (field (name "DB_VALUE") "100uF")
        (field (name "DB_TOLERANCE") "20%")
        (field (name "DB_VOLTAGE") "6.3V")
        (field (name "DB_MANUFACTURER_PART") "KEMET    C1210C107M9PAC")
      )
      (libsource (lib "Database_Libs1") (part "C"))
    )
    (comp (ref "C384")
      (value "C")
      (footprint "SMD_1210_CAPC3225X270N")
      (fields
        (field (name "DB_PART_NUMBER") "CAP000043701")
        (field (name "DB_VALUE") "100uF")
        (field (name "DB_TOLERANCE") "20%")
        (field (name "DB_VOLTAGE") "6.3V")
        (field (name "DB_MANUFACTURER_PART") "KEMET    C1210C107M9PAC")
      )
      (libsource (lib "Database_Libs1") (part "C"))
    )
    (comp (ref "C385")
      (value "C")
      (footprint "SMD_1210_CAPC3225X279N")
      (fields
        (field (name "DB_PART_NUMBER") "CAP000047355")
        (field (name "DB_VALUE") "220uF")
        (field (name "DB_TOLERANCE") "20%")
        (field (name "DB_VOLTAGE") "6.3V")
        (field (name "DB_MANUFACTURER_PART") "SAMSUNG    CL32A227MQVNNNE")
        (field (name "DB_APPROVED_BY") "VSN")
      )
      (libsource (lib "Database_Libs1") (part "C"))
    )
    (comp (ref "C386")
      (value "C")
      (footprint "SMD_1210_CAPC3225X279N")
      (fields
        (field (name "DB_PART_NUMBER") "CAP000047355")
        (field (name "DB_VALUE") "220uF")
        (field (name "DB_TOLERANCE") "20%")
        (field (name "DB_VOLTAGE") "6.3V")
        (field (name "DB_MANUFACTURER_PART") "SAMSUNG    CL32A227MQVNNNE")
        (field (name "DB_APPROVED_BY") "VSN")
      )
      (libsource (lib "Database_Libs1") (part "C"))
    )
    (comp (ref "C387")
      (value "C")
      (footprint "SMD_1210_CAPC3225X279N")
      (fields
        (field (name "DB_PART_NUMBER") "CAP000047355")
        (field (name "DB_VALUE") "220uF")
        (field (name "DB_TOLERANCE") "20%")
        (field (name "DB_VOLTAGE") "6.3V")
        (field (name "DB_MANUFACTURER_PART") "SAMSUNG    CL32A227MQVNNNE")
        (field (name "DB_APPROVED_BY") "VSN")
      )
      (libsource (lib "Database_Libs1") (part "C"))
    )
    (comp (ref "C388")
      (value "C")
      (footprint "SMD_1210_CAPC3225X279N")
      (fields
        (field (name "DB_PART_NUMBER") "CAP000047355")
        (field (name "DB_VALUE") "220uF")
        (field (name "DB_TOLERANCE") "20%")
        (field (name "DB_VOLTAGE") "6.3V")
        (field (name "DB_MANUFACTURER_PART") "SAMSUNG    CL32A227MQVNNNE")
        (field (name "DB_APPROVED_BY") "VSN")
      )
      (libsource (lib "Database_Libs1") (part "C"))
    )
    (comp (ref "C389")
      (value "C")
      (footprint "SMD_1210_CAPC3225X279N")
      (fields
        (field (name "DB_PART_NUMBER") "CAP000047355")
        (field (name "DB_VALUE") "220uF")
        (field (name "DB_TOLERANCE") "20%")
        (field (name "DB_VOLTAGE") "6.3V")
        (field (name "DB_MANUFACTURER_PART") "SAMSUNG    CL32A227MQVNNNE")
        (field (name "DB_APPROVED_BY") "VSN")
      )
      (libsource (lib "Database_Libs1") (part "C"))
    )
    (comp (ref "C390")
      (value "C")
      (footprint "SMD_1210_CAPC3225X279N")
      (fields
        (field (name "DB_PART_NUMBER") "CAP000047355")
        (field (name "DB_VALUE") "220uF")
        (field (name "DB_TOLERANCE") "20%")
        (field (name "DB_VOLTAGE") "6.3V")
        (field (name "DB_MANUFACTURER_PART") "SAMSUNG    CL32A227MQVNNNE")
        (field (name "DB_APPROVED_BY") "VSN")
      )
      (libsource (lib "Database_Libs1") (part "C"))
    )
    (comp (ref "C391")
      (value "C")
      (footprint "SMD_1210_CAPC3225X270N")
      (fields
        (field (name "DB_PART_NUMBER") "CAP000043701")
        (field (name "DB_VALUE") "100uF")
        (field (name "DB_TOLERANCE") "20%")
        (field (name "DB_VOLTAGE") "6.3V")
        (field (name "DB_MANUFACTURER_PART") "KEMET    C1210C107M9PAC")
      )
      (libsource (lib "Database_Libs1") (part "C"))
    )
    (comp (ref "C392")
      (value "C")
      (footprint "SMD_1210_CAPC3225X270N")
      (fields
        (field (name "DB_PART_NUMBER") "CAP000043701")
        (field (name "DB_VALUE") "100uF")
        (field (name "DB_TOLERANCE") "20%")
        (field (name "DB_VOLTAGE") "6.3V")
        (field (name "DB_MANUFACTURER_PART") "KEMET    C1210C107M9PAC")
      )
      (libsource (lib "Database_Libs1") (part "C"))
    )
    (comp (ref "C393")
      (value "C")
      (footprint "SMD_1210_CAPC3225X279N")
      (fields
        (field (name "DB_PART_NUMBER") "CAP000047355")
        (field (name "DB_VALUE") "220uF")
        (field (name "DB_TOLERANCE") "20%")
        (field (name "DB_VOLTAGE") "6.3V")
        (field (name "DB_MANUFACTURER_PART") "SAMSUNG    CL32A227MQVNNNE")
        (field (name "DB_APPROVED_BY") "VSN")
      )
      (libsource (lib "Database_Libs1") (part "C"))
    )
    (comp (ref "C394")
      (value "C")
      (footprint "SMD_1210_CAPC3225X279N")
      (fields
        (field (name "DB_PART_NUMBER") "CAP000047355")
        (field (name "DB_VALUE") "220uF")
        (field (name "DB_TOLERANCE") "20%")
        (field (name "DB_VOLTAGE") "6.3V")
        (field (name "DB_MANUFACTURER_PART") "SAMSUNG    CL32A227MQVNNNE")
        (field (name "DB_APPROVED_BY") "VSN")
      )
      (libsource (lib "Database_Libs1") (part "C"))
    )
    (comp (ref "C395")
      (value "C")
      (footprint "SMD_1210_CAPC3225X279N")
      (fields
        (field (name "DB_PART_NUMBER") "CAP000047355")
        (field (name "DB_VALUE") "220uF")
        (field (name "DB_TOLERANCE") "20%")
        (field (name "DB_VOLTAGE") "6.3V")
        (field (name "DB_MANUFACTURER_PART") "SAMSUNG    CL32A227MQVNNNE")
        (field (name "DB_APPROVED_BY") "VSN")
      )
      (libsource (lib "Database_Libs1") (part "C"))
    )
    (comp (ref "C396")
      (value "C")
      (footprint "SMD_1210_CAPC3225X279N")
      (fields
        (field (name "DB_PART_NUMBER") "CAP000047355")
        (field (name "DB_VALUE") "220uF")
        (field (name "DB_TOLERANCE") "20%")
        (field (name "DB_VOLTAGE") "6.3V")
        (field (name "DB_MANUFACTURER_PART") "SAMSUNG    CL32A227MQVNNNE")
        (field (name "DB_APPROVED_BY") "VSN")
      )
      (libsource (lib "Database_Libs1") (part "C"))
    )
    (comp (ref "C397")
      (value "C")
      (footprint "SMD_1210_CAPC3225X279N")
      (fields
        (field (name "DB_PART_NUMBER") "CAP000047355")
        (field (name "DB_VALUE") "220uF")
        (field (name "DB_TOLERANCE") "20%")
        (field (name "DB_VOLTAGE") "6.3V")
        (field (name "DB_MANUFACTURER_PART") "SAMSUNG    CL32A227MQVNNNE")
        (field (name "DB_APPROVED_BY") "VSN")
      )
      (libsource (lib "Database_Libs1") (part "C"))
    )
    (comp (ref "C398")
      (value "C")
      (footprint "SMD_1210_CAPC3225X279N")
      (fields
        (field (name "DB_PART_NUMBER") "CAP000047355")
        (field (name "DB_VALUE") "220uF")
        (field (name "DB_TOLERANCE") "20%")
        (field (name "DB_VOLTAGE") "6.3V")
        (field (name "DB_MANUFACTURER_PART") "SAMSUNG    CL32A227MQVNNNE")
        (field (name "DB_APPROVED_BY") "VSN")
      )
      (libsource (lib "Database_Libs1") (part "C"))
    )
    (comp (ref "C399")
      (value "C")
      (footprint "SMD_1210_CAPC3225X279N")
      (fields
        (field (name "DB_PART_NUMBER") "CAP000047355")
        (field (name "DB_VALUE") "220uF")
        (field (name "DB_TOLERANCE") "20%")
        (field (name "DB_VOLTAGE") "6.3V")
        (field (name "DB_MANUFACTURER_PART") "SAMSUNG    CL32A227MQVNNNE")
        (field (name "DB_APPROVED_BY") "VSN")
      )
      (libsource (lib "Database_Libs1") (part "C"))
    )
    (comp (ref "C400")
      (value "C")
      (footprint "SMD_1210_CAPC3225X279N")
      (fields
        (field (name "DB_PART_NUMBER") "CAP000047355")
        (field (name "DB_VALUE") "220uF")
        (field (name "DB_TOLERANCE") "20%")
        (field (name "DB_VOLTAGE") "6.3V")
        (field (name "DB_MANUFACTURER_PART") "SAMSUNG    CL32A227MQVNNNE")
        (field (name "DB_APPROVED_BY") "VSN")
      )
      (libsource (lib "Database_Libs1") (part "C"))
    )
    (comp (ref "C401")
      (value "C")
      (footprint "SMD_1210_CAPC3225X279N")
      (fields
        (field (name "DB_PART_NUMBER") "CAP000047355")
        (field (name "DB_VALUE") "220uF")
        (field (name "DB_TOLERANCE") "20%")
        (field (name "DB_VOLTAGE") "6.3V")
        (field (name "DB_MANUFACTURER_PART") "SAMSUNG    CL32A227MQVNNNE")
        (field (name "DB_APPROVED_BY") "VSN")
      )
      (libsource (lib "Database_Libs1") (part "C"))
    )
    (comp (ref "C402")
      (value "C")
      (footprint "SMD_1210_CAPC3225X270N")
      (fields
        (field (name "DB_PART_NUMBER") "CAP000043701")
        (field (name "DB_VALUE") "100uF")
        (field (name "DB_TOLERANCE") "20%")
        (field (name "DB_VOLTAGE") "6.3V")
        (field (name "DB_MANUFACTURER_PART") "KEMET    C1210C107M9PAC")
      )
      (libsource (lib "Database_Libs1") (part "C"))
    )
    (comp (ref "C403")
      (value "C")
      (footprint "SMD_1210_CAPC3225X270N")
      (fields
        (field (name "DB_PART_NUMBER") "CAP000043701")
        (field (name "DB_VALUE") "100uF")
        (field (name "DB_TOLERANCE") "20%")
        (field (name "DB_VOLTAGE") "6.3V")
        (field (name "DB_MANUFACTURER_PART") "KEMET    C1210C107M9PAC")
      )
      (libsource (lib "Database_Libs1") (part "C"))
    )
    (comp (ref "C404")
      (value "C")
      (footprint "SMD_1210_CAPC3225X270N")
      (fields
        (field (name "DB_PART_NUMBER") "CAP000043701")
        (field (name "DB_VALUE") "100uF")
        (field (name "DB_TOLERANCE") "20%")
        (field (name "DB_VOLTAGE") "6.3V")
        (field (name "DB_MANUFACTURER_PART") "KEMET    C1210C107M9PAC")
      )
      (libsource (lib "Database_Libs1") (part "C"))
    )
    (comp (ref "C405")
      (value "C")
      (footprint "SMD_1210_CAPC3225X270N")
      (fields
        (field (name "DB_PART_NUMBER") "CAP000043701")
        (field (name "DB_VALUE") "100uF")
        (field (name "DB_TOLERANCE") "20%")
        (field (name "DB_VOLTAGE") "6.3V")
        (field (name "DB_MANUFACTURER_PART") "KEMET    C1210C107M9PAC")
      )
      (libsource (lib "Database_Libs1") (part "C"))
    )
    (comp (ref "C406")
      (value "C")
      (footprint "SMD_1210_CAPC3225X270N")
      (fields
        (field (name "DB_PART_NUMBER") "CAP000043701")
        (field (name "DB_VALUE") "100uF")
        (field (name "DB_TOLERANCE") "20%")
        (field (name "DB_VOLTAGE") "6.3V")
        (field (name "DB_MANUFACTURER_PART") "KEMET    C1210C107M9PAC")
      )
      (libsource (lib "Database_Libs1") (part "C"))
    )
    (comp (ref "C407")
      (value "C")
      (footprint "SMD_1210_CAPC3225X270N")
      (fields
        (field (name "DB_PART_NUMBER") "CAP000043701")
        (field (name "DB_VALUE") "100uF")
        (field (name "DB_TOLERANCE") "20%")
        (field (name "DB_VOLTAGE") "6.3V")
        (field (name "DB_MANUFACTURER_PART") "KEMET    C1210C107M9PAC")
      )
      (libsource (lib "Database_Libs1") (part "C"))
    )
    (comp (ref "C408")
      (value "C")
      (footprint "SMD_1210_CAPC3225X279N")
      (fields
        (field (name "DB_PART_NUMBER") "CAP000047355")
        (field (name "DB_VALUE") "220uF")
        (field (name "DB_TOLERANCE") "20%")
        (field (name "DB_VOLTAGE") "6.3V")
        (field (name "DB_MANUFACTURER_PART") "SAMSUNG    CL32A227MQVNNNE")
        (field (name "DB_APPROVED_BY") "VSN")
      )
      (libsource (lib "Database_Libs1") (part "C"))
    )
    (comp (ref "C409")
      (value "C")
      (footprint "SMD_1210_CAPC3225X279N")
      (fields
        (field (name "DB_PART_NUMBER") "CAP000047355")
        (field (name "DB_VALUE") "220uF")
        (field (name "DB_TOLERANCE") "20%")
        (field (name "DB_VOLTAGE") "6.3V")
        (field (name "DB_MANUFACTURER_PART") "SAMSUNG    CL32A227MQVNNNE")
        (field (name "DB_APPROVED_BY") "VSN")
      )
      (libsource (lib "Database_Libs1") (part "C"))
    )
    (comp (ref "C410")
      (value "C")
      (footprint "SMD_1210_CAPC3225X279N")
      (fields
        (field (name "DB_PART_NUMBER") "CAP000047355")
        (field (name "DB_VALUE") "220uF")
        (field (name "DB_TOLERANCE") "20%")
        (field (name "DB_VOLTAGE") "6.3V")
        (field (name "DB_MANUFACTURER_PART") "SAMSUNG    CL32A227MQVNNNE")
        (field (name "DB_APPROVED_BY") "VSN")
      )
      (libsource (lib "Database_Libs1") (part "C"))
    )
    (comp (ref "C411")
      (value "C")
      (footprint "SMD_1210_CAPC3225X279N")
      (fields
        (field (name "DB_PART_NUMBER") "CAP000047355")
        (field (name "DB_VALUE") "220uF")
        (field (name "DB_TOLERANCE") "20%")
        (field (name "DB_VOLTAGE") "6.3V")
        (field (name "DB_MANUFACTURER_PART") "SAMSUNG    CL32A227MQVNNNE")
        (field (name "DB_APPROVED_BY") "VSN")
      )
      (libsource (lib "Database_Libs1") (part "C"))
    )
    (comp (ref "C412")
      (value "C")
      (footprint "SMD_1210_CAPC3225X279N")
      (fields
        (field (name "DB_PART_NUMBER") "CAP000047355")
        (field (name "DB_VALUE") "220uF")
        (field (name "DB_TOLERANCE") "20%")
        (field (name "DB_VOLTAGE") "6.3V")
        (field (name "DB_MANUFACTURER_PART") "SAMSUNG    CL32A227MQVNNNE")
        (field (name "DB_APPROVED_BY") "VSN")
      )
      (libsource (lib "Database_Libs1") (part "C"))
    )
    (comp (ref "C413")
      (value "C")
      (footprint "SMD_1210_CAPC3225X279N")
      (fields
        (field (name "DB_PART_NUMBER") "CAP000047355")
        (field (name "DB_VALUE") "220uF")
        (field (name "DB_TOLERANCE") "20%")
        (field (name "DB_VOLTAGE") "6.3V")
        (field (name "DB_MANUFACTURER_PART") "SAMSUNG    CL32A227MQVNNNE")
        (field (name "DB_APPROVED_BY") "VSN")
      )
      (libsource (lib "Database_Libs1") (part "C"))
    )
    (comp (ref "C414")
      (value "C")
      (footprint "SMD_1210_CAPC3225X279N")
      (fields
        (field (name "DB_PART_NUMBER") "CAP000047355")
        (field (name "DB_VALUE") "220uF")
        (field (name "DB_TOLERANCE") "20%")
        (field (name "DB_VOLTAGE") "6.3V")
        (field (name "DB_MANUFACTURER_PART") "SAMSUNG    CL32A227MQVNNNE")
        (field (name "DB_APPROVED_BY") "VSN")
      )
      (libsource (lib "Database_Libs1") (part "C"))
    )
    (comp (ref "C415")
      (value "C")
      (footprint "SMD_1210_CAPC3225X279N")
      (fields
        (field (name "DB_PART_NUMBER") "CAP000047355")
        (field (name "DB_VALUE") "220uF")
        (field (name "DB_TOLERANCE") "20%")
        (field (name "DB_VOLTAGE") "6.3V")
        (field (name "DB_MANUFACTURER_PART") "SAMSUNG    CL32A227MQVNNNE")
        (field (name "DB_APPROVED_BY") "VSN")
      )
      (libsource (lib "Database_Libs1") (part "C"))
    )
    (comp (ref "C416")
      (value "C")
      (footprint "SMD_1210_CAPC3225X279N")
      (fields
        (field (name "DB_PART_NUMBER") "CAP000047355")
        (field (name "DB_VALUE") "220uF")
        (field (name "DB_TOLERANCE") "20%")
        (field (name "DB_VOLTAGE") "6.3V")
        (field (name "DB_MANUFACTURER_PART") "SAMSUNG    CL32A227MQVNNNE")
        (field (name "DB_APPROVED_BY") "VSN")
      )
      (libsource (lib "Database_Libs1") (part "C"))
    )
    (comp (ref "C417")
      (value "C")
      (footprint "SMD_1210_CAPC3225X279N")
      (fields
        (field (name "DB_PART_NUMBER") "CAP000047355")
        (field (name "DB_VALUE") "220uF")
        (field (name "DB_TOLERANCE") "20%")
        (field (name "DB_VOLTAGE") "6.3V")
        (field (name "DB_MANUFACTURER_PART") "SAMSUNG    CL32A227MQVNNNE")
        (field (name "DB_APPROVED_BY") "VSN")
      )
      (libsource (lib "Database_Libs1") (part "C"))
    )
    (comp (ref "C418")
      (value "C")
      (footprint "SMD_1210_CAPC3225X279N")
      (fields
        (field (name "DB_PART_NUMBER") "CAP000047355")
        (field (name "DB_VALUE") "220uF")
        (field (name "DB_TOLERANCE") "20%")
        (field (name "DB_VOLTAGE") "6.3V")
        (field (name "DB_MANUFACTURER_PART") "SAMSUNG    CL32A227MQVNNNE")
        (field (name "DB_APPROVED_BY") "VSN")
      )
      (libsource (lib "Database_Libs1") (part "C"))
    )
    (comp (ref "C419")
      (value "C")
      (footprint "SMD_1210_CAPC3225X279N")
      (fields
        (field (name "DB_PART_NUMBER") "CAP000047355")
        (field (name "DB_VALUE") "220uF")
        (field (name "DB_TOLERANCE") "20%")
        (field (name "DB_VOLTAGE") "6.3V")
        (field (name "DB_MANUFACTURER_PART") "SAMSUNG    CL32A227MQVNNNE")
        (field (name "DB_APPROVED_BY") "VSN")
      )
      (libsource (lib "Database_Libs1") (part "C"))
    )
    (comp (ref "C420")
      (value "C")
      (footprint "SMD_1210_CAPC3225X270N")
      (fields
        (field (name "DB_PART_NUMBER") "CAP000043701")
        (field (name "DB_VALUE") "100uF")
        (field (name "DB_TOLERANCE") "20%")
        (field (name "DB_VOLTAGE") "6.3V")
        (field (name "DB_MANUFACTURER_PART") "KEMET    C1210C107M9PAC")
      )
      (libsource (lib "Database_Libs1") (part "C"))
    )
    (comp (ref "C421")
      (value "C")
      (footprint "SMD_1210_CAPC3225X270N")
      (fields
        (field (name "DB_PART_NUMBER") "CAP000043701")
        (field (name "DB_VALUE") "100uF")
        (field (name "DB_TOLERANCE") "20%")
        (field (name "DB_VOLTAGE") "6.3V")
        (field (name "DB_MANUFACTURER_PART") "KEMET    C1210C107M9PAC")
      )
      (libsource (lib "Database_Libs1") (part "C"))
    )
    (comp (ref "C422")
      (value "C")
      (footprint "SMD_1210_CAPC3225X270N")
      (fields
        (field (name "DB_PART_NUMBER") "CAP000043701")
        (field (name "DB_VALUE") "100uF")
        (field (name "DB_TOLERANCE") "20%")
        (field (name "DB_VOLTAGE") "6.3V")
        (field (name "DB_MANUFACTURER_PART") "KEMET    C1210C107M9PAC")
      )
      (libsource (lib "Database_Libs1") (part "C"))
    )
    (comp (ref "C423")
      (value "C")
      (footprint "SMD_1210_CAPC3225X270N")
      (fields
        (field (name "DB_PART_NUMBER") "CAP000043701")
        (field (name "DB_VALUE") "100uF")
        (field (name "DB_TOLERANCE") "20%")
        (field (name "DB_VOLTAGE") "6.3V")
        (field (name "DB_MANUFACTURER_PART") "KEMET    C1210C107M9PAC")
      )
      (libsource (lib "Database_Libs1") (part "C"))
    )
    (comp (ref "C424")
      (value "C")
      (footprint "SMD_1210_CAPC3225X270N")
      (fields
        (field (name "DB_PART_NUMBER") "CAP000043701")
        (field (name "DB_VALUE") "100uF")
        (field (name "DB_TOLERANCE") "20%")
        (field (name "DB_VOLTAGE") "6.3V")
        (field (name "DB_MANUFACTURER_PART") "KEMET    C1210C107M9PAC")
      )
      (libsource (lib "Database_Libs1") (part "C"))
    )
    (comp (ref "C425")
      (value "C")
      (footprint "SMD_1210_CAPC3225X270N")
      (fields
        (field (name "DB_PART_NUMBER") "CAP000043701")
        (field (name "DB_VALUE") "100uF")
        (field (name "DB_TOLERANCE") "20%")
        (field (name "DB_VOLTAGE") "6.3V")
        (field (name "DB_MANUFACTURER_PART") "KEMET    C1210C107M9PAC")
      )
      (libsource (lib "Database_Libs1") (part "C"))
    )
    (comp (ref "C426")
      (value "C")
      (footprint "SMD_1210_CAPC3225X270N")
      (fields
        (field (name "DB_PART_NUMBER") "CAP000043701")
        (field (name "DB_VALUE") "100uF")
        (field (name "DB_TOLERANCE") "20%")
        (field (name "DB_VOLTAGE") "6.3V")
        (field (name "DB_MANUFACTURER_PART") "KEMET    C1210C107M9PAC")
      )
      (libsource (lib "Database_Libs1") (part "C"))
    )
    (comp (ref "C427")
      (value "C")
      (footprint "SMD_1210_CAPC3225X270N")
      (fields
        (field (name "DB_PART_NUMBER") "CAP000043701")
        (field (name "DB_VALUE") "100uF")
        (field (name "DB_TOLERANCE") "20%")
        (field (name "DB_VOLTAGE") "6.3V")
        (field (name "DB_MANUFACTURER_PART") "KEMET    C1210C107M9PAC")
      )
      (libsource (lib "Database_Libs1") (part "C"))
    )
    (comp (ref "D10")
      (value "D")
      (footprint "SMD_SOD523_SOD1608X65N")
      (fields
        (field (name "DB_PART_NUMBER") "DDE000001203")
        (field (name "DB_VALUE") "1N4448HWT")
        (field (name "DB_MANUFACTURER_PART") "Diodes        1N4448HWT")
      )
      (libsource (lib "Database_Libs1") (part "D"))
    )
    (comp (ref "D11")
      (value "D")
      (footprint "SMD_SOD523_SOD1608X65N")
      (fields
        (field (name "DB_PART_NUMBER") "DDE000001203")
        (field (name "DB_VALUE") "1N4448HWT")
        (field (name "DB_MANUFACTURER_PART") "Diodes        1N4448HWT")
      )
      (libsource (lib "Database_Libs1") (part "D"))
    )
    (comp (ref "D12")
      (value "D")
      (footprint "SMD_SOD523_SOD1608X65N")
      (fields
        (field (name "DB_PART_NUMBER") "DDE000001203")
        (field (name "DB_VALUE") "1N4448HWT")
        (field (name "DB_MANUFACTURER_PART") "Diodes        1N4448HWT")
      )
      (libsource (lib "Database_Libs1") (part "D"))
    )
    (comp (ref "D13")
      (value "D")
      (footprint "SMD_SOD523_SOD1608X65N")
      (fields
        (field (name "DB_PART_NUMBER") "DDE000001203")
        (field (name "DB_VALUE") "1N4448HWT")
        (field (name "DB_MANUFACTURER_PART") "Diodes        1N4448HWT")
      )
      (libsource (lib "Database_Libs1") (part "D"))
    )
    (comp (ref "D14")
      (value "D")
      (footprint "SMD_SOD523_SOD1608X65N")
      (fields
        (field (name "DB_PART_NUMBER") "DDE000001203")
        (field (name "DB_VALUE") "1N4448HWT")
        (field (name "DB_MANUFACTURER_PART") "Diodes        1N4448HWT")
      )
      (libsource (lib "Database_Libs1") (part "D"))
    )
    (comp (ref "D15")
      (value "D")
      (footprint "SMD_SOD523_SOD1608X65N")
      (fields
        (field (name "DB_PART_NUMBER") "DDE000001203")
        (field (name "DB_VALUE") "1N4448HWT")
        (field (name "DB_MANUFACTURER_PART") "Diodes        1N4448HWT")
      )
      (libsource (lib "Database_Libs1") (part "D"))
    )
    (comp (ref "D16")
      (value "D")
      (footprint "SMD_SOD523_SOD1608X65N")
      (fields
        (field (name "DB_PART_NUMBER") "DDE000001203")
        (field (name "DB_VALUE") "1N4448HWT")
        (field (name "DB_MANUFACTURER_PART") "Diodes        1N4448HWT")
      )
      (libsource (lib "Database_Libs1") (part "D"))
    )
    (comp (ref "D17")
      (value "D")
      (footprint "SMD_SOD523_SOD1608X65N")
      (fields
        (field (name "DB_PART_NUMBER") "DDE000001203")
        (field (name "DB_VALUE") "1N4448HWT")
        (field (name "DB_MANUFACTURER_PART") "Diodes        1N4448HWT")
      )
      (libsource (lib "Database_Libs1") (part "D"))
    )
    (comp (ref "D18")
      (value "D")
      (footprint "SMD_SOD523_SOD1608X65N")
      (fields
        (field (name "DB_PART_NUMBER") "DDE000001203")
        (field (name "DB_VALUE") "1N4448HWT")
        (field (name "DB_MANUFACTURER_PART") "Diodes        1N4448HWT")
      )
      (libsource (lib "Database_Libs1") (part "D"))
    )
    (comp (ref "D19")
      (value "D")
      (footprint "SMD_SOD523_SOD1608X65N")
      (fields
        (field (name "DB_PART_NUMBER") "DDE000001203")
        (field (name "DB_VALUE") "1N4448HWT")
        (field (name "DB_MANUFACTURER_PART") "Diodes        1N4448HWT")
      )
      (libsource (lib "Database_Libs1") (part "D"))
    )
    (comp (ref "D20")
      (value "D")
      (footprint "SMD_SOD523_SOD1608X65N")
      (fields
        (field (name "DB_PART_NUMBER") "DDE000001203")
        (field (name "DB_VALUE") "1N4448HWT")
        (field (name "DB_MANUFACTURER_PART") "Diodes        1N4448HWT")
      )
      (libsource (lib "Database_Libs1") (part "D"))
    )
    (comp (ref "D21")
      (value "D")
      (footprint "SMD_SOD523_SOD1608X65N")
      (fields
        (field (name "DB_PART_NUMBER") "DDE000001203")
        (field (name "DB_VALUE") "1N4448HWT")
        (field (name "DB_MANUFACTURER_PART") "Diodes        1N4448HWT")
      )
      (libsource (lib "Database_Libs1") (part "D"))
    )
    (comp (ref "D22")
      (value "D")
      (footprint "SMD_SOD523_SOD1608X65N")
      (fields
        (field (name "DB_PART_NUMBER") "DDE000001203")
        (field (name "DB_VALUE") "1N4448HWT")
        (field (name "DB_MANUFACTURER_PART") "Diodes        1N4448HWT")
      )
      (libsource (lib "Database_Libs1") (part "D"))
    )
    (comp (ref "D23")
      (value "D")
      (footprint "SMD_SOD523_SOD1608X65N")
      (fields
        (field (name "DB_PART_NUMBER") "DDE000001203")
        (field (name "DB_VALUE") "1N4448HWT")
        (field (name "DB_MANUFACTURER_PART") "Diodes        1N4448HWT")
      )
      (libsource (lib "Database_Libs1") (part "D"))
    )
    (comp (ref "D24")
      (value "D")
      (footprint "SMD_SOD523_SOD1608X65N")
      (fields
        (field (name "DB_PART_NUMBER") "DDE000001203")
        (field (name "DB_VALUE") "1N4448HWT")
        (field (name "DB_MANUFACTURER_PART") "Diodes        1N4448HWT")
      )
      (libsource (lib "Database_Libs1") (part "D"))
    )
    (comp (ref "D25")
      (value "D")
      (footprint "SMD_SOD523_SOD1608X65N")
      (fields
        (field (name "DB_PART_NUMBER") "DDE000001203")
        (field (name "DB_VALUE") "1N4448HWT")
        (field (name "DB_MANUFACTURER_PART") "Diodes        1N4448HWT")
      )
      (libsource (lib "Database_Libs1") (part "D"))
    )
    (comp (ref "L1")
      (value "SLC1480-201MLD")
      (footprint "SMT_INDM135130X800N")
      (libsource (lib "EPIQ_DND_CIS_Library") (part "L"))
    )
    (comp (ref "L2")
      (value "SLC1480-201MLD")
      (footprint "SMT_INDM135130X800N")
      (libsource (lib "EPIQ_DND_CIS_Library") (part "L"))
    )
    (comp (ref "L3")
      (value "SLC1480-201MLD")
      (footprint "SMT_INDM135130X800N")
      (libsource (lib "EPIQ_DND_CIS_Library") (part "L"))
    )
    (comp (ref "L4")
      (value "SLC1480-201MLD")
      (footprint "SMT_INDM135130X800N")
      (libsource (lib "EPIQ_DND_CIS_Library") (part "L"))
    )
    (comp (ref "L5")
      (value "SLC1480-201MLD")
      (footprint "SMT_INDM135130X800N")
      (libsource (lib "EPIQ_DND_CIS_Library") (part "L"))
    )
    (comp (ref "L6")
      (value "SLC1480-201MLD")
      (footprint "SMT_INDM135130X800N")
      (libsource (lib "EPIQ_DND_CIS_Library") (part "L"))
    )
    (comp (ref "L7")
      (value "SLC1480-201MLD")
      (footprint "SMT_INDM135130X800N")
      (libsource (lib "EPIQ_DND_CIS_Library") (part "L"))
    )
    (comp (ref "L8")
      (value "SLC1480-201MLD")
      (footprint "SMT_INDM135130X800N")
      (libsource (lib "EPIQ_DND_CIS_Library") (part "L"))
    )
    (comp (ref "L9")
      (value "SLC1480-201MLD")
      (footprint "SMT_INDM135130X800N")
      (libsource (lib "EPIQ_DND_CIS_Library") (part "L"))
    )
    (comp (ref "L10")
      (value "SLC1480-201MLD")
      (footprint "SMT_INDM135130X800N")
      (libsource (lib "EPIQ_DND_CIS_Library") (part "L"))
    )
    (comp (ref "L11")
      (value "SLC1480-201MLD")
      (footprint "SMT_INDM135130X800N")
      (libsource (lib "EPIQ_DND_CIS_Library") (part "L"))
    )
    (comp (ref "L12")
      (value "SLC1480-201MLD")
      (footprint "SMT_INDM135130X800N")
      (libsource (lib "EPIQ_DND_CIS_Library") (part "L"))
    )
    (comp (ref "L13")
      (value "SLC1480-201MLD")
      (footprint "SMT_INDM135130X800N")
      (libsource (lib "EPIQ_DND_CIS_Library") (part "L"))
    )
    (comp (ref "L14")
      (value "SLC1480-201MLD")
      (footprint "SMT_INDM135130X800N")
      (libsource (lib "EPIQ_DND_CIS_Library") (part "L"))
    )
    (comp (ref "L15")
      (value "SLC1480-201MLD")
      (footprint "SMT_INDM135130X800N")
      (libsource (lib "EPIQ_DND_CIS_Library") (part "L"))
    )
    (comp (ref "L16")
      (value "SLC1480-201MLD")
      (footprint "SMT_INDM135130X800N")
      (libsource (lib "EPIQ_DND_CIS_Library") (part "L"))
    )
    (comp (ref "Q1")
      (value "MOS_N_D1_S1S2S3G4D5D6D7D8")
      (footprint "SMD_SOIC127P600X110-9AN")
      (fields
        (field (name "DB_PART_NUMBER") "TRA000001604")
        (field (name "DB_VALUE") "AP1RA03GMT-HF-3")
        (field (name "DB_MANUFACTURER_PART") "ADVANCED POWER ELECTRONICS CORP      AP1RA03GMT-HF-3")
        (field (name "DB_APPROVED_BY") "VSN")
      )
      (libsource (lib "Database_Libs1") (part "MOS_N_D1_S1S2S3G4D5D6D7D8"))
    )
    (comp (ref "Q2")
      (value "MOS_N_D1_S1S2S3G4D5D6D7D8")
      (footprint "SMD_SOIC127P600X110-9AN")
      (fields
        (field (name "DB_PART_NUMBER") "TRA000001604")
        (field (name "DB_VALUE") "AP1RA03GMT-HF-3")
        (field (name "DB_MANUFACTURER_PART") "ADVANCED POWER ELECTRONICS CORP      AP1RA03GMT-HF-3")
        (field (name "DB_APPROVED_BY") "VSN")
      )
      (libsource (lib "Database_Libs1") (part "MOS_N_D1_S1S2S3G4D5D6D7D8"))
    )
    (comp (ref "Q3")
      (value "MOS_N_D1_S1S2S3G4D5D6D7D8")
      (footprint "SMD_SOIC127P600X110-9AN")
      (fields
        (field (name "DB_PART_NUMBER") "TRA000001604")
        (field (name "DB_VALUE") "AP1RA03GMT-HF-3")
        (field (name "DB_MANUFACTURER_PART") "ADVANCED POWER ELECTRONICS CORP      AP1RA03GMT-HF-3")
        (field (name "DB_APPROVED_BY") "VSN")
      )
      (libsource (lib "Database_Libs1") (part "MOS_N_D1_S1S2S3G4D5D6D7D8"))
    )
    (comp (ref "Q4")
      (value "MOS_N_D1_S1S2S3G4D5D6D7D8")
      (footprint "SMD_SOIC127P600X110-9AN")
      (fields
        (field (name "DB_PART_NUMBER") "TRA000001604")
        (field (name "DB_VALUE") "AP1RA03GMT-HF-3")
        (field (name "DB_MANUFACTURER_PART") "ADVANCED POWER ELECTRONICS CORP      AP1RA03GMT-HF-3")
        (field (name "DB_APPROVED_BY") "VSN")
      )
      (libsource (lib "Database_Libs1") (part "MOS_N_D1_S1S2S3G4D5D6D7D8"))
    )
    (comp (ref "Q5")
      (value "MOS_N_D1_S1S2S3G4D5D6D7D8")
      (footprint "SMD_SOIC127P600X110-9AN")
      (fields
        (field (name "DB_PART_NUMBER") "TRA000001604")
        (field (name "DB_VALUE") "AP1RA03GMT-HF-3")
        (field (name "DB_MANUFACTURER_PART") "ADVANCED POWER ELECTRONICS CORP      AP1RA03GMT-HF-3")
        (field (name "DB_APPROVED_BY") "VSN")
      )
      (libsource (lib "Database_Libs1") (part "MOS_N_D1_S1S2S3G4D5D6D7D8"))
    )
    (comp (ref "Q6")
      (value "MOS_N_D1_S1S2S3G4D5D6D7D8")
      (footprint "SMD_SOIC127P600X110-9AN")
      (fields
        (field (name "DB_PART_NUMBER") "TRA000001604")
        (field (name "DB_VALUE") "AP1RA03GMT-HF-3")
        (field (name "DB_MANUFACTURER_PART") "ADVANCED POWER ELECTRONICS CORP      AP1RA03GMT-HF-3")
        (field (name "DB_APPROVED_BY") "VSN")
      )
      (libsource (lib "Database_Libs1") (part "MOS_N_D1_S1S2S3G4D5D6D7D8"))
    )
    (comp (ref "Q7")
      (value "MOS_N_D1_S1S2S3G4D5D6D7D8")
      (footprint "SMD_SOIC127P600X110-9AN")
      (fields
        (field (name "DB_PART_NUMBER") "TRA000001604")
        (field (name "DB_VALUE") "AP1RA03GMT-HF-3")
        (field (name "DB_MANUFACTURER_PART") "ADVANCED POWER ELECTRONICS CORP      AP1RA03GMT-HF-3")
        (field (name "DB_APPROVED_BY") "VSN")
      )
      (libsource (lib "Database_Libs1") (part "MOS_N_D1_S1S2S3G4D5D6D7D8"))
    )
    (comp (ref "Q8")
      (value "MOS_N_D1_S1S2S3G4D5D6D7D8")
      (footprint "SMD_SOIC127P600X110-9AN")
      (fields
        (field (name "DB_PART_NUMBER") "TRA000001604")
        (field (name "DB_VALUE") "AP1RA03GMT-HF-3")
        (field (name "DB_MANUFACTURER_PART") "ADVANCED POWER ELECTRONICS CORP      AP1RA03GMT-HF-3")
        (field (name "DB_APPROVED_BY") "VSN")
      )
      (libsource (lib "Database_Libs1") (part "MOS_N_D1_S1S2S3G4D5D6D7D8"))
    )
    (comp (ref "Q9")
      (value "MOS_N_D1_S1S2S3G4D5D6D7D8")
      (footprint "SMD_SOIC127P600X110-9AN")
      (fields
        (field (name "DB_PART_NUMBER") "TRA000001604")
        (field (name "DB_VALUE") "AP1RA03GMT-HF-3")
        (field (name "DB_MANUFACTURER_PART") "ADVANCED POWER ELECTRONICS CORP      AP1RA03GMT-HF-3")
        (field (name "DB_APPROVED_BY") "VSN")
      )
      (libsource (lib "Database_Libs1") (part "MOS_N_D1_S1S2S3G4D5D6D7D8"))
    )
    (comp (ref "Q10")
      (value "MOS_N_D1_S1S2S3G4D5D6D7D8")
      (footprint "SMD_SOIC127P600X110-9AN")
      (fields
        (field (name "DB_PART_NUMBER") "TRA000001604")
        (field (name "DB_VALUE") "AP1RA03GMT-HF-3")
        (field (name "DB_MANUFACTURER_PART") "ADVANCED POWER ELECTRONICS CORP      AP1RA03GMT-HF-3")
        (field (name "DB_APPROVED_BY") "VSN")
      )
      (libsource (lib "Database_Libs1") (part "MOS_N_D1_S1S2S3G4D5D6D7D8"))
    )
    (comp (ref "Q11")
      (value "MOS_N_D1_S1S2S3G4D5D6D7D8")
      (footprint "SMD_SOIC127P600X110-9AN")
      (fields
        (field (name "DB_PART_NUMBER") "TRA000001604")
        (field (name "DB_VALUE") "AP1RA03GMT-HF-3")
        (field (name "DB_MANUFACTURER_PART") "ADVANCED POWER ELECTRONICS CORP      AP1RA03GMT-HF-3")
        (field (name "DB_APPROVED_BY") "VSN")
      )
      (libsource (lib "Database_Libs1") (part "MOS_N_D1_S1S2S3G4D5D6D7D8"))
    )
    (comp (ref "Q12")
      (value "MOS_N_D1_S1S2S3G4D5D6D7D8")
      (footprint "SMD_SOIC127P600X110-9AN")
      (fields
        (field (name "DB_PART_NUMBER") "TRA000001604")
        (field (name "DB_VALUE") "AP1RA03GMT-HF-3")
        (field (name "DB_MANUFACTURER_PART") "ADVANCED POWER ELECTRONICS CORP      AP1RA03GMT-HF-3")
        (field (name "DB_APPROVED_BY") "VSN")
      )
      (libsource (lib "Database_Libs1") (part "MOS_N_D1_S1S2S3G4D5D6D7D8"))
    )
    (comp (ref "Q13")
      (value "MOS_N_D1_S1S2S3G4D5D6D7D8")
      (footprint "SMD_SOIC127P600X110-9AN")
      (fields
        (field (name "DB_PART_NUMBER") "TRA000001604")
        (field (name "DB_VALUE") "AP1RA03GMT-HF-3")
        (field (name "DB_MANUFACTURER_PART") "ADVANCED POWER ELECTRONICS CORP      AP1RA03GMT-HF-3")
        (field (name "DB_APPROVED_BY") "VSN")
      )
      (libsource (lib "Database_Libs1") (part "MOS_N_D1_S1S2S3G4D5D6D7D8"))
    )
    (comp (ref "Q14")
      (value "MOS_N_D1_S1S2S3G4D5D6D7D8")
      (footprint "SMD_SOIC127P600X110-9AN")
      (fields
        (field (name "DB_PART_NUMBER") "TRA000001604")
        (field (name "DB_VALUE") "AP1RA03GMT-HF-3")
        (field (name "DB_MANUFACTURER_PART") "ADVANCED POWER ELECTRONICS CORP      AP1RA03GMT-HF-3")
        (field (name "DB_APPROVED_BY") "VSN")
      )
      (libsource (lib "Database_Libs1") (part "MOS_N_D1_S1S2S3G4D5D6D7D8"))
    )
    (comp (ref "Q15")
      (value "MOS_N_D1_S1S2S3G4D5D6D7D8")
      (footprint "SMD_SOIC127P600X110-9AN")
      (fields
        (field (name "DB_PART_NUMBER") "TRA000001604")
        (field (name "DB_VALUE") "AP1RA03GMT-HF-3")
        (field (name "DB_MANUFACTURER_PART") "ADVANCED POWER ELECTRONICS CORP      AP1RA03GMT-HF-3")
        (field (name "DB_APPROVED_BY") "VSN")
      )
      (libsource (lib "Database_Libs1") (part "MOS_N_D1_S1S2S3G4D5D6D7D8"))
    )
    (comp (ref "Q16")
      (value "MOS_N_D1_S1S2S3G4D5D6D7D8")
      (footprint "SMD_SOIC127P600X110-9AN")
      (fields
        (field (name "DB_PART_NUMBER") "TRA000001604")
        (field (name "DB_VALUE") "AP1RA03GMT-HF-3")
        (field (name "DB_MANUFACTURER_PART") "ADVANCED POWER ELECTRONICS CORP      AP1RA03GMT-HF-3")
        (field (name "DB_APPROVED_BY") "VSN")
      )
      (libsource (lib "Database_Libs1") (part "MOS_N_D1_S1S2S3G4D5D6D7D8"))
    )
    (comp (ref "Q17")
      (value "MOS_N_D1_S1S2S3G4D5D6D7D8")
      (footprint "SMD_SOIC127P600X110-9AN")
      (fields
        (field (name "DB_PART_NUMBER") "TRA000001604")
        (field (name "DB_VALUE") "AP1RA03GMT-HF-3")
        (field (name "DB_MANUFACTURER_PART") "ADVANCED POWER ELECTRONICS CORP      AP1RA03GMT-HF-3")
        (field (name "DB_APPROVED_BY") "VSN")
      )
      (libsource (lib "Database_Libs1") (part "MOS_N_D1_S1S2S3G4D5D6D7D8"))
    )
    (comp (ref "Q18")
      (value "MOS_N_D1_S1S2S3G4D5D6D7D8")
      (footprint "SMD_SOIC127P600X110-9AN")
      (fields
        (field (name "DB_PART_NUMBER") "TRA000001604")
        (field (name "DB_VALUE") "AP1RA03GMT-HF-3")
        (field (name "DB_MANUFACTURER_PART") "ADVANCED POWER ELECTRONICS CORP      AP1RA03GMT-HF-3")
        (field (name "DB_APPROVED_BY") "VSN")
      )
      (libsource (lib "Database_Libs1") (part "MOS_N_D1_S1S2S3G4D5D6D7D8"))
    )
    (comp (ref "Q19")
      (value "MOS_N_D1_S1S2S3G4D5D6D7D8")
      (footprint "SMD_SOIC127P600X110-9AN")
      (fields
        (field (name "DB_PART_NUMBER") "TRA000001604")
        (field (name "DB_VALUE") "AP1RA03GMT-HF-3")
        (field (name "DB_MANUFACTURER_PART") "ADVANCED POWER ELECTRONICS CORP      AP1RA03GMT-HF-3")
        (field (name "DB_APPROVED_BY") "VSN")
      )
      (libsource (lib "Database_Libs1") (part "MOS_N_D1_S1S2S3G4D5D6D7D8"))
    )
    (comp (ref "Q20")
      (value "MOS_N_D1_S1S2S3G4D5D6D7D8")
      (footprint "SMD_SOIC127P600X110-9AN")
      (fields
        (field (name "DB_PART_NUMBER") "TRA000001604")
        (field (name "DB_VALUE") "AP1RA03GMT-HF-3")
        (field (name "DB_MANUFACTURER_PART") "ADVANCED POWER ELECTRONICS CORP      AP1RA03GMT-HF-3")
        (field (name "DB_APPROVED_BY") "VSN")
      )
      (libsource (lib "Database_Libs1") (part "MOS_N_D1_S1S2S3G4D5D6D7D8"))
    )
    (comp (ref "Q21")
      (value "MOS_N_D1_S1S2S3G4D5D6D7D8")
      (footprint "SMD_SOIC127P600X110-9AN")
      (fields
        (field (name "DB_PART_NUMBER") "TRA000001604")
        (field (name "DB_VALUE") "AP1RA03GMT-HF-3")
        (field (name "DB_MANUFACTURER_PART") "ADVANCED POWER ELECTRONICS CORP      AP1RA03GMT-HF-3")
        (field (name "DB_APPROVED_BY") "VSN")
      )
      (libsource (lib "Database_Libs1") (part "MOS_N_D1_S1S2S3G4D5D6D7D8"))
    )
    (comp (ref "Q22")
      (value "MOS_N_D1_S1S2S3G4D5D6D7D8")
      (footprint "SMD_SOIC127P600X110-9AN")
      (fields
        (field (name "DB_PART_NUMBER") "TRA000001604")
        (field (name "DB_VALUE") "AP1RA03GMT-HF-3")
        (field (name "DB_MANUFACTURER_PART") "ADVANCED POWER ELECTRONICS CORP      AP1RA03GMT-HF-3")
        (field (name "DB_APPROVED_BY") "VSN")
      )
      (libsource (lib "Database_Libs1") (part "MOS_N_D1_S1S2S3G4D5D6D7D8"))
    )
    (comp (ref "Q23")
      (value "MOS_N_D1_S1S2S3G4D5D6D7D8")
      (footprint "SMD_SOIC127P600X110-9AN")
      (fields
        (field (name "DB_PART_NUMBER") "TRA000001604")
        (field (name "DB_VALUE") "AP1RA03GMT-HF-3")
        (field (name "DB_MANUFACTURER_PART") "ADVANCED POWER ELECTRONICS CORP      AP1RA03GMT-HF-3")
        (field (name "DB_APPROVED_BY") "VSN")
      )
      (libsource (lib "Database_Libs1") (part "MOS_N_D1_S1S2S3G4D5D6D7D8"))
    )
    (comp (ref "Q24")
      (value "MOS_N_D1_S1S2S3G4D5D6D7D8")
      (footprint "SMD_SOIC127P600X110-9AN")
      (fields
        (field (name "DB_PART_NUMBER") "TRA000001604")
        (field (name "DB_VALUE") "AP1RA03GMT-HF-3")
        (field (name "DB_MANUFACTURER_PART") "ADVANCED POWER ELECTRONICS CORP      AP1RA03GMT-HF-3")
        (field (name "DB_APPROVED_BY") "VSN")
      )
      (libsource (lib "Database_Libs1") (part "MOS_N_D1_S1S2S3G4D5D6D7D8"))
    )
    (comp (ref "Q25")
      (value "MOS_N_D1_S1S2S3G4D5D6D7D8")
      (footprint "SMD_SOIC127P600X110-9AN")
      (fields
        (field (name "DB_PART_NUMBER") "TRA000001604")
        (field (name "DB_VALUE") "AP1RA03GMT-HF-3")
        (field (name "DB_MANUFACTURER_PART") "ADVANCED POWER ELECTRONICS CORP      AP1RA03GMT-HF-3")
        (field (name "DB_APPROVED_BY") "VSN")
      )
      (libsource (lib "Database_Libs1") (part "MOS_N_D1_S1S2S3G4D5D6D7D8"))
    )
    (comp (ref "Q26")
      (value "MOS_N_D1_S1S2S3G4D5D6D7D8")
      (footprint "SMD_SOIC127P600X110-9AN")
      (fields
        (field (name "DB_PART_NUMBER") "TRA000001604")
        (field (name "DB_VALUE") "AP1RA03GMT-HF-3")
        (field (name "DB_MANUFACTURER_PART") "ADVANCED POWER ELECTRONICS CORP      AP1RA03GMT-HF-3")
        (field (name "DB_APPROVED_BY") "VSN")
      )
      (libsource (lib "Database_Libs1") (part "MOS_N_D1_S1S2S3G4D5D6D7D8"))
    )
    (comp (ref "Q27")
      (value "MOS_N_D1_S1S2S3G4D5D6D7D8")
      (footprint "SMD_SOIC127P600X110-9AN")
      (fields
        (field (name "DB_PART_NUMBER") "TRA000001604")
        (field (name "DB_VALUE") "AP1RA03GMT-HF-3")
        (field (name "DB_MANUFACTURER_PART") "ADVANCED POWER ELECTRONICS CORP      AP1RA03GMT-HF-3")
        (field (name "DB_APPROVED_BY") "VSN")
      )
      (libsource (lib "Database_Libs1") (part "MOS_N_D1_S1S2S3G4D5D6D7D8"))
    )
    (comp (ref "Q28")
      (value "MOS_N_D1_S1S2S3G4D5D6D7D8")
      (footprint "SMD_SOIC127P600X110-9AN")
      (fields
        (field (name "DB_PART_NUMBER") "TRA000001604")
        (field (name "DB_VALUE") "AP1RA03GMT-HF-3")
        (field (name "DB_MANUFACTURER_PART") "ADVANCED POWER ELECTRONICS CORP      AP1RA03GMT-HF-3")
        (field (name "DB_APPROVED_BY") "VSN")
      )
      (libsource (lib "Database_Libs1") (part "MOS_N_D1_S1S2S3G4D5D6D7D8"))
    )
    (comp (ref "Q29")
      (value "MOS_N_D1_S1S2S3G4D5D6D7D8")
      (footprint "SMD_SOIC127P600X110-9AN")
      (fields
        (field (name "DB_PART_NUMBER") "TRA000001604")
        (field (name "DB_VALUE") "AP1RA03GMT-HF-3")
        (field (name "DB_MANUFACTURER_PART") "ADVANCED POWER ELECTRONICS CORP      AP1RA03GMT-HF-3")
        (field (name "DB_APPROVED_BY") "VSN")
      )
      (libsource (lib "Database_Libs1") (part "MOS_N_D1_S1S2S3G4D5D6D7D8"))
    )
    (comp (ref "Q30")
      (value "MOS_N_D1_S1S2S3G4D5D6D7D8")
      (footprint "SMD_SOIC127P600X110-9AN")
      (fields
        (field (name "DB_PART_NUMBER") "TRA000001604")
        (field (name "DB_VALUE") "AP1RA03GMT-HF-3")
        (field (name "DB_MANUFACTURER_PART") "ADVANCED POWER ELECTRONICS CORP      AP1RA03GMT-HF-3")
        (field (name "DB_APPROVED_BY") "VSN")
      )
      (libsource (lib "Database_Libs1") (part "MOS_N_D1_S1S2S3G4D5D6D7D8"))
    )
    (comp (ref "Q31")
      (value "MOS_N_D1_S1S2S3G4D5D6D7D8")
      (footprint "SMD_SOIC127P600X110-9AN")
      (fields
        (field (name "DB_PART_NUMBER") "TRA000001604")
        (field (name "DB_VALUE") "AP1RA03GMT-HF-3")
        (field (name "DB_MANUFACTURER_PART") "ADVANCED POWER ELECTRONICS CORP      AP1RA03GMT-HF-3")
        (field (name "DB_APPROVED_BY") "VSN")
      )
      (libsource (lib "Database_Libs1") (part "MOS_N_D1_S1S2S3G4D5D6D7D8"))
    )
    (comp (ref "Q32")
      (value "MOS_N_D1_S1S2S3G4D5D6D7D8")
      (footprint "SMD_SOIC127P600X110-9AN")
      (fields
        (field (name "DB_PART_NUMBER") "TRA000001604")
        (field (name "DB_VALUE") "AP1RA03GMT-HF-3")
        (field (name "DB_MANUFACTURER_PART") "ADVANCED POWER ELECTRONICS CORP      AP1RA03GMT-HF-3")
        (field (name "DB_APPROVED_BY") "VSN")
      )
      (libsource (lib "Database_Libs1") (part "MOS_N_D1_S1S2S3G4D5D6D7D8"))
    )
    (comp (ref "Q33")
      (value "MOS_N_D1_S1S2S3G4D5D6D7D8")
      (footprint "SMD_SOIC127P600X110-9AN")
      (fields
        (field (name "DB_PART_NUMBER") "TRA000001604")
        (field (name "DB_VALUE") "AP1RA03GMT-HF-3")
        (field (name "DB_MANUFACTURER_PART") "ADVANCED POWER ELECTRONICS CORP      AP1RA03GMT-HF-3")
        (field (name "DB_APPROVED_BY") "VSN")
      )
      (libsource (lib "Database_Libs1") (part "MOS_N_D1_S1S2S3G4D5D6D7D8"))
    )
    (comp (ref "Q34")
      (value "MOS_N_D1_S1S2S3G4D5D6D7D8")
      (footprint "SMD_SOIC127P600X110-9AN")
      (fields
        (field (name "DB_PART_NUMBER") "TRA000001604")
        (field (name "DB_VALUE") "AP1RA03GMT-HF-3")
        (field (name "DB_MANUFACTURER_PART") "ADVANCED POWER ELECTRONICS CORP      AP1RA03GMT-HF-3")
        (field (name "DB_APPROVED_BY") "VSN")
      )
      (libsource (lib "Database_Libs1") (part "MOS_N_D1_S1S2S3G4D5D6D7D8"))
    )
    (comp (ref "Q35")
      (value "MOS_N_D1_S1S2S3G4D5D6D7D8")
      (footprint "SMD_SOIC127P600X110-9AN")
      (fields
        (field (name "DB_PART_NUMBER") "TRA000001604")
        (field (name "DB_VALUE") "AP1RA03GMT-HF-3")
        (field (name "DB_MANUFACTURER_PART") "ADVANCED POWER ELECTRONICS CORP      AP1RA03GMT-HF-3")
        (field (name "DB_APPROVED_BY") "VSN")
      )
      (libsource (lib "Database_Libs1") (part "MOS_N_D1_S1S2S3G4D5D6D7D8"))
    )
    (comp (ref "Q36")
      (value "MOS_N_D1_S1S2S3G4D5D6D7D8")
      (footprint "SMD_SOIC127P600X110-9AN")
      (fields
        (field (name "DB_PART_NUMBER") "TRA000001604")
        (field (name "DB_VALUE") "AP1RA03GMT-HF-3")
        (field (name "DB_MANUFACTURER_PART") "ADVANCED POWER ELECTRONICS CORP      AP1RA03GMT-HF-3")
        (field (name "DB_APPROVED_BY") "VSN")
      )
      (libsource (lib "Database_Libs1") (part "MOS_N_D1_S1S2S3G4D5D6D7D8"))
    )
    (comp (ref "Q37")
      (value "MOS_N_D1_S1S2S3G4D5D6D7D8")
      (footprint "SMD_SOIC127P600X110-9AN")
      (fields
        (field (name "DB_PART_NUMBER") "TRA000001604")
        (field (name "DB_VALUE") "AP1RA03GMT-HF-3")
        (field (name "DB_MANUFACTURER_PART") "ADVANCED POWER ELECTRONICS CORP      AP1RA03GMT-HF-3")
        (field (name "DB_APPROVED_BY") "VSN")
      )
      (libsource (lib "Database_Libs1") (part "MOS_N_D1_S1S2S3G4D5D6D7D8"))
    )
    (comp (ref "Q38")
      (value "MOS_N_D1_S1S2S3G4D5D6D7D8")
      (footprint "SMD_SOIC127P600X110-9AN")
      (fields
        (field (name "DB_PART_NUMBER") "TRA000001604")
        (field (name "DB_VALUE") "AP1RA03GMT-HF-3")
        (field (name "DB_MANUFACTURER_PART") "ADVANCED POWER ELECTRONICS CORP      AP1RA03GMT-HF-3")
        (field (name "DB_APPROVED_BY") "VSN")
      )
      (libsource (lib "Database_Libs1") (part "MOS_N_D1_S1S2S3G4D5D6D7D8"))
    )
    (comp (ref "Q39")
      (value "MOS_N_D1_S1S2S3G4D5D6D7D8")
      (footprint "SMD_SOIC127P600X110-9AN")
      (fields
        (field (name "DB_PART_NUMBER") "TRA000001604")
        (field (name "DB_VALUE") "AP1RA03GMT-HF-3")
        (field (name "DB_MANUFACTURER_PART") "ADVANCED POWER ELECTRONICS CORP      AP1RA03GMT-HF-3")
        (field (name "DB_APPROVED_BY") "VSN")
      )
      (libsource (lib "Database_Libs1") (part "MOS_N_D1_S1S2S3G4D5D6D7D8"))
    )
    (comp (ref "Q40")
      (value "MOS_N_D1_S1S2S3G4D5D6D7D8")
      (footprint "SMD_SOIC127P600X110-9AN")
      (fields
        (field (name "DB_PART_NUMBER") "TRA000001604")
        (field (name "DB_VALUE") "AP1RA03GMT-HF-3")
        (field (name "DB_MANUFACTURER_PART") "ADVANCED POWER ELECTRONICS CORP      AP1RA03GMT-HF-3")
        (field (name "DB_APPROVED_BY") "VSN")
      )
      (libsource (lib "Database_Libs1") (part "MOS_N_D1_S1S2S3G4D5D6D7D8"))
    )
    (comp (ref "Q41")
      (value "MOS_N_D1_S1S2S3G4D5D6D7D8")
      (footprint "SMD_SOIC127P600X110-9AN")
      (fields
        (field (name "DB_PART_NUMBER") "TRA000001604")
        (field (name "DB_VALUE") "AP1RA03GMT-HF-3")
        (field (name "DB_MANUFACTURER_PART") "ADVANCED POWER ELECTRONICS CORP      AP1RA03GMT-HF-3")
        (field (name "DB_APPROVED_BY") "VSN")
      )
      (libsource (lib "Database_Libs1") (part "MOS_N_D1_S1S2S3G4D5D6D7D8"))
    )
    (comp (ref "Q42")
      (value "MOS_N_D1_S1S2S3G4D5D6D7D8")
      (footprint "SMD_SOIC127P600X110-9AN")
      (fields
        (field (name "DB_PART_NUMBER") "TRA000001604")
        (field (name "DB_VALUE") "AP1RA03GMT-HF-3")
        (field (name "DB_MANUFACTURER_PART") "ADVANCED POWER ELECTRONICS CORP      AP1RA03GMT-HF-3")
        (field (name "DB_APPROVED_BY") "VSN")
      )
      (libsource (lib "Database_Libs1") (part "MOS_N_D1_S1S2S3G4D5D6D7D8"))
    )
    (comp (ref "Q43")
      (value "MOS_N_D1_S1S2S3G4D5D6D7D8")
      (footprint "SMD_SOIC127P600X110-9AN")
      (fields
        (field (name "DB_PART_NUMBER") "TRA000001604")
        (field (name "DB_VALUE") "AP1RA03GMT-HF-3")
        (field (name "DB_MANUFACTURER_PART") "ADVANCED POWER ELECTRONICS CORP      AP1RA03GMT-HF-3")
        (field (name "DB_APPROVED_BY") "VSN")
      )
      (libsource (lib "Database_Libs1") (part "MOS_N_D1_S1S2S3G4D5D6D7D8"))
    )
    (comp (ref "Q44")
      (value "MOS_N_D1_S1S2S3G4D5D6D7D8")
      (footprint "SMD_SOIC127P600X110-9AN")
      (fields
        (field (name "DB_PART_NUMBER") "TRA000001604")
        (field (name "DB_VALUE") "AP1RA03GMT-HF-3")
        (field (name "DB_MANUFACTURER_PART") "ADVANCED POWER ELECTRONICS CORP      AP1RA03GMT-HF-3")
        (field (name "DB_APPROVED_BY") "VSN")
      )
      (libsource (lib "Database_Libs1") (part "MOS_N_D1_S1S2S3G4D5D6D7D8"))
    )
    (comp (ref "Q45")
      (value "MOS_N_D1_S1S2S3G4D5D6D7D8")
      (footprint "SMD_SOIC127P600X110-9AN")
      (fields
        (field (name "DB_PART_NUMBER") "TRA000001604")
        (field (name "DB_VALUE") "AP1RA03GMT-HF-3")
        (field (name "DB_MANUFACTURER_PART") "ADVANCED POWER ELECTRONICS CORP      AP1RA03GMT-HF-3")
        (field (name "DB_APPROVED_BY") "VSN")
      )
      (libsource (lib "Database_Libs1") (part "MOS_N_D1_S1S2S3G4D5D6D7D8"))
    )
    (comp (ref "Q46")
      (value "MOS_N_D1_S1S2S3G4D5D6D7D8")
      (footprint "SMD_SOIC127P600X110-9AN")
      (fields
        (field (name "DB_PART_NUMBER") "TRA000001604")
        (field (name "DB_VALUE") "AP1RA03GMT-HF-3")
        (field (name "DB_MANUFACTURER_PART") "ADVANCED POWER ELECTRONICS CORP      AP1RA03GMT-HF-3")
        (field (name "DB_APPROVED_BY") "VSN")
      )
      (libsource (lib "Database_Libs1") (part "MOS_N_D1_S1S2S3G4D5D6D7D8"))
    )
    (comp (ref "Q47")
      (value "MOS_N_D1_S1S2S3G4D5D6D7D8")
      (footprint "SMD_SOIC127P600X110-9AN")
      (fields
        (field (name "DB_PART_NUMBER") "TRA000001604")
        (field (name "DB_VALUE") "AP1RA03GMT-HF-3")
        (field (name "DB_MANUFACTURER_PART") "ADVANCED POWER ELECTRONICS CORP      AP1RA03GMT-HF-3")
        (field (name "DB_APPROVED_BY") "VSN")
      )
      (libsource (lib "Database_Libs1") (part "MOS_N_D1_S1S2S3G4D5D6D7D8"))
    )
    (comp (ref "Q48")
      (value "MOS_N_D1_S1S2S3G4D5D6D7D8")
      (footprint "SMD_SOIC127P600X110-9AN")
      (fields
        (field (name "DB_PART_NUMBER") "TRA000001604")
        (field (name "DB_VALUE") "AP1RA03GMT-HF-3")
        (field (name "DB_MANUFACTURER_PART") "ADVANCED POWER ELECTRONICS CORP      AP1RA03GMT-HF-3")
        (field (name "DB_APPROVED_BY") "VSN")
      )
      (libsource (lib "Database_Libs1") (part "MOS_N_D1_S1S2S3G4D5D6D7D8"))
    )
    (comp (ref "U11")
      (value "IC_LTC4449")
      (footprint "SMD_SON45P300X200X80-9N")
      (fields
        (field (name "DB_PART_NUMBER") "DRV000000079")
        (field (name "DB_VALUE") "LTC4449EDCB#TRPBF")
        (field (name "DB_MANUFACTURER_PART") "LINEAR       LTC4449EDCB#TRPBF")
        (field (name "DB_APPROVED_BY") "VSN")
      )
      (libsource (lib "Database_Libs1") (part "IC_LTC4449"))
    )
    (comp (ref "U12")
      (value "IC_LTC4449")
      (footprint "SMD_SON45P300X200X80-9N")
      (fields
        (field (name "DB_PART_NUMBER") "DRV000000079")
        (field (name "DB_VALUE") "LTC4449EDCB#TRPBF")
        (field (name "DB_MANUFACTURER_PART") "LINEAR       LTC4449EDCB#TRPBF")
        (field (name "DB_APPROVED_BY") "VSN")
      )
      (libsource (lib "Database_Libs1") (part "IC_LTC4449"))
    )
    (comp (ref "U13")
      (value "IC_LTC4449")
      (footprint "SMD_SON45P300X200X80-9N")
      (fields
        (field (name "DB_PART_NUMBER") "DRV000000079")
        (field (name "DB_VALUE") "LTC4449EDCB#TRPBF")
        (field (name "DB_MANUFACTURER_PART") "LINEAR       LTC4449EDCB#TRPBF")
        (field (name "DB_APPROVED_BY") "VSN")
      )
      (libsource (lib "Database_Libs1") (part "IC_LTC4449"))
    )
    (comp (ref "U14")
      (value "IC_LTC4449")
      (footprint "SMD_SON45P300X200X80-9N")
      (fields
        (field (name "DB_PART_NUMBER") "DRV000000079")
        (field (name "DB_VALUE") "LTC4449EDCB#TRPBF")
        (field (name "DB_MANUFACTURER_PART") "LINEAR       LTC4449EDCB#TRPBF")
        (field (name "DB_APPROVED_BY") "VSN")
      )
      (libsource (lib "Database_Libs1") (part "IC_LTC4449"))
    )
    (comp (ref "U15")
      (value "IC_LTC4449")
      (footprint "SMD_SON45P300X200X80-9N")
      (fields
        (field (name "DB_PART_NUMBER") "DRV000000079")
        (field (name "DB_VALUE") "LTC4449EDCB#TRPBF")
        (field (name "DB_MANUFACTURER_PART") "LINEAR       LTC4449EDCB#TRPBF")
        (field (name "DB_APPROVED_BY") "VSN")
      )
      (libsource (lib "Database_Libs1") (part "IC_LTC4449"))
    )
    (comp (ref "U16")
      (value "IC_LTC4449")
      (footprint "SMD_SON45P300X200X80-9N")
      (fields
        (field (name "DB_PART_NUMBER") "DRV000000079")
        (field (name "DB_VALUE") "LTC4449EDCB#TRPBF")
        (field (name "DB_MANUFACTURER_PART") "LINEAR       LTC4449EDCB#TRPBF")
        (field (name "DB_APPROVED_BY") "VSN")
      )
      (libsource (lib "Database_Libs1") (part "IC_LTC4449"))
    )
    (comp (ref "U17")
      (value "IC_LTC4449")
      (footprint "SMD_SON45P300X200X80-9N")
      (fields
        (field (name "DB_PART_NUMBER") "DRV000000079")
        (field (name "DB_VALUE") "LTC4449EDCB#TRPBF")
        (field (name "DB_MANUFACTURER_PART") "LINEAR       LTC4449EDCB#TRPBF")
        (field (name "DB_APPROVED_BY") "VSN")
      )
      (libsource (lib "Database_Libs1") (part "IC_LTC4449"))
    )
    (comp (ref "U18")
      (value "IC_LTC4449")
      (footprint "SMD_SON45P300X200X80-9N")
      (fields
        (field (name "DB_PART_NUMBER") "DRV000000079")
        (field (name "DB_VALUE") "LTC4449EDCB#TRPBF")
        (field (name "DB_MANUFACTURER_PART") "LINEAR       LTC4449EDCB#TRPBF")
        (field (name "DB_APPROVED_BY") "VSN")
      )
      (libsource (lib "Database_Libs1") (part "IC_LTC4449"))
    )
    (comp (ref "U19")
      (value "IC_LTC4449")
      (footprint "SMD_SON45P300X200X80-9N")
      (fields
        (field (name "DB_PART_NUMBER") "DRV000000079")
        (field (name "DB_VALUE") "LTC4449EDCB#TRPBF")
        (field (name "DB_MANUFACTURER_PART") "LINEAR       LTC4449EDCB#TRPBF")
        (field (name "DB_APPROVED_BY") "VSN")
      )
      (libsource (lib "Database_Libs1") (part "IC_LTC4449"))
    )
    (comp (ref "U20")
      (value "IC_LTC4449")
      (footprint "SMD_SON45P300X200X80-9N")
      (fields
        (field (name "DB_PART_NUMBER") "DRV000000079")
        (field (name "DB_VALUE") "LTC4449EDCB#TRPBF")
        (field (name "DB_MANUFACTURER_PART") "LINEAR       LTC4449EDCB#TRPBF")
        (field (name "DB_APPROVED_BY") "VSN")
      )
      (libsource (lib "Database_Libs1") (part "IC_LTC4449"))
    )
    (comp (ref "U21")
      (value "IC_LTC4449")
      (footprint "SMD_SON45P300X200X80-9N")
      (fields
        (field (name "DB_PART_NUMBER") "DRV000000079")
        (field (name "DB_VALUE") "LTC4449EDCB#TRPBF")
        (field (name "DB_MANUFACTURER_PART") "LINEAR       LTC4449EDCB#TRPBF")
        (field (name "DB_APPROVED_BY") "VSN")
      )
      (libsource (lib "Database_Libs1") (part "IC_LTC4449"))
    )
    (comp (ref "U22")
      (value "IC_LTC4449")
      (footprint "SMD_SON45P300X200X80-9N")
      (fields
        (field (name "DB_PART_NUMBER") "DRV000000079")
        (field (name "DB_VALUE") "LTC4449EDCB#TRPBF")
        (field (name "DB_MANUFACTURER_PART") "LINEAR       LTC4449EDCB#TRPBF")
        (field (name "DB_APPROVED_BY") "VSN")
      )
      (libsource (lib "Database_Libs1") (part "IC_LTC4449"))
    )
    (comp (ref "U23")
      (value "IC_LTC4449")
      (footprint "SMD_SON45P300X200X80-9N")
      (fields
        (field (name "DB_PART_NUMBER") "DRV000000079")
        (field (name "DB_VALUE") "LTC4449EDCB#TRPBF")
        (field (name "DB_MANUFACTURER_PART") "LINEAR       LTC4449EDCB#TRPBF")
        (field (name "DB_APPROVED_BY") "VSN")
      )
      (libsource (lib "Database_Libs1") (part "IC_LTC4449"))
    )
    (comp (ref "U24")
      (value "IC_LTC4449")
      (footprint "SMD_SON45P300X200X80-9N")
      (fields
        (field (name "DB_PART_NUMBER") "DRV000000079")
        (field (name "DB_VALUE") "LTC4449EDCB#TRPBF")
        (field (name "DB_MANUFACTURER_PART") "LINEAR       LTC4449EDCB#TRPBF")
        (field (name "DB_APPROVED_BY") "VSN")
      )
      (libsource (lib "Database_Libs1") (part "IC_LTC4449"))
    )
    (comp (ref "U25")
      (value "IC_LTC4449")
      (footprint "SMD_SON45P300X200X80-9N")
      (fields
        (field (name "DB_PART_NUMBER") "DRV000000079")
        (field (name "DB_VALUE") "LTC4449EDCB#TRPBF")
        (field (name "DB_MANUFACTURER_PART") "LINEAR       LTC4449EDCB#TRPBF")
        (field (name "DB_APPROVED_BY") "VSN")
      )
      (libsource (lib "Database_Libs1") (part "IC_LTC4449"))
    )
    (comp (ref "U26")
      (value "IC_LTC4449")
      (footprint "SMD_SON45P300X200X80-9N")
      (fields
        (field (name "DB_PART_NUMBER") "DRV000000079")
        (field (name "DB_VALUE") "LTC4449EDCB#TRPBF")
        (field (name "DB_MANUFACTURER_PART") "LINEAR       LTC4449EDCB#TRPBF")
        (field (name "DB_APPROVED_BY") "VSN")
      )
      (libsource (lib "Database_Libs1") (part "IC_LTC4449"))
    )
  )
  (nets
    (net (code "1") (name "/1V") (class "Default")
      (node (ref "C100") (pin "2") (pinfunction "2_2") (pintype "passive"))
      (node (ref "C103") (pin "2") (pinfunction "2_2") (pintype "passive"))
      (node (ref "C104") (pin "2") (pinfunction "2_2") (pintype "passive"))
      (node (ref "C105") (pin "2") (pinfunction "2_2") (pintype "passive"))
      (node (ref "C108") (pin "2") (pinfunction "2_2") (pintype "passive"))
      (node (ref "C109") (pin "2") (pinfunction "2_2") (pintype "passive"))
      (node (ref "C110") (pin "2") (pinfunction "2_2") (pintype "passive"))
      (node (ref "C113") (pin "2") (pinfunction "2_2") (pintype "passive"))
      (node (ref "C114") (pin "2") (pinfunction "2_2") (pintype "passive"))
      (node (ref "C115") (pin "2") (pinfunction "2_2") (pintype "passive"))
      (node (ref "C130") (pin "2") (pinfunction "2_2") (pintype "passive"))
      (node (ref "C131") (pin "2") (pinfunction "2_2") (pintype "passive"))
      (node (ref "C132") (pin "2") (pinfunction "2_2") (pintype "passive"))
      (node (ref "C135") (pin "2") (pinfunction "2_2") (pintype "passive"))
      (node (ref "C136") (pin "2") (pinfunction "2_2") (pintype "passive"))
      (node (ref "C137") (pin "2") (pinfunction "2_2") (pintype "passive"))
      (node (ref "C140") (pin "2") (pinfunction "2_2") (pintype "passive"))
      (node (ref "C141") (pin "2") (pinfunction "2_2") (pintype "passive"))
      (node (ref "C142") (pin "2") (pinfunction "2_2") (pintype "passive"))
      (node (ref "C145") (pin "2") (pinfunction "2_2") (pintype "passive"))
      (node (ref "C146") (pin "2") (pinfunction "2_2") (pintype "passive"))
      (node (ref "C147") (pin "2") (pinfunction "2_2") (pintype "passive"))
      (node (ref "C236") (pin "2") (pinfunction "2_2") (pintype "passive"))
      (node (ref "C34") (pin "2") (pinfunction "2_2") (pintype "passive"))
      (node (ref "C35") (pin "2") (pinfunction "2_2") (pintype "passive"))
      (node (ref "C350") (pin "2") (pinfunction "2_2") (pintype "passive"))
      (node (ref "C351") (pin "2") (pinfunction "2_2") (pintype "passive"))
      (node (ref "C352") (pin "2") (pinfunction "2_2") (pintype "passive"))
      (node (ref "C355") (pin "2") (pinfunction "2_2") (pintype "passive"))
      (node (ref "C356") (pin "2") (pinfunction "2_2") (pintype "passive"))
      (node (ref "C357") (pin "2") (pinfunction "2_2") (pintype "passive"))
      (node (ref "C360") (pin "2") (pinfunction "2_2") (pintype "passive"))
      (node (ref "C361") (pin "2") (pinfunction "2_2") (pintype "passive"))
      (node (ref "C362") (pin "2") (pinfunction "2_2") (pintype "passive"))
      (node (ref "C365") (pin "2") (pinfunction "2_2") (pintype "passive"))
      (node (ref "C366") (pin "2") (pinfunction "2_2") (pintype "passive"))
      (node (ref "C367") (pin "2") (pinfunction "2_2") (pintype "passive"))
      (node (ref "C370") (pin "2") (pinfunction "2_2") (pintype "passive"))
      (node (ref "C371") (pin "2") (pinfunction "2_2") (pintype "passive"))
      (node (ref "C372") (pin "2") (pinfunction "2_2") (pintype "passive"))
      (node (ref "C375") (pin "2") (pinfunction "2_2") (pintype "passive"))
      (node (ref "C376") (pin "2") (pinfunction "2_2") (pintype "passive"))
      (node (ref "C377") (pin "2") (pinfunction "2_2") (pintype "passive"))
      (node (ref "C380") (pin "2") (pinfunction "2_2") (pintype "passive"))
      (node (ref "C381") (pin "2") (pinfunction "2_2") (pintype "passive"))
      (node (ref "C382") (pin "2") (pinfunction "2_2") (pintype "passive"))
      (node (ref "C385") (pin "2") (pinfunction "2_2") (pintype "passive"))
      (node (ref "C386") (pin "2") (pinfunction "2_2") (pintype "passive"))
      (node (ref "C387") (pin "2") (pinfunction "2_2") (pintype "passive"))
      (node (ref "C388") (pin "2") (pinfunction "2_2") (pintype "passive"))
      (node (ref "C389") (pin "2") (pinfunction "2_2") (pintype "passive"))
      (node (ref "C39") (pin "2") (pinfunction "2_2") (pintype "passive"))
      (node (ref "C390") (pin "2") (pinfunction "2_2") (pintype "passive"))
      (node (ref "C393") (pin "2") (pinfunction "2_2") (pintype "passive"))
      (node (ref "C394") (pin "2") (pinfunction "2_2") (pintype "passive"))
      (node (ref "C395") (pin "2") (pinfunction "2_2") (pintype "passive"))
      (node (ref "C396") (pin "2") (pinfunction "2_2") (pintype "passive"))
      (node (ref "C397") (pin "2") (pinfunction "2_2") (pintype "passive"))
      (node (ref "C398") (pin "2") (pinfunction "2_2") (pintype "passive"))
      (node (ref "C399") (pin "2") (pinfunction "2_2") (pintype "passive"))
      (node (ref "C40") (pin "2") (pinfunction "2_2") (pintype "passive"))
      (node (ref "C400") (pin "2") (pinfunction "2_2") (pintype "passive"))
      (node (ref "C401") (pin "2") (pinfunction "2_2") (pintype "passive"))
      (node (ref "C408") (pin "2") (pinfunction "2_2") (pintype "passive"))
      (node (ref "C409") (pin "2") (pinfunction "2_2") (pintype "passive"))
      (node (ref "C41") (pin "2") (pinfunction "2_2") (pintype "passive"))
      (node (ref "C410") (pin "2") (pinfunction "2_2") (pintype "passive"))
      (node (ref "C411") (pin "2") (pinfunction "2_2") (pintype "passive"))
      (node (ref "C412") (pin "2") (pinfunction "2_2") (pintype "passive"))
      (node (ref "C413") (pin "2") (pinfunction "2_2") (pintype "passive"))
      (node (ref "C414") (pin "2") (pinfunction "2_2") (pintype "passive"))
      (node (ref "C415") (pin "2") (pinfunction "2_2") (pintype "passive"))
      (node (ref "C416") (pin "2") (pinfunction "2_2") (pintype "passive"))
      (node (ref "C417") (pin "2") (pinfunction "2_2") (pintype "passive"))
      (node (ref "C418") (pin "2") (pinfunction "2_2") (pintype "passive"))
      (node (ref "C419") (pin "2") (pinfunction "2_2") (pintype "passive"))
      (node (ref "C44") (pin "2") (pinfunction "2_2") (pintype "passive"))
      (node (ref "C45") (pin "2") (pinfunction "2_2") (pintype "passive"))
      (node (ref "C46") (pin "2") (pinfunction "2_2") (pintype "passive"))
      (node (ref "C49") (pin "2") (pinfunction "2_2") (pintype "passive"))
      (node (ref "C50") (pin "2") (pinfunction "2_2") (pintype "passive"))
      (node (ref "C51") (pin "2") (pinfunction "2_2") (pintype "passive"))
      (node (ref "C66") (pin "2") (pinfunction "2_2") (pintype "passive"))
      (node (ref "C67") (pin "2") (pinfunction "2_2") (pintype "passive"))
      (node (ref "C68") (pin "2") (pinfunction "2_2") (pintype "passive"))
      (node (ref "C71") (pin "2") (pinfunction "2_2") (pintype "passive"))
      (node (ref "C72") (pin "2") (pinfunction "2_2") (pintype "passive"))
      (node (ref "C73") (pin "2") (pinfunction "2_2") (pintype "passive"))
      (node (ref "C76") (pin "2") (pinfunction "2_2") (pintype "passive"))
      (node (ref "C77") (pin "2") (pinfunction "2_2") (pintype "passive"))
      (node (ref "C78") (pin "2") (pinfunction "2_2") (pintype "passive"))
      (node (ref "C81") (pin "2") (pinfunction "2_2") (pintype "passive"))
      (node (ref "C82") (pin "2") (pinfunction "2_2") (pintype "passive"))
      (node (ref "C83") (pin "2") (pinfunction "2_2") (pintype "passive"))
      (node (ref "C98") (pin "2") (pinfunction "2_2") (pintype "passive"))
      (node (ref "C99") (pin "2") (pinfunction "2_2") (pintype "passive"))
      (node (ref "L1") (pin "2") (pinfunction "2_2") (pintype "passive"))
      (node (ref "L10") (pin "2") (pinfunction "2_2") (pintype "passive"))
      (node (ref "L11") (pin "2") (pinfunction "2_2") (pintype "passive"))
      (node (ref "L12") (pin "2") (pinfunction "2_2") (pintype "passive"))
      (node (ref "L13") (pin "2") (pinfunction "2_2") (pintype "passive"))
      (node (ref "L14") (pin "2") (pinfunction "2_2") (pintype "passive"))
      (node (ref "L15") (pin "2") (pinfunction "2_2") (pintype "passive"))
      (node (ref "L16") (pin "2") (pinfunction "2_2") (pintype "passive"))
      (node (ref "L2") (pin "2") (pinfunction "2_2") (pintype "passive"))
      (node (ref "L3") (pin "2") (pinfunction "2_2") (pintype "passive"))
      (node (ref "L4") (pin "2") (pinfunction "2_2") (pintype "passive"))
      (node (ref "L5") (pin "2") (pinfunction "2_2") (pintype "passive"))
      (node (ref "L6") (pin "2") (pinfunction "2_2") (pintype "passive"))
      (node (ref "L7") (pin "2") (pinfunction "2_2") (pintype "passive"))
      (node (ref "L8") (pin "2") (pinfunction "2_2") (pintype "passive"))
      (node (ref "L9") (pin "2") (pinfunction "2_2") (pintype "passive"))
    )
    (net (code "2") (name "/3.3V") (class "Default")
      (node (ref "C120") (pin "1") (pinfunction "1_1") (pintype "passive"))
      (node (ref "C121") (pin "1") (pinfunction "1_1") (pintype "passive"))
      (node (ref "C122") (pin "1") (pinfunction "1_1") (pintype "passive"))
      (node (ref "C123") (pin "1") (pinfunction "1_1") (pintype "passive"))
      (node (ref "C24") (pin "1") (pinfunction "1_1") (pintype "passive"))
      (node (ref "C25") (pin "1") (pinfunction "1_1") (pintype "passive"))
      (node (ref "C26") (pin "1") (pinfunction "1_1") (pintype "passive"))
      (node (ref "C27") (pin "1") (pinfunction "1_1") (pintype "passive"))
      (node (ref "C56") (pin "1") (pinfunction "1_1") (pintype "passive"))
      (node (ref "C57") (pin "1") (pinfunction "1_1") (pintype "passive"))
      (node (ref "C58") (pin "1") (pinfunction "1_1") (pintype "passive"))
      (node (ref "C59") (pin "1") (pinfunction "1_1") (pintype "passive"))
      (node (ref "C88") (pin "1") (pinfunction "1_1") (pintype "passive"))
      (node (ref "C89") (pin "1") (pinfunction "1_1") (pintype "passive"))
      (node (ref "C90") (pin "1") (pinfunction "1_1") (pintype "passive"))
      (node (ref "C91") (pin "1") (pinfunction "1_1") (pintype "passive"))
      (node (ref "U11") (pin "6") (pinfunction "VLOGIC_6") (pintype "passive"))
      (node (ref "U12") (pin "6") (pinfunction "VLOGIC_6") (pintype "passive"))
      (node (ref "U13") (pin "6") (pinfunction "VLOGIC_6") (pintype "passive"))
      (node (ref "U14") (pin "6") (pinfunction "VLOGIC_6") (pintype "passive"))
      (node (ref "U15") (pin "6") (pinfunction "VLOGIC_6") (pintype "passive"))
      (node (ref "U16") (pin "6") (pinfunction "VLOGIC_6") (pintype "passive"))
      (node (ref "U17") (pin "6") (pinfunction "VLOGIC_6") (pintype "passive"))
      (node (ref "U18") (pin "6") (pinfunction "VLOGIC_6") (pintype "passive"))
      (node (ref "U19") (pin "6") (pinfunction "VLOGIC_6") (pintype "passive"))
      (node (ref "U20") (pin "6") (pinfunction "VLOGIC_6") (pintype "passive"))
      (node (ref "U21") (pin "6") (pinfunction "VLOGIC_6") (pintype "passive"))
      (node (ref "U22") (pin "6") (pinfunction "VLOGIC_6") (pintype "passive"))
      (node (ref "U23") (pin "6") (pinfunction "VLOGIC_6") (pintype "passive"))
      (node (ref "U24") (pin "6") (pinfunction "VLOGIC_6") (pintype "passive"))
      (node (ref "U25") (pin "6") (pinfunction "VLOGIC_6") (pintype "passive"))
      (node (ref "U26") (pin "6") (pinfunction "VLOGIC_6") (pintype "passive"))
    )
    (net (code "3") (name "/5.0V") (class "Default")
      (node (ref "C116") (pin "2") (pinfunction "2_2") (pintype "passive"))
      (node (ref "C117") (pin "2") (pinfunction "2_2") (pintype "passive"))
      (node (ref "C118") (pin "2") (pinfunction "2_2") (pintype "passive"))
      (node (ref "C119") (pin "2") (pinfunction "2_2") (pintype "passive"))
      (node (ref "C20") (pin "2") (pinfunction "2_2") (pintype "passive"))
      (node (ref "C21") (pin "2") (pinfunction "2_2") (pintype "passive"))
      (node (ref "C22") (pin "2") (pinfunction "2_2") (pintype "passive"))
      (node (ref "C23") (pin "2") (pinfunction "2_2") (pintype "passive"))
      (node (ref "C52") (pin "2") (pinfunction "2_2") (pintype "passive"))
      (node (ref "C53") (pin "2") (pinfunction "2_2") (pintype "passive"))
      (node (ref "C54") (pin "2") (pinfunction "2_2") (pintype "passive"))
      (node (ref "C55") (pin "2") (pinfunction "2_2") (pintype "passive"))
      (node (ref "C84") (pin "2") (pinfunction "2_2") (pintype "passive"))
      (node (ref "C85") (pin "2") (pinfunction "2_2") (pintype "passive"))
      (node (ref "C86") (pin "2") (pinfunction "2_2") (pintype "passive"))
      (node (ref "C87") (pin "2") (pinfunction "2_2") (pintype "passive"))
      (node (ref "D10") (pin "2") (pinfunction "A_2") (pintype "passive"))
      (node (ref "D11") (pin "2") (pinfunction "A_2") (pintype "passive"))
      (node (ref "D12") (pin "2") (pinfunction "A_2") (pintype "passive"))
      (node (ref "D13") (pin "2") (pinfunction "A_2") (pintype "passive"))
      (node (ref "D14") (pin "2") (pinfunction "A_2") (pintype "passive"))
      (node (ref "D15") (pin "2") (pinfunction "A_2") (pintype "passive"))
      (node (ref "D16") (pin "2") (pinfunction "A_2") (pintype "passive"))
      (node (ref "D17") (pin "2") (pinfunction "A_2") (pintype "passive"))
      (node (ref "D18") (pin "2") (pinfunction "A_2") (pintype "passive"))
      (node (ref "D19") (pin "2") (pinfunction "A_2") (pintype "passive"))
      (node (ref "D20") (pin "2") (pinfunction "A_2") (pintype "passive"))
      (node (ref "D21") (pin "2") (pinfunction "A_2") (pintype "passive"))
      (node (ref "D22") (pin "2") (pinfunction "A_2") (pintype "passive"))
      (node (ref "D23") (pin "2") (pinfunction "A_2") (pintype "passive"))
      (node (ref "D24") (pin "2") (pinfunction "A_2") (pintype "passive"))
      (node (ref "D25") (pin "2") (pinfunction "A_2") (pintype "passive"))
      (node (ref "U11") (pin "7") (pinfunction "VCC_7") (pintype "passive"))
      (node (ref "U12") (pin "7") (pinfunction "VCC_7") (pintype "passive"))
      (node (ref "U13") (pin "7") (pinfunction "VCC_7") (pintype "passive"))
      (node (ref "U14") (pin "7") (pinfunction "VCC_7") (pintype "passive"))
      (node (ref "U15") (pin "7") (pinfunction "VCC_7") (pintype "passive"))
      (node (ref "U16") (pin "7") (pinfunction "VCC_7") (pintype "passive"))
      (node (ref "U17") (pin "7") (pinfunction "VCC_7") (pintype "passive"))
      (node (ref "U18") (pin "7") (pinfunction "VCC_7") (pintype "passive"))
      (node (ref "U19") (pin "7") (pinfunction "VCC_7") (pintype "passive"))
      (node (ref "U20") (pin "7") (pinfunction "VCC_7") (pintype "passive"))
      (node (ref "U21") (pin "7") (pinfunction "VCC_7") (pintype "passive"))
      (node (ref "U22") (pin "7") (pinfunction "VCC_7") (pintype "passive"))
      (node (ref "U23") (pin "7") (pinfunction "VCC_7") (pintype "passive"))
      (node (ref "U24") (pin "7") (pinfunction "VCC_7") (pintype "passive"))
      (node (ref "U25") (pin "7") (pinfunction "VCC_7") (pintype "passive"))
      (node (ref "U26") (pin "7") (pinfunction "VCC_7") (pintype "passive"))
    )
    (net (code "4") (name "/12V") (class "Default")
      (node (ref "C101") (pin "2") (pinfunction "2_2") (pintype "passive"))
      (node (ref "C102") (pin "2") (pinfunction "2_2") (pintype "passive"))
      (node (ref "C106") (pin "2") (pinfunction "2_2") (pintype "passive"))
      (node (ref "C107") (pin "2") (pinfunction "2_2") (pintype "passive"))
      (node (ref "C111") (pin "2") (pinfunction "2_2") (pintype "passive"))
      (node (ref "C112") (pin "2") (pinfunction "2_2") (pintype "passive"))
      (node (ref "C128") (pin "2") (pinfunction "2_2") (pintype "passive"))
      (node (ref "C129") (pin "2") (pinfunction "2_2") (pintype "passive"))
      (node (ref "C133") (pin "2") (pinfunction "2_2") (pintype "passive"))
      (node (ref "C134") (pin "2") (pinfunction "2_2") (pintype "passive"))
      (node (ref "C138") (pin "2") (pinfunction "2_2") (pintype "passive"))
      (node (ref "C139") (pin "2") (pinfunction "2_2") (pintype "passive"))
      (node (ref "C143") (pin "2") (pinfunction "2_2") (pintype "passive"))
      (node (ref "C144") (pin "2") (pinfunction "2_2") (pintype "passive"))
      (node (ref "C32") (pin "2") (pinfunction "2_2") (pintype "passive"))
      (node (ref "C33") (pin "2") (pinfunction "2_2") (pintype "passive"))
      (node (ref "C348") (pin "2") (pinfunction "2_2") (pintype "passive"))
      (node (ref "C349") (pin "2") (pinfunction "2_2") (pintype "passive"))
      (node (ref "C353") (pin "2") (pinfunction "2_2") (pintype "passive"))
      (node (ref "C354") (pin "2") (pinfunction "2_2") (pintype "passive"))
      (node (ref "C358") (pin "2") (pinfunction "2_2") (pintype "passive"))
      (node (ref "C359") (pin "2") (pinfunction "2_2") (pintype "passive"))
      (node (ref "C363") (pin "2") (pinfunction "2_2") (pintype "passive"))
      (node (ref "C364") (pin "2") (pinfunction "2_2") (pintype "passive"))
      (node (ref "C368") (pin "2") (pinfunction "2_2") (pintype "passive"))
      (node (ref "C369") (pin "2") (pinfunction "2_2") (pintype "passive"))
      (node (ref "C37") (pin "2") (pinfunction "2_2") (pintype "passive"))
      (node (ref "C373") (pin "2") (pinfunction "2_2") (pintype "passive"))
      (node (ref "C374") (pin "2") (pinfunction "2_2") (pintype "passive"))
      (node (ref "C378") (pin "2") (pinfunction "2_2") (pintype "passive"))
      (node (ref "C379") (pin "2") (pinfunction "2_2") (pintype "passive"))
      (node (ref "C38") (pin "2") (pinfunction "2_2") (pintype "passive"))
      (node (ref "C383") (pin "2") (pinfunction "2_2") (pintype "passive"))
      (node (ref "C384") (pin "2") (pinfunction "2_2") (pintype "passive"))
      (node (ref "C391") (pin "2") (pinfunction "2_2") (pintype "passive"))
      (node (ref "C392") (pin "2") (pinfunction "2_2") (pintype "passive"))
      (node (ref "C402") (pin "2") (pinfunction "2_2") (pintype "passive"))
      (node (ref "C403") (pin "2") (pinfunction "2_2") (pintype "passive"))
      (node (ref "C404") (pin "2") (pinfunction "2_2") (pintype "passive"))
      (node (ref "C405") (pin "2") (pinfunction "2_2") (pintype "passive"))
      (node (ref "C406") (pin "2") (pinfunction "2_2") (pintype "passive"))
      (node (ref "C407") (pin "2") (pinfunction "2_2") (pintype "passive"))
      (node (ref "C42") (pin "2") (pinfunction "2_2") (pintype "passive"))
      (node (ref "C420") (pin "2") (pinfunction "2_2") (pintype "passive"))
      (node (ref "C421") (pin "2") (pinfunction "2_2") (pintype "passive"))
      (node (ref "C422") (pin "2") (pinfunction "2_2") (pintype "passive"))
      (node (ref "C423") (pin "2") (pinfunction "2_2") (pintype "passive"))
      (node (ref "C424") (pin "2") (pinfunction "2_2") (pintype "passive"))
      (node (ref "C425") (pin "2") (pinfunction "2_2") (pintype "passive"))
      (node (ref "C426") (pin "2") (pinfunction "2_2") (pintype "passive"))
      (node (ref "C427") (pin "2") (pinfunction "2_2") (pintype "passive"))
      (node (ref "C43") (pin "2") (pinfunction "2_2") (pintype "passive"))
      (node (ref "C47") (pin "2") (pinfunction "2_2") (pintype "passive"))
      (node (ref "C48") (pin "2") (pinfunction "2_2") (pintype "passive"))
      (node (ref "C64") (pin "2") (pinfunction "2_2") (pintype "passive"))
      (node (ref "C65") (pin "2") (pinfunction "2_2") (pintype "passive"))
      (node (ref "C69") (pin "2") (pinfunction "2_2") (pintype "passive"))
      (node (ref "C70") (pin "2") (pinfunction "2_2") (pintype "passive"))
      (node (ref "C74") (pin "2") (pinfunction "2_2") (pintype "passive"))
      (node (ref "C75") (pin "2") (pinfunction "2_2") (pintype "passive"))
      (node (ref "C79") (pin "2") (pinfunction "2_2") (pintype "passive"))
      (node (ref "C80") (pin "2") (pinfunction "2_2") (pintype "passive"))
      (node (ref "C96") (pin "2") (pinfunction "2_2") (pintype "passive"))
      (node (ref "C97") (pin "2") (pinfunction "2_2") (pintype "passive"))
      (node (ref "Q1") (pin "5") (pinfunction "D_5") (pintype "passive"))
      (node (ref "Q1") (pin "6") (pinfunction "D_6") (pintype "passive"))
      (node (ref "Q1") (pin "7") (pinfunction "D_7") (pintype "passive"))
      (node (ref "Q1") (pin "8") (pinfunction "D_8") (pintype "passive"))
      (node (ref "Q13") (pin "5") (pinfunction "D_5") (pintype "passive"))
      (node (ref "Q13") (pin "6") (pinfunction "D_6") (pintype "passive"))
      (node (ref "Q13") (pin "7") (pinfunction "D_7") (pintype "passive"))
      (node (ref "Q13") (pin "8") (pinfunction "D_8") (pintype "passive"))
      (node (ref "Q14") (pin "5") (pinfunction "D_5") (pintype "passive"))
      (node (ref "Q14") (pin "6") (pinfunction "D_6") (pintype "passive"))
      (node (ref "Q14") (pin "7") (pinfunction "D_7") (pintype "passive"))
      (node (ref "Q14") (pin "8") (pinfunction "D_8") (pintype "passive"))
      (node (ref "Q15") (pin "5") (pinfunction "D_5") (pintype "passive"))
      (node (ref "Q15") (pin "6") (pinfunction "D_6") (pintype "passive"))
      (node (ref "Q15") (pin "7") (pinfunction "D_7") (pintype "passive"))
      (node (ref "Q15") (pin "8") (pinfunction "D_8") (pintype "passive"))
      (node (ref "Q16") (pin "5") (pinfunction "D_5") (pintype "passive"))
      (node (ref "Q16") (pin "6") (pinfunction "D_6") (pintype "passive"))
      (node (ref "Q16") (pin "7") (pinfunction "D_7") (pintype "passive"))
      (node (ref "Q16") (pin "8") (pinfunction "D_8") (pintype "passive"))
      (node (ref "Q2") (pin "5") (pinfunction "D_5") (pintype "passive"))
      (node (ref "Q2") (pin "6") (pinfunction "D_6") (pintype "passive"))
      (node (ref "Q2") (pin "7") (pinfunction "D_7") (pintype "passive"))
      (node (ref "Q2") (pin "8") (pinfunction "D_8") (pintype "passive"))
      (node (ref "Q25") (pin "5") (pinfunction "D_5") (pintype "passive"))
      (node (ref "Q25") (pin "6") (pinfunction "D_6") (pintype "passive"))
      (node (ref "Q25") (pin "7") (pinfunction "D_7") (pintype "passive"))
      (node (ref "Q25") (pin "8") (pinfunction "D_8") (pintype "passive"))
      (node (ref "Q26") (pin "5") (pinfunction "D_5") (pintype "passive"))
      (node (ref "Q26") (pin "6") (pinfunction "D_6") (pintype "passive"))
      (node (ref "Q26") (pin "7") (pinfunction "D_7") (pintype "passive"))
      (node (ref "Q26") (pin "8") (pinfunction "D_8") (pintype "passive"))
      (node (ref "Q27") (pin "5") (pinfunction "D_5") (pintype "passive"))
      (node (ref "Q27") (pin "6") (pinfunction "D_6") (pintype "passive"))
      (node (ref "Q27") (pin "7") (pinfunction "D_7") (pintype "passive"))
      (node (ref "Q27") (pin "8") (pinfunction "D_8") (pintype "passive"))
      (node (ref "Q28") (pin "5") (pinfunction "D_5") (pintype "passive"))
      (node (ref "Q28") (pin "6") (pinfunction "D_6") (pintype "passive"))
      (node (ref "Q28") (pin "7") (pinfunction "D_7") (pintype "passive"))
      (node (ref "Q28") (pin "8") (pinfunction "D_8") (pintype "passive"))
      (node (ref "Q3") (pin "5") (pinfunction "D_5") (pintype "passive"))
      (node (ref "Q3") (pin "6") (pinfunction "D_6") (pintype "passive"))
      (node (ref "Q3") (pin "7") (pinfunction "D_7") (pintype "passive"))
      (node (ref "Q3") (pin "8") (pinfunction "D_8") (pintype "passive"))
      (node (ref "Q37") (pin "5") (pinfunction "D_5") (pintype "passive"))
      (node (ref "Q37") (pin "6") (pinfunction "D_6") (pintype "passive"))
      (node (ref "Q37") (pin "7") (pinfunction "D_7") (pintype "passive"))
      (node (ref "Q37") (pin "8") (pinfunction "D_8") (pintype "passive"))
      (node (ref "Q38") (pin "5") (pinfunction "D_5") (pintype "passive"))
      (node (ref "Q38") (pin "6") (pinfunction "D_6") (pintype "passive"))
      (node (ref "Q38") (pin "7") (pinfunction "D_7") (pintype "passive"))
      (node (ref "Q38") (pin "8") (pinfunction "D_8") (pintype "passive"))
      (node (ref "Q39") (pin "5") (pinfunction "D_5") (pintype "passive"))
      (node (ref "Q39") (pin "6") (pinfunction "D_6") (pintype "passive"))
      (node (ref "Q39") (pin "7") (pinfunction "D_7") (pintype "passive"))
      (node (ref "Q39") (pin "8") (pinfunction "D_8") (pintype "passive"))
      (node (ref "Q4") (pin "5") (pinfunction "D_5") (pintype "passive"))
      (node (ref "Q4") (pin "6") (pinfunction "D_6") (pintype "passive"))
      (node (ref "Q4") (pin "7") (pinfunction "D_7") (pintype "passive"))
      (node (ref "Q4") (pin "8") (pinfunction "D_8") (pintype "passive"))
      (node (ref "Q40") (pin "5") (pinfunction "D_5") (pintype "passive"))
      (node (ref "Q40") (pin "6") (pinfunction "D_6") (pintype "passive"))
      (node (ref "Q40") (pin "7") (pinfunction "D_7") (pintype "passive"))
      (node (ref "Q40") (pin "8") (pinfunction "D_8") (pintype "passive"))
    )
    (net (code "5") (name "/BOOT1") (class "Default")
      (node (ref "C28") (pin "1") (pinfunction "1_1") (pintype "passive"))
      (node (ref "D10") (pin "1") (pinfunction "C_1") (pintype "passive"))
      (node (ref "U11") (pin "8") (pinfunction "BOOST_8") (pintype "passive"))
    )
    (net (code "6") (name "/BOOT2") (class "Default")
      (node (ref "C60") (pin "1") (pinfunction "1_1") (pintype "passive"))
      (node (ref "D14") (pin "1") (pinfunction "C_1") (pintype "passive"))
      (node (ref "U15") (pin "8") (pinfunction "BOOST_8") (pintype "passive"))
    )
    (net (code "7") (name "/BOOT3") (class "Default")
      (node (ref "C92") (pin "1") (pinfunction "1_1") (pintype "passive"))
      (node (ref "D18") (pin "1") (pinfunction "C_1") (pintype "passive"))
      (node (ref "U19") (pin "8") (pinfunction "BOOST_8") (pintype "passive"))
    )
    (net (code "8") (name "/BOOT4") (class "Default")
      (node (ref "C124") (pin "1") (pinfunction "1_1") (pintype "passive"))
      (node (ref "D22") (pin "1") (pinfunction "C_1") (pintype "passive"))
      (node (ref "U23") (pin "8") (pinfunction "BOOST_8") (pintype "passive"))
    )
    (net (code "9") (name "/BOOT5") (class "Default")
      (node (ref "C29") (pin "1") (pinfunction "1_1") (pintype "passive"))
      (node (ref "D11") (pin "1") (pinfunction "C_1") (pintype "passive"))
      (node (ref "U12") (pin "8") (pinfunction "BOOST_8") (pintype "passive"))
    )
    (net (code "10") (name "/BOOT6") (class "Default")
      (node (ref "C61") (pin "1") (pinfunction "1_1") (pintype "passive"))
      (node (ref "D15") (pin "1") (pinfunction "C_1") (pintype "passive"))
      (node (ref "U16") (pin "8") (pinfunction "BOOST_8") (pintype "passive"))
    )
    (net (code "11") (name "/BOOT7") (class "Default")
      (node (ref "C93") (pin "1") (pinfunction "1_1") (pintype "passive"))
      (node (ref "D19") (pin "1") (pinfunction "C_1") (pintype "passive"))
      (node (ref "U20") (pin "8") (pinfunction "BOOST_8") (pintype "passive"))
    )
    (net (code "12") (name "/BOOT8") (class "Default")
      (node (ref "C125") (pin "1") (pinfunction "1_1") (pintype "passive"))
      (node (ref "D23") (pin "1") (pinfunction "C_1") (pintype "passive"))
      (node (ref "U24") (pin "8") (pinfunction "BOOST_8") (pintype "passive"))
    )
    (net (code "13") (name "/BOOT9") (class "Default")
      (node (ref "C30") (pin "1") (pinfunction "1_1") (pintype "passive"))
      (node (ref "D12") (pin "1") (pinfunction "C_1") (pintype "passive"))
      (node (ref "U13") (pin "8") (pinfunction "BOOST_8") (pintype "passive"))
    )
    (net (code "14") (name "/BOOT10") (class "Default")
      (node (ref "C62") (pin "1") (pinfunction "1_1") (pintype "passive"))
      (node (ref "D16") (pin "1") (pinfunction "C_1") (pintype "passive"))
      (node (ref "U17") (pin "8") (pinfunction "BOOST_8") (pintype "passive"))
    )
    (net (code "15") (name "/BOOT11") (class "Default")
      (node (ref "C94") (pin "1") (pinfunction "1_1") (pintype "passive"))
      (node (ref "D20") (pin "1") (pinfunction "C_1") (pintype "passive"))
      (node (ref "U21") (pin "8") (pinfunction "BOOST_8") (pintype "passive"))
    )
    (net (code "16") (name "/BOOT12") (class "Default")
      (node (ref "C126") (pin "1") (pinfunction "1_1") (pintype "passive"))
      (node (ref "D24") (pin "1") (pinfunction "C_1") (pintype "passive"))
      (node (ref "U25") (pin "8") (pinfunction "BOOST_8") (pintype "passive"))
    )
    (net (code "17") (name "/BOOT13") (class "Default")
      (node (ref "C31") (pin "1") (pinfunction "1_1") (pintype "passive"))
      (node (ref "D13") (pin "1") (pinfunction "C_1") (pintype "passive"))
      (node (ref "U14") (pin "8") (pinfunction "BOOST_8") (pintype "passive"))
    )
    (net (code "18") (name "/BOOT14") (class "Default")
      (node (ref "C63") (pin "1") (pinfunction "1_1") (pintype "passive"))
      (node (ref "D17") (pin "1") (pinfunction "C_1") (pintype "passive"))
      (node (ref "U18") (pin "8") (pinfunction "BOOST_8") (pintype "passive"))
    )
    (net (code "19") (name "/BOOT15") (class "Default")
      (node (ref "C95") (pin "1") (pinfunction "1_1") (pintype "passive"))
      (node (ref "D21") (pin "1") (pinfunction "C_1") (pintype "passive"))
      (node (ref "U22") (pin "8") (pinfunction "BOOST_8") (pintype "passive"))
    )
    (net (code "20") (name "/BOOT16") (class "Default")
      (node (ref "C127") (pin "1") (pinfunction "1_1") (pintype "passive"))
      (node (ref "D25") (pin "1") (pinfunction "C_1") (pintype "passive"))
      (node (ref "U26") (pin "8") (pinfunction "BOOST_8") (pintype "passive"))
    )
    (net (code "21") (name "/HO1") (class "Default")
      (node (ref "Q1") (pin "4") (pinfunction "G_4") (pintype "passive"))
      (node (ref "U11") (pin "1") (pinfunction "TG_1") (pintype "passive"))
    )
    (net (code "22") (name "/HO2") (class "Default")
      (node (ref "Q13") (pin "4") (pinfunction "G_4") (pintype "passive"))
      (node (ref "U15") (pin "1") (pinfunction "TG_1") (pintype "passive"))
    )
    (net (code "23") (name "/HO3") (class "Default")
      (node (ref "Q25") (pin "4") (pinfunction "G_4") (pintype "passive"))
      (node (ref "U19") (pin "1") (pinfunction "TG_1") (pintype "passive"))
    )
    (net (code "24") (name "/HO4") (class "Default")
      (node (ref "Q37") (pin "4") (pinfunction "G_4") (pintype "passive"))
      (node (ref "U23") (pin "1") (pinfunction "TG_1") (pintype "passive"))
    )
    (net (code "25") (name "/HO5") (class "Default")
      (node (ref "Q2") (pin "4") (pinfunction "G_4") (pintype "passive"))
      (node (ref "U12") (pin "1") (pinfunction "TG_1") (pintype "passive"))
    )
    (net (code "26") (name "/HO6") (class "Default")
      (node (ref "Q14") (pin "4") (pinfunction "G_4") (pintype "passive"))
      (node (ref "U16") (pin "1") (pinfunction "TG_1") (pintype "passive"))
    )
    (net (code "27") (name "/HO7") (class "Default")
      (node (ref "Q26") (pin "4") (pinfunction "G_4") (pintype "passive"))
      (node (ref "U20") (pin "1") (pinfunction "TG_1") (pintype "passive"))
    )
    (net (code "28") (name "/HO8") (class "Default")
      (node (ref "Q38") (pin "4") (pinfunction "G_4") (pintype "passive"))
      (node (ref "U24") (pin "1") (pinfunction "TG_1") (pintype "passive"))
    )
    (net (code "29") (name "/HO9") (class "Default")
      (node (ref "Q3") (pin "4") (pinfunction "G_4") (pintype "passive"))
      (node (ref "U13") (pin "1") (pinfunction "TG_1") (pintype "passive"))
    )
    (net (code "30") (name "/HO10") (class "Default")
      (node (ref "Q15") (pin "4") (pinfunction "G_4") (pintype "passive"))
      (node (ref "U17") (pin "1") (pinfunction "TG_1") (pintype "passive"))
    )
    (net (code "31") (name "/HO11") (class "Default")
      (node (ref "Q27") (pin "4") (pinfunction "G_4") (pintype "passive"))
      (node (ref "U21") (pin "1") (pinfunction "TG_1") (pintype "passive"))
    )
    (net (code "32") (name "/HO12") (class "Default")
      (node (ref "Q39") (pin "4") (pinfunction "G_4") (pintype "passive"))
      (node (ref "U25") (pin "1") (pinfunction "TG_1") (pintype "passive"))
    )
    (net (code "33") (name "/HO13") (class "Default")
      (node (ref "Q4") (pin "4") (pinfunction "G_4") (pintype "passive"))
      (node (ref "U14") (pin "1") (pinfunction "TG_1") (pintype "passive"))
    )
    (net (code "34") (name "/HO14") (class "Default")
      (node (ref "Q16") (pin "4") (pinfunction "G_4") (pintype "passive"))
      (node (ref "U18") (pin "1") (pinfunction "TG_1") (pintype "passive"))
    )
    (net (code "35") (name "/HO15") (class "Default")
      (node (ref "Q28") (pin "4") (pinfunction "G_4") (pintype "passive"))
      (node (ref "U22") (pin "1") (pinfunction "TG_1") (pintype "passive"))
    )
    (net (code "36") (name "/HO16") (class "Default")
      (node (ref "Q40") (pin "4") (pinfunction "G_4") (pintype "passive"))
      (node (ref "U26") (pin "1") (pinfunction "TG_1") (pintype "passive"))
    )
    (net (code "37") (name "/LO1") (class "Default")
      (node (ref "Q5") (pin "4") (pinfunction "G_4") (pintype "passive"))
      (node (ref "Q6") (pin "4") (pinfunction "G_4") (pintype "passive"))
      (node (ref "U11") (pin "3") (pinfunction "BG_3") (pintype "passive"))
    )
    (net (code "38") (name "/LO2") (class "Default")
      (node (ref "Q17") (pin "4") (pinfunction "G_4") (pintype "passive"))
      (node (ref "Q18") (pin "4") (pinfunction "G_4") (pintype "passive"))
      (node (ref "U15") (pin "3") (pinfunction "BG_3") (pintype "passive"))
    )
    (net (code "39") (name "/LO3") (class "Default")
      (node (ref "Q29") (pin "4") (pinfunction "G_4") (pintype "passive"))
      (node (ref "Q30") (pin "4") (pinfunction "G_4") (pintype "passive"))
      (node (ref "U19") (pin "3") (pinfunction "BG_3") (pintype "passive"))
    )
    (net (code "40") (name "/LO4") (class "Default")
      (node (ref "Q41") (pin "4") (pinfunction "G_4") (pintype "passive"))
      (node (ref "Q42") (pin "4") (pinfunction "G_4") (pintype "passive"))
      (node (ref "U23") (pin "3") (pinfunction "BG_3") (pintype "passive"))
    )
    (net (code "41") (name "/LO5") (class "Default")
      (node (ref "Q7") (pin "4") (pinfunction "G_4") (pintype "passive"))
      (node (ref "Q8") (pin "4") (pinfunction "G_4") (pintype "passive"))
      (node (ref "U12") (pin "3") (pinfunction "BG_3") (pintype "passive"))
    )
    (net (code "42") (name "/LO6") (class "Default")
      (node (ref "Q19") (pin "4") (pinfunction "G_4") (pintype "passive"))
      (node (ref "Q20") (pin "4") (pinfunction "G_4") (pintype "passive"))
      (node (ref "U16") (pin "3") (pinfunction "BG_3") (pintype "passive"))
    )
    (net (code "43") (name "/LO7") (class "Default")
      (node (ref "Q31") (pin "4") (pinfunction "G_4") (pintype "passive"))
      (node (ref "Q32") (pin "4") (pinfunction "G_4") (pintype "passive"))
      (node (ref "U20") (pin "3") (pinfunction "BG_3") (pintype "passive"))
    )
    (net (code "44") (name "/LO8") (class "Default")
      (node (ref "Q43") (pin "4") (pinfunction "G_4") (pintype "passive"))
      (node (ref "Q44") (pin "4") (pinfunction "G_4") (pintype "passive"))
      (node (ref "U24") (pin "3") (pinfunction "BG_3") (pintype "passive"))
    )
    (net (code "45") (name "/LO9") (class "Default")
      (node (ref "Q10") (pin "4") (pinfunction "G_4") (pintype "passive"))
      (node (ref "Q9") (pin "4") (pinfunction "G_4") (pintype "passive"))
      (node (ref "U13") (pin "3") (pinfunction "BG_3") (pintype "passive"))
    )
    (net (code "46") (name "/LO10") (class "Default")
      (node (ref "Q21") (pin "4") (pinfunction "G_4") (pintype "passive"))
      (node (ref "Q22") (pin "4") (pinfunction "G_4") (pintype "passive"))
      (node (ref "U17") (pin "3") (pinfunction "BG_3") (pintype "passive"))
    )
    (net (code "47") (name "/LO11") (class "Default")
      (node (ref "Q33") (pin "4") (pinfunction "G_4") (pintype "passive"))
      (node (ref "Q34") (pin "4") (pinfunction "G_4") (pintype "passive"))
      (node (ref "U21") (pin "3") (pinfunction "BG_3") (pintype "passive"))
    )
    (net (code "48") (name "/LO12") (class "Default")
      (node (ref "Q45") (pin "4") (pinfunction "G_4") (pintype "passive"))
      (node (ref "Q46") (pin "4") (pinfunction "G_4") (pintype "passive"))
      (node (ref "U25") (pin "3") (pinfunction "BG_3") (pintype "passive"))
    )
    (net (code "49") (name "/LO13") (class "Default")
      (node (ref "Q11") (pin "4") (pinfunction "G_4") (pintype "passive"))
      (node (ref "Q12") (pin "4") (pinfunction "G_4") (pintype "passive"))
      (node (ref "U14") (pin "3") (pinfunction "BG_3") (pintype "passive"))
    )
    (net (code "50") (name "/LO14") (class "Default")
      (node (ref "Q23") (pin "4") (pinfunction "G_4") (pintype "passive"))
      (node (ref "Q24") (pin "4") (pinfunction "G_4") (pintype "passive"))
      (node (ref "U18") (pin "3") (pinfunction "BG_3") (pintype "passive"))
    )
    (net (code "51") (name "/LO15") (class "Default")
      (node (ref "Q35") (pin "4") (pinfunction "G_4") (pintype "passive"))
      (node (ref "Q36") (pin "4") (pinfunction "G_4") (pintype "passive"))
      (node (ref "U22") (pin "3") (pinfunction "BG_3") (pintype "passive"))
    )
    (net (code "52") (name "/LO16") (class "Default")
      (node (ref "Q47") (pin "4") (pinfunction "G_4") (pintype "passive"))
      (node (ref "Q48") (pin "4") (pinfunction "G_4") (pintype "passive"))
      (node (ref "U26") (pin "3") (pinfunction "BG_3") (pintype "passive"))
    )
    (net (code "53") (name "/PWM1H") (class "Default")
      (node (ref "U12") (pin "5") (pinfunction "IN_5") (pintype "passive"))
      (node (ref "U14") (pin "5") (pinfunction "IN_5") (pintype "passive"))
    )
    (net (code "54") (name "/PWM1L") (class "Default")
      (node (ref "U11") (pin "5") (pinfunction "IN_5") (pintype "passive"))
      (node (ref "U13") (pin "5") (pinfunction "IN_5") (pintype "passive"))
    )
    (net (code "55") (name "/PWM2H") (class "Default")
      (node (ref "U16") (pin "5") (pinfunction "IN_5") (pintype "passive"))
      (node (ref "U18") (pin "5") (pinfunction "IN_5") (pintype "passive"))
    )
    (net (code "56") (name "/PWM2L") (class "Default")
      (node (ref "U15") (pin "5") (pinfunction "IN_5") (pintype "passive"))
      (node (ref "U17") (pin "5") (pinfunction "IN_5") (pintype "passive"))
    )
    (net (code "57") (name "/PWM3H") (class "Default")
      (node (ref "U20") (pin "5") (pinfunction "IN_5") (pintype "passive"))
      (node (ref "U22") (pin "5") (pinfunction "IN_5") (pintype "passive"))
    )
    (net (code "58") (name "/PWM3L") (class "Default")
      (node (ref "U19") (pin "5") (pinfunction "IN_5") (pintype "passive"))
      (node (ref "U21") (pin "5") (pinfunction "IN_5") (pintype "passive"))
    )
    (net (code "59") (name "/PWM4H") (class "Default")
      (node (ref "U24") (pin "5") (pinfunction "IN_5") (pintype "passive"))
      (node (ref "U26") (pin "5") (pinfunction "IN_5") (pintype "passive"))
    )
    (net (code "60") (name "/PWM4L") (class "Default")
      (node (ref "U23") (pin "5") (pinfunction "IN_5") (pintype "passive"))
      (node (ref "U25") (pin "5") (pinfunction "IN_5") (pintype "passive"))
    )
    (net (code "61") (name "/SWN1") (class "Default")
      (node (ref "C28") (pin "2") (pinfunction "2_2") (pintype "passive"))
      (node (ref "Q5") (pin "8") (pinfunction "D_8") (pintype "passive"))
      (node (ref "Q6") (pin "5") (pinfunction "D_5") (pintype "passive"))
      (node (ref "Q6") (pin "6") (pinfunction "D_6") (pintype "passive"))
      (node (ref "Q6") (pin "8") (pinfunction "D_8") (pintype "passive"))
      (node (ref "U11") (pin "2") (pinfunction "TS_2") (pintype "passive"))
    )
    (net (code "62") (name "/SWN2") (class "Default")
      (node (ref "C60") (pin "2") (pinfunction "2_2") (pintype "passive"))
      (node (ref "L5") (pin "1") (pinfunction "1_1") (pintype "passive"))
      (node (ref "Q13") (pin "1") (pinfunction "S_1") (pintype "passive"))
      (node (ref "Q13") (pin "2") (pinfunction "S_2") (pintype "passive"))
      (node (ref "Q13") (pin "3") (pinfunction "S_3") (pintype "passive"))
      (node (ref "Q17") (pin "5") (pinfunction "D_5") (pintype "passive"))
      (node (ref "Q17") (pin "6") (pinfunction "D_6") (pintype "passive"))
      (node (ref "Q17") (pin "7") (pinfunction "D_7") (pintype "passive"))
      (node (ref "Q17") (pin "8") (pinfunction "D_8") (pintype "passive"))
      (node (ref "Q18") (pin "5") (pinfunction "D_5") (pintype "passive"))
      (node (ref "Q18") (pin "6") (pinfunction "D_6") (pintype "passive"))
      (node (ref "Q18") (pin "7") (pinfunction "D_7") (pintype "passive"))
      (node (ref "Q18") (pin "8") (pinfunction "D_8") (pintype "passive"))
      (node (ref "U15") (pin "2") (pinfunction "TS_2") (pintype "passive"))
    )
    (net (code "63") (name "/SWN3") (class "Default")
      (node (ref "C92") (pin "2") (pinfunction "2_2") (pintype "passive"))
      (node (ref "L9") (pin "1") (pinfunction "1_1") (pintype "passive"))
      (node (ref "Q25") (pin "1") (pinfunction "S_1") (pintype "passive"))
      (node (ref "Q25") (pin "2") (pinfunction "S_2") (pintype "passive"))
      (node (ref "Q25") (pin "3") (pinfunction "S_3") (pintype "passive"))
      (node (ref "Q29") (pin "5") (pinfunction "D_5") (pintype "passive"))
      (node (ref "Q29") (pin "6") (pinfunction "D_6") (pintype "passive"))
      (node (ref "Q29") (pin "7") (pinfunction "D_7") (pintype "passive"))
      (node (ref "Q29") (pin "8") (pinfunction "D_8") (pintype "passive"))
      (node (ref "Q30") (pin "5") (pinfunction "D_5") (pintype "passive"))
      (node (ref "Q30") (pin "6") (pinfunction "D_6") (pintype "passive"))
      (node (ref "Q30") (pin "7") (pinfunction "D_7") (pintype "passive"))
      (node (ref "Q30") (pin "8") (pinfunction "D_8") (pintype "passive"))
      (node (ref "U19") (pin "2") (pinfunction "TS_2") (pintype "passive"))
    )
    (net (code "64") (name "/SWN4") (class "Default")
      (node (ref "C124") (pin "2") (pinfunction "2_2") (pintype "passive"))
      (node (ref "L13") (pin "1") (pinfunction "1_1") (pintype "passive"))
      (node (ref "Q37") (pin "1") (pinfunction "S_1") (pintype "passive"))
      (node (ref "Q37") (pin "2") (pinfunction "S_2") (pintype "passive"))
      (node (ref "Q37") (pin "3") (pinfunction "S_3") (pintype "passive"))
      (node (ref "Q41") (pin "5") (pinfunction "D_5") (pintype "passive"))
      (node (ref "Q41") (pin "6") (pinfunction "D_6") (pintype "passive"))
      (node (ref "Q41") (pin "7") (pinfunction "D_7") (pintype "passive"))
      (node (ref "Q41") (pin "8") (pinfunction "D_8") (pintype "passive"))
      (node (ref "Q42") (pin "5") (pinfunction "D_5") (pintype "passive"))
      (node (ref "Q42") (pin "6") (pinfunction "D_6") (pintype "passive"))
      (node (ref "Q42") (pin "7") (pinfunction "D_7") (pintype "passive"))
      (node (ref "Q42") (pin "8") (pinfunction "D_8") (pintype "passive"))
      (node (ref "U23") (pin "2") (pinfunction "TS_2") (pintype "passive"))
    )
    (net (code "65") (name "/SWN5") (class "Default")
      (node (ref "C29") (pin "2") (pinfunction "2_2") (pintype "passive"))
      (node (ref "L2") (pin "1") (pinfunction "1_1") (pintype "passive"))
      (node (ref "Q2") (pin "1") (pinfunction "S_1") (pintype "passive"))
      (node (ref "Q2") (pin "2") (pinfunction "S_2") (pintype "passive"))
      (node (ref "Q2") (pin "3") (pinfunction "S_3") (pintype "passive"))
      (node (ref "Q7") (pin "5") (pinfunction "D_5") (pintype "passive"))
      (node (ref "Q7") (pin "6") (pinfunction "D_6") (pintype "passive"))
      (node (ref "Q7") (pin "7") (pinfunction "D_7") (pintype "passive"))
      (node (ref "Q7") (pin "8") (pinfunction "D_8") (pintype "passive"))
      (node (ref "Q8") (pin "5") (pinfunction "D_5") (pintype "passive"))
      (node (ref "Q8") (pin "6") (pinfunction "D_6") (pintype "passive"))
      (node (ref "Q8") (pin "7") (pinfunction "D_7") (pintype "passive"))
      (node (ref "Q8") (pin "8") (pinfunction "D_8") (pintype "passive"))
      (node (ref "U12") (pin "2") (pinfunction "TS_2") (pintype "passive"))
    )
    (net (code "66") (name "/SWN6") (class "Default")
      (node (ref "C61") (pin "2") (pinfunction "2_2") (pintype "passive"))
      (node (ref "L6") (pin "1") (pinfunction "1_1") (pintype "passive"))
      (node (ref "Q14") (pin "1") (pinfunction "S_1") (pintype "passive"))
      (node (ref "Q14") (pin "2") (pinfunction "S_2") (pintype "passive"))
      (node (ref "Q14") (pin "3") (pinfunction "S_3") (pintype "passive"))
      (node (ref "Q19") (pin "5") (pinfunction "D_5") (pintype "passive"))
      (node (ref "Q19") (pin "6") (pinfunction "D_6") (pintype "passive"))
      (node (ref "Q19") (pin "7") (pinfunction "D_7") (pintype "passive"))
      (node (ref "Q19") (pin "8") (pinfunction "D_8") (pintype "passive"))
      (node (ref "Q20") (pin "5") (pinfunction "D_5") (pintype "passive"))
      (node (ref "Q20") (pin "6") (pinfunction "D_6") (pintype "passive"))
      (node (ref "Q20") (pin "7") (pinfunction "D_7") (pintype "passive"))
      (node (ref "Q20") (pin "8") (pinfunction "D_8") (pintype "passive"))
      (node (ref "U16") (pin "2") (pinfunction "TS_2") (pintype "passive"))
    )
    (net (code "67") (name "/SWN7") (class "Default")
      (node (ref "C93") (pin "2") (pinfunction "2_2") (pintype "passive"))
      (node (ref "L10") (pin "1") (pinfunction "1_1") (pintype "passive"))
      (node (ref "Q26") (pin "1") (pinfunction "S_1") (pintype "passive"))
      (node (ref "Q26") (pin "2") (pinfunction "S_2") (pintype "passive"))
      (node (ref "Q26") (pin "3") (pinfunction "S_3") (pintype "passive"))
      (node (ref "Q31") (pin "5") (pinfunction "D_5") (pintype "passive"))
      (node (ref "Q31") (pin "6") (pinfunction "D_6") (pintype "passive"))
      (node (ref "Q31") (pin "7") (pinfunction "D_7") (pintype "passive"))
      (node (ref "Q31") (pin "8") (pinfunction "D_8") (pintype "passive"))
      (node (ref "Q32") (pin "5") (pinfunction "D_5") (pintype "passive"))
      (node (ref "Q32") (pin "6") (pinfunction "D_6") (pintype "passive"))
      (node (ref "Q32") (pin "7") (pinfunction "D_7") (pintype "passive"))
      (node (ref "Q32") (pin "8") (pinfunction "D_8") (pintype "passive"))
      (node (ref "U20") (pin "2") (pinfunction "TS_2") (pintype "passive"))
    )
    (net (code "68") (name "/SWN8") (class "Default")
      (node (ref "C125") (pin "2") (pinfunction "2_2") (pintype "passive"))
      (node (ref "L14") (pin "1") (pinfunction "1_1") (pintype "passive"))
      (node (ref "Q38") (pin "1") (pinfunction "S_1") (pintype "passive"))
      (node (ref "Q38") (pin "2") (pinfunction "S_2") (pintype "passive"))
      (node (ref "Q38") (pin "3") (pinfunction "S_3") (pintype "passive"))
      (node (ref "Q43") (pin "5") (pinfunction "D_5") (pintype "passive"))
      (node (ref "Q43") (pin "6") (pinfunction "D_6") (pintype "passive"))
      (node (ref "Q43") (pin "7") (pinfunction "D_7") (pintype "passive"))
      (node (ref "Q43") (pin "8") (pinfunction "D_8") (pintype "passive"))
      (node (ref "Q44") (pin "5") (pinfunction "D_5") (pintype "passive"))
      (node (ref "Q44") (pin "6") (pinfunction "D_6") (pintype "passive"))
      (node (ref "Q44") (pin "7") (pinfunction "D_7") (pintype "passive"))
      (node (ref "Q44") (pin "8") (pinfunction "D_8") (pintype "passive"))
      (node (ref "U24") (pin "2") (pinfunction "TS_2") (pintype "passive"))
    )
    (net (code "69") (name "/SWN9") (class "Default")
      (node (ref "C30") (pin "2") (pinfunction "2_2") (pintype "passive"))
      (node (ref "L3") (pin "1") (pinfunction "1_1") (pintype "passive"))
      (node (ref "Q10") (pin "5") (pinfunction "D_5") (pintype "passive"))
      (node (ref "Q10") (pin "6") (pinfunction "D_6") (pintype "passive"))
      (node (ref "Q10") (pin "7") (pinfunction "D_7") (pintype "passive"))
      (node (ref "Q10") (pin "8") (pinfunction "D_8") (pintype "passive"))
      (node (ref "Q3") (pin "1") (pinfunction "S_1") (pintype "passive"))
      (node (ref "Q3") (pin "2") (pinfunction "S_2") (pintype "passive"))
      (node (ref "Q3") (pin "3") (pinfunction "S_3") (pintype "passive"))
      (node (ref "Q9") (pin "5") (pinfunction "D_5") (pintype "passive"))
      (node (ref "Q9") (pin "6") (pinfunction "D_6") (pintype "passive"))
      (node (ref "Q9") (pin "7") (pinfunction "D_7") (pintype "passive"))
      (node (ref "Q9") (pin "8") (pinfunction "D_8") (pintype "passive"))
      (node (ref "U13") (pin "2") (pinfunction "TS_2") (pintype "passive"))
    )
    (net (code "70") (name "/SWN10") (class "Default")
      (node (ref "C62") (pin "2") (pinfunction "2_2") (pintype "passive"))
      (node (ref "L7") (pin "1") (pinfunction "1_1") (pintype "passive"))
      (node (ref "Q15") (pin "1") (pinfunction "S_1") (pintype "passive"))
      (node (ref "Q15") (pin "2") (pinfunction "S_2") (pintype "passive"))
      (node (ref "Q15") (pin "3") (pinfunction "S_3") (pintype "passive"))
      (node (ref "Q21") (pin "5") (pinfunction "D_5") (pintype "passive"))
      (node (ref "Q21") (pin "6") (pinfunction "D_6") (pintype "passive"))
      (node (ref "Q21") (pin "7") (pinfunction "D_7") (pintype "passive"))
      (node (ref "Q21") (pin "8") (pinfunction "D_8") (pintype "passive"))
      (node (ref "Q22") (pin "5") (pinfunction "D_5") (pintype "passive"))
      (node (ref "Q22") (pin "6") (pinfunction "D_6") (pintype "passive"))
      (node (ref "Q22") (pin "7") (pinfunction "D_7") (pintype "passive"))
      (node (ref "Q22") (pin "8") (pinfunction "D_8") (pintype "passive"))
      (node (ref "U17") (pin "2") (pinfunction "TS_2") (pintype "passive"))
    )
    (net (code "71") (name "/SWN11") (class "Default")
      (node (ref "C94") (pin "2") (pinfunction "2_2") (pintype "passive"))
      (node (ref "L11") (pin "1") (pinfunction "1_1") (pintype "passive"))
      (node (ref "Q27") (pin "1") (pinfunction "S_1") (pintype "passive"))
      (node (ref "Q27") (pin "2") (pinfunction "S_2") (pintype "passive"))
      (node (ref "Q27") (pin "3") (pinfunction "S_3") (pintype "passive"))
      (node (ref "Q33") (pin "5") (pinfunction "D_5") (pintype "passive"))
      (node (ref "Q33") (pin "6") (pinfunction "D_6") (pintype "passive"))
      (node (ref "Q33") (pin "7") (pinfunction "D_7") (pintype "passive"))
      (node (ref "Q33") (pin "8") (pinfunction "D_8") (pintype "passive"))
      (node (ref "Q34") (pin "5") (pinfunction "D_5") (pintype "passive"))
      (node (ref "Q34") (pin "6") (pinfunction "D_6") (pintype "passive"))
      (node (ref "Q34") (pin "7") (pinfunction "D_7") (pintype "passive"))
      (node (ref "Q34") (pin "8") (pinfunction "D_8") (pintype "passive"))
      (node (ref "U21") (pin "2") (pinfunction "TS_2") (pintype "passive"))
    )
    (net (code "72") (name "/SWN12") (class "Default")
      (node (ref "C126") (pin "2") (pinfunction "2_2") (pintype "passive"))
      (node (ref "L15") (pin "1") (pinfunction "1_1") (pintype "passive"))
      (node (ref "Q39") (pin "1") (pinfunction "S_1") (pintype "passive"))
      (node (ref "Q39") (pin "2") (pinfunction "S_2") (pintype "passive"))
      (node (ref "Q39") (pin "3") (pinfunction "S_3") (pintype "passive"))
      (node (ref "Q45") (pin "5") (pinfunction "D_5") (pintype "passive"))
      (node (ref "Q45") (pin "6") (pinfunction "D_6") (pintype "passive"))
      (node (ref "Q45") (pin "7") (pinfunction "D_7") (pintype "passive"))
      (node (ref "Q45") (pin "8") (pinfunction "D_8") (pintype "passive"))
      (node (ref "Q46") (pin "5") (pinfunction "D_5") (pintype "passive"))
      (node (ref "Q46") (pin "6") (pinfunction "D_6") (pintype "passive"))
      (node (ref "Q46") (pin "7") (pinfunction "D_7") (pintype "passive"))
      (node (ref "Q46") (pin "8") (pinfunction "D_8") (pintype "passive"))
      (node (ref "U25") (pin "2") (pinfunction "TS_2") (pintype "passive"))
    )
    (net (code "73") (name "/SWN13") (class "Default")
      (node (ref "C31") (pin "2") (pinfunction "2_2") (pintype "passive"))
      (node (ref "L4") (pin "1") (pinfunction "1_1") (pintype "passive"))
      (node (ref "Q11") (pin "5") (pinfunction "D_5") (pintype "passive"))
      (node (ref "Q11") (pin "6") (pinfunction "D_6") (pintype "passive"))
      (node (ref "Q11") (pin "7") (pinfunction "D_7") (pintype "passive"))
      (node (ref "Q11") (pin "8") (pinfunction "D_8") (pintype "passive"))
      (node (ref "Q12") (pin "5") (pinfunction "D_5") (pintype "passive"))
      (node (ref "Q12") (pin "6") (pinfunction "D_6") (pintype "passive"))
      (node (ref "Q12") (pin "7") (pinfunction "D_7") (pintype "passive"))
      (node (ref "Q12") (pin "8") (pinfunction "D_8") (pintype "passive"))
      (node (ref "Q4") (pin "1") (pinfunction "S_1") (pintype "passive"))
      (node (ref "Q4") (pin "2") (pinfunction "S_2") (pintype "passive"))
      (node (ref "Q4") (pin "3") (pinfunction "S_3") (pintype "passive"))
      (node (ref "U14") (pin "2") (pinfunction "TS_2") (pintype "passive"))
    )
    (net (code "74") (name "/SWN14") (class "Default")
      (node (ref "C63") (pin "2") (pinfunction "2_2") (pintype "passive"))
      (node (ref "L8") (pin "1") (pinfunction "1_1") (pintype "passive"))
      (node (ref "Q16") (pin "1") (pinfunction "S_1") (pintype "passive"))
      (node (ref "Q16") (pin "2") (pinfunction "S_2") (pintype "passive"))
      (node (ref "Q16") (pin "3") (pinfunction "S_3") (pintype "passive"))
      (node (ref "Q23") (pin "5") (pinfunction "D_5") (pintype "passive"))
      (node (ref "Q23") (pin "6") (pinfunction "D_6") (pintype "passive"))
      (node (ref "Q23") (pin "7") (pinfunction "D_7") (pintype "passive"))
      (node (ref "Q23") (pin "8") (pinfunction "D_8") (pintype "passive"))
      (node (ref "Q24") (pin "5") (pinfunction "D_5") (pintype "passive"))
      (node (ref "Q24") (pin "6") (pinfunction "D_6") (pintype "passive"))
      (node (ref "Q24") (pin "7") (pinfunction "D_7") (pintype "passive"))
      (node (ref "Q24") (pin "8") (pinfunction "D_8") (pintype "passive"))
      (node (ref "U18") (pin "2") (pinfunction "TS_2") (pintype "passive"))
    )
    (net (code "75") (name "/SWN15") (class "Default")
      (node (ref "C95") (pin "2") (pinfunction "2_2") (pintype "passive"))
      (node (ref "L12") (pin "1") (pinfunction "1_1") (pintype "passive"))
      (node (ref "Q28") (pin "1") (pinfunction "S_1") (pintype "passive"))
      (node (ref "Q28") (pin "2") (pinfunction "S_2") (pintype "passive"))
      (node (ref "Q28") (pin "3") (pinfunction "S_3") (pintype "passive"))
      (node (ref "Q35") (pin "5") (pinfunction "D_5") (pintype "passive"))
      (node (ref "Q35") (pin "6") (pinfunction "D_6") (pintype "passive"))
      (node (ref "Q35") (pin "7") (pinfunction "D_7") (pintype "passive"))
      (node (ref "Q35") (pin "8") (pinfunction "D_8") (pintype "passive"))
      (node (ref "Q36") (pin "5") (pinfunction "D_5") (pintype "passive"))
      (node (ref "Q36") (pin "6") (pinfunction "D_6") (pintype "passive"))
      (node (ref "Q36") (pin "7") (pinfunction "D_7") (pintype "passive"))
      (node (ref "Q36") (pin "8") (pinfunction "D_8") (pintype "passive"))
      (node (ref "U22") (pin "2") (pinfunction "TS_2") (pintype "passive"))
    )
    (net (code "76") (name "/SWN16") (class "Default")
      (node (ref "C127") (pin "2") (pinfunction "2_2") (pintype "passive"))
      (node (ref "L16") (pin "1") (pinfunction "1_1") (pintype "passive"))
      (node (ref "Q40") (pin "1") (pinfunction "S_1") (pintype "passive"))
      (node (ref "Q40") (pin "2") (pinfunction "S_2") (pintype "passive"))
      (node (ref "Q40") (pin "3") (pinfunction "S_3") (pintype "passive"))
      (node (ref "Q47") (pin "5") (pinfunction "D_5") (pintype "passive"))
      (node (ref "Q47") (pin "6") (pinfunction "D_6") (pintype "passive"))
      (node (ref "Q47") (pin "7") (pinfunction "D_7") (pintype "passive"))
      (node (ref "Q47") (pin "8") (pinfunction "D_8") (pintype "passive"))
      (node (ref "Q48") (pin "5") (pinfunction "D_5") (pintype "passive"))
      (node (ref "Q48") (pin "6") (pinfunction "D_6") (pintype "passive"))
      (node (ref "Q48") (pin "7") (pinfunction "D_7") (pintype "passive"))
      (node (ref "Q48") (pin "8") (pinfunction "D_8") (pintype "passive"))
      (node (ref "U26") (pin "2") (pinfunction "TS_2") (pintype "passive"))
    )
    (net (code "77") (name "GND") (class "Default")
      (node (ref "C100") (pin "1") (pinfunction "1_1") (pintype "passive"))
      (node (ref "C101") (pin "1") (pinfunction "1_1") (pintype "passive"))
      (node (ref "C102") (pin "1") (pinfunction "1_1") (pintype "passive"))
      (node (ref "C103") (pin "1") (pinfunction "1_1") (pintype "passive"))
      (node (ref "C104") (pin "1") (pinfunction "1_1") (pintype "passive"))
      (node (ref "C105") (pin "1") (pinfunction "1_1") (pintype "passive"))
      (node (ref "C106") (pin "1") (pinfunction "1_1") (pintype "passive"))
      (node (ref "C107") (pin "1") (pinfunction "1_1") (pintype "passive"))
      (node (ref "C108") (pin "1") (pinfunction "1_1") (pintype "passive"))
      (node (ref "C109") (pin "1") (pinfunction "1_1") (pintype "passive"))
      (node (ref "C110") (pin "1") (pinfunction "1_1") (pintype "passive"))
      (node (ref "C111") (pin "1") (pinfunction "1_1") (pintype "passive"))
      (node (ref "C112") (pin "1") (pinfunction "1_1") (pintype "passive"))
      (node (ref "C113") (pin "1") (pinfunction "1_1") (pintype "passive"))
      (node (ref "C114") (pin "1") (pinfunction "1_1") (pintype "passive"))
      (node (ref "C115") (pin "1") (pinfunction "1_1") (pintype "passive"))
      (node (ref "C116") (pin "1") (pinfunction "1_1") (pintype "passive"))
      (node (ref "C117") (pin "1") (pinfunction "1_1") (pintype "passive"))
      (node (ref "C118") (pin "1") (pinfunction "1_1") (pintype "passive"))
      (node (ref "C119") (pin "1") (pinfunction "1_1") (pintype "passive"))
      (node (ref "C120") (pin "2") (pinfunction "2_2") (pintype "passive"))
      (node (ref "C121") (pin "2") (pinfunction "2_2") (pintype "passive"))
      (node (ref "C122") (pin "2") (pinfunction "2_2") (pintype "passive"))
      (node (ref "C123") (pin "2") (pinfunction "2_2") (pintype "passive"))
      (node (ref "C128") (pin "1") (pinfunction "1_1") (pintype "passive"))
      (node (ref "C129") (pin "1") (pinfunction "1_1") (pintype "passive"))
      (node (ref "C130") (pin "1") (pinfunction "1_1") (pintype "passive"))
      (node (ref "C131") (pin "1") (pinfunction "1_1") (pintype "passive"))
      (node (ref "C132") (pin "1") (pinfunction "1_1") (pintype "passive"))
      (node (ref "C133") (pin "1") (pinfunction "1_1") (pintype "passive"))
      (node (ref "C134") (pin "1") (pinfunction "1_1") (pintype "passive"))
      (node (ref "C135") (pin "1") (pinfunction "1_1") (pintype "passive"))
      (node (ref "C136") (pin "1") (pinfunction "1_1") (pintype "passive"))
      (node (ref "C137") (pin "1") (pinfunction "1_1") (pintype "passive"))
      (node (ref "C138") (pin "1") (pinfunction "1_1") (pintype "passive"))
      (node (ref "C139") (pin "1") (pinfunction "1_1") (pintype "passive"))
      (node (ref "C140") (pin "1") (pinfunction "1_1") (pintype "passive"))
      (node (ref "C141") (pin "1") (pinfunction "1_1") (pintype "passive"))
      (node (ref "C142") (pin "1") (pinfunction "1_1") (pintype "passive"))
      (node (ref "C143") (pin "1") (pinfunction "1_1") (pintype "passive"))
      (node (ref "C144") (pin "1") (pinfunction "1_1") (pintype "passive"))
      (node (ref "C145") (pin "1") (pinfunction "1_1") (pintype "passive"))
      (node (ref "C146") (pin "1") (pinfunction "1_1") (pintype "passive"))
      (node (ref "C147") (pin "1") (pinfunction "1_1") (pintype "passive"))
      (node (ref "C20") (pin "1") (pinfunction "1_1") (pintype "passive"))
      (node (ref "C21") (pin "1") (pinfunction "1_1") (pintype "passive"))
      (node (ref "C22") (pin "1") (pinfunction "1_1") (pintype "passive"))
      (node (ref "C23") (pin "1") (pinfunction "1_1") (pintype "passive"))
      (node (ref "C236") (pin "1") (pinfunction "1_1") (pintype "passive"))
      (node (ref "C24") (pin "2") (pinfunction "2_2") (pintype "passive"))
      (node (ref "C25") (pin "2") (pinfunction "2_2") (pintype "passive"))
      (node (ref "C26") (pin "2") (pinfunction "2_2") (pintype "passive"))
      (node (ref "C27") (pin "2") (pinfunction "2_2") (pintype "passive"))
      (node (ref "C32") (pin "1") (pinfunction "1_1") (pintype "passive"))
      (node (ref "C33") (pin "1") (pinfunction "1_1") (pintype "passive"))
      (node (ref "C34") (pin "1") (pinfunction "1_1") (pintype "passive"))
      (node (ref "C348") (pin "1") (pinfunction "1_1") (pintype "passive"))
      (node (ref "C349") (pin "1") (pinfunction "1_1") (pintype "passive"))
      (node (ref "C35") (pin "1") (pinfunction "1_1") (pintype "passive"))
      (node (ref "C350") (pin "1") (pinfunction "1_1") (pintype "passive"))
      (node (ref "C351") (pin "1") (pinfunction "1_1") (pintype "passive"))
      (node (ref "C352") (pin "1") (pinfunction "1_1") (pintype "passive"))
      (node (ref "C353") (pin "1") (pinfunction "1_1") (pintype "passive"))
      (node (ref "C354") (pin "1") (pinfunction "1_1") (pintype "passive"))
      (node (ref "C355") (pin "1") (pinfunction "1_1") (pintype "passive"))
      (node (ref "C356") (pin "1") (pinfunction "1_1") (pintype "passive"))
      (node (ref "C357") (pin "1") (pinfunction "1_1") (pintype "passive"))
      (node (ref "C358") (pin "1") (pinfunction "1_1") (pintype "passive"))
      (node (ref "C359") (pin "1") (pinfunction "1_1") (pintype "passive"))
      (node (ref "C360") (pin "1") (pinfunction "1_1") (pintype "passive"))
      (node (ref "C361") (pin "1") (pinfunction "1_1") (pintype "passive"))
      (node (ref "C362") (pin "1") (pinfunction "1_1") (pintype "passive"))
      (node (ref "C363") (pin "1") (pinfunction "1_1") (pintype "passive"))
      (node (ref "C364") (pin "1") (pinfunction "1_1") (pintype "passive"))
      (node (ref "C365") (pin "1") (pinfunction "1_1") (pintype "passive"))
      (node (ref "C366") (pin "1") (pinfunction "1_1") (pintype "passive"))
      (node (ref "C367") (pin "1") (pinfunction "1_1") (pintype "passive"))
      (node (ref "C368") (pin "1") (pinfunction "1_1") (pintype "passive"))
      (node (ref "C369") (pin "1") (pinfunction "1_1") (pintype "passive"))
      (node (ref "C37") (pin "1") (pinfunction "1_1") (pintype "passive"))
      (node (ref "C370") (pin "1") (pinfunction "1_1") (pintype "passive"))
      (node (ref "C371") (pin "1") (pinfunction "1_1") (pintype "passive"))
      (node (ref "C372") (pin "1") (pinfunction "1_1") (pintype "passive"))
      (node (ref "C373") (pin "1") (pinfunction "1_1") (pintype "passive"))
      (node (ref "C374") (pin "1") (pinfunction "1_1") (pintype "passive"))
      (node (ref "C375") (pin "1") (pinfunction "1_1") (pintype "passive"))
      (node (ref "C376") (pin "1") (pinfunction "1_1") (pintype "passive"))
      (node (ref "C377") (pin "1") (pinfunction "1_1") (pintype "passive"))
      (node (ref "C378") (pin "1") (pinfunction "1_1") (pintype "passive"))
      (node (ref "C379") (pin "1") (pinfunction "1_1") (pintype "passive"))
      (node (ref "C38") (pin "1") (pinfunction "1_1") (pintype "passive"))
      (node (ref "C380") (pin "1") (pinfunction "1_1") (pintype "passive"))
      (node (ref "C381") (pin "1") (pinfunction "1_1") (pintype "passive"))
      (node (ref "C382") (pin "1") (pinfunction "1_1") (pintype "passive"))
      (node (ref "C383") (pin "1") (pinfunction "1_1") (pintype "passive"))
      (node (ref "C384") (pin "1") (pinfunction "1_1") (pintype "passive"))
      (node (ref "C385") (pin "1") (pinfunction "1_1") (pintype "passive"))
      (node (ref "C386") (pin "1") (pinfunction "1_1") (pintype "passive"))
      (node (ref "C387") (pin "1") (pinfunction "1_1") (pintype "passive"))
      (node (ref "C388") (pin "1") (pinfunction "1_1") (pintype "passive"))
      (node (ref "C389") (pin "1") (pinfunction "1_1") (pintype "passive"))
      (node (ref "C39") (pin "1") (pinfunction "1_1") (pintype "passive"))
      (node (ref "C390") (pin "1") (pinfunction "1_1") (pintype "passive"))
      (node (ref "C391") (pin "1") (pinfunction "1_1") (pintype "passive"))
      (node (ref "C392") (pin "1") (pinfunction "1_1") (pintype "passive"))
      (node (ref "C393") (pin "1") (pinfunction "1_1") (pintype "passive"))
      (node (ref "C394") (pin "1") (pinfunction "1_1") (pintype "passive"))
      (node (ref "C395") (pin "1") (pinfunction "1_1") (pintype "passive"))
      (node (ref "C396") (pin "1") (pinfunction "1_1") (pintype "passive"))
      (node (ref "C397") (pin "1") (pinfunction "1_1") (pintype "passive"))
      (node (ref "C398") (pin "1") (pinfunction "1_1") (pintype "passive"))
      (node (ref "C399") (pin "1") (pinfunction "1_1") (pintype "passive"))
      (node (ref "C40") (pin "1") (pinfunction "1_1") (pintype "passive"))
      (node (ref "C400") (pin "1") (pinfunction "1_1") (pintype "passive"))
      (node (ref "C401") (pin "1") (pinfunction "1_1") (pintype "passive"))
      (node (ref "C402") (pin "1") (pinfunction "1_1") (pintype "passive"))
      (node (ref "C403") (pin "1") (pinfunction "1_1") (pintype "passive"))
      (node (ref "C404") (pin "1") (pinfunction "1_1") (pintype "passive"))
      (node (ref "C405") (pin "1") (pinfunction "1_1") (pintype "passive"))
      (node (ref "C406") (pin "1") (pinfunction "1_1") (pintype "passive"))
      (node (ref "C407") (pin "1") (pinfunction "1_1") (pintype "passive"))
      (node (ref "C408") (pin "1") (pinfunction "1_1") (pintype "passive"))
      (node (ref "C409") (pin "1") (pinfunction "1_1") (pintype "passive"))
      (node (ref "C41") (pin "1") (pinfunction "1_1") (pintype "passive"))
      (node (ref "C410") (pin "1") (pinfunction "1_1") (pintype "passive"))
      (node (ref "C411") (pin "1") (pinfunction "1_1") (pintype "passive"))
      (node (ref "C412") (pin "1") (pinfunction "1_1") (pintype "passive"))
      (node (ref "C413") (pin "1") (pinfunction "1_1") (pintype "passive"))
      (node (ref "C414") (pin "1") (pinfunction "1_1") (pintype "passive"))
      (node (ref "C415") (pin "1") (pinfunction "1_1") (pintype "passive"))
      (node (ref "C416") (pin "1") (pinfunction "1_1") (pintype "passive"))
      (node (ref "C417") (pin "1") (pinfunction "1_1") (pintype "passive"))
      (node (ref "C418") (pin "1") (pinfunction "1_1") (pintype "passive"))
      (node (ref "C419") (pin "1") (pinfunction "1_1") (pintype "passive"))
      (node (ref "C42") (pin "1") (pinfunction "1_1") (pintype "passive"))
      (node (ref "C420") (pin "1") (pinfunction "1_1") (pintype "passive"))
      (node (ref "C421") (pin "1") (pinfunction "1_1") (pintype "passive"))
      (node (ref "C422") (pin "1") (pinfunction "1_1") (pintype "passive"))
      (node (ref "C423") (pin "1") (pinfunction "1_1") (pintype "passive"))
      (node (ref "C424") (pin "1") (pinfunction "1_1") (pintype "passive"))
      (node (ref "C425") (pin "1") (pinfunction "1_1") (pintype "passive"))
      (node (ref "C426") (pin "1") (pinfunction "1_1") (pintype "passive"))
      (node (ref "C427") (pin "1") (pinfunction "1_1") (pintype "passive"))
      (node (ref "C43") (pin "1") (pinfunction "1_1") (pintype "passive"))
      (node (ref "C44") (pin "1") (pinfunction "1_1") (pintype "passive"))
      (node (ref "C45") (pin "1") (pinfunction "1_1") (pintype "passive"))
      (node (ref "C46") (pin "1") (pinfunction "1_1") (pintype "passive"))
      (node (ref "C47") (pin "1") (pinfunction "1_1") (pintype "passive"))
      (node (ref "C48") (pin "1") (pinfunction "1_1") (pintype "passive"))
      (node (ref "C49") (pin "1") (pinfunction "1_1") (pintype "passive"))
      (node (ref "C50") (pin "1") (pinfunction "1_1") (pintype "passive"))
      (node (ref "C51") (pin "1") (pinfunction "1_1") (pintype "passive"))
      (node (ref "C52") (pin "1") (pinfunction "1_1") (pintype "passive"))
      (node (ref "C53") (pin "1") (pinfunction "1_1") (pintype "passive"))
      (node (ref "C54") (pin "1") (pinfunction "1_1") (pintype "passive"))
      (node (ref "C55") (pin "1") (pinfunction "1_1") (pintype "passive"))
      (node (ref "C56") (pin "2") (pinfunction "2_2") (pintype "passive"))
      (node (ref "C57") (pin "2") (pinfunction "2_2") (pintype "passive"))
      (node (ref "C58") (pin "2") (pinfunction "2_2") (pintype "passive"))
      (node (ref "C59") (pin "2") (pinfunction "2_2") (pintype "passive"))
      (node (ref "C64") (pin "1") (pinfunction "1_1") (pintype "passive"))
      (node (ref "C65") (pin "1") (pinfunction "1_1") (pintype "passive"))
      (node (ref "C66") (pin "1") (pinfunction "1_1") (pintype "passive"))
      (node (ref "C67") (pin "1") (pinfunction "1_1") (pintype "passive"))
      (node (ref "C68") (pin "1") (pinfunction "1_1") (pintype "passive"))
      (node (ref "C69") (pin "1") (pinfunction "1_1") (pintype "passive"))
      (node (ref "C70") (pin "1") (pinfunction "1_1") (pintype "passive"))
      (node (ref "C71") (pin "1") (pinfunction "1_1") (pintype "passive"))
      (node (ref "C72") (pin "1") (pinfunction "1_1") (pintype "passive"))
      (node (ref "C73") (pin "1") (pinfunction "1_1") (pintype "passive"))
      (node (ref "C74") (pin "1") (pinfunction "1_1") (pintype "passive"))
      (node (ref "C75") (pin "1") (pinfunction "1_1") (pintype "passive"))
      (node (ref "C76") (pin "1") (pinfunction "1_1") (pintype "passive"))
      (node (ref "C77") (pin "1") (pinfunction "1_1") (pintype "passive"))
      (node (ref "C78") (pin "1") (pinfunction "1_1") (pintype "passive"))
      (node (ref "C79") (pin "1") (pinfunction "1_1") (pintype "passive"))
      (node (ref "C80") (pin "1") (pinfunction "1_1") (pintype "passive"))
      (node (ref "C81") (pin "1") (pinfunction "1_1") (pintype "passive"))
      (node (ref "C82") (pin "1") (pinfunction "1_1") (pintype "passive"))
      (node (ref "C83") (pin "1") (pinfunction "1_1") (pintype "passive"))
      (node (ref "C84") (pin "1") (pinfunction "1_1") (pintype "passive"))
      (node (ref "C85") (pin "1") (pinfunction "1_1") (pintype "passive"))
      (node (ref "C86") (pin "1") (pinfunction "1_1") (pintype "passive"))
      (node (ref "C87") (pin "1") (pinfunction "1_1") (pintype "passive"))
      (node (ref "C88") (pin "2") (pinfunction "2_2") (pintype "passive"))
      (node (ref "C89") (pin "2") (pinfunction "2_2") (pintype "passive"))
      (node (ref "C90") (pin "2") (pinfunction "2_2") (pintype "passive"))
      (node (ref "C91") (pin "2") (pinfunction "2_2") (pintype "passive"))
      (node (ref "C96") (pin "1") (pinfunction "1_1") (pintype "passive"))
      (node (ref "C97") (pin "1") (pinfunction "1_1") (pintype "passive"))
      (node (ref "C98") (pin "1") (pinfunction "1_1") (pintype "passive"))
      (node (ref "C99") (pin "1") (pinfunction "1_1") (pintype "passive"))
      (node (ref "Q10") (pin "1") (pinfunction "S_1") (pintype "passive"))
      (node (ref "Q10") (pin "2") (pinfunction "S_2") (pintype "passive"))
      (node (ref "Q10") (pin "3") (pinfunction "S_3") (pintype "passive"))
      (node (ref "Q11") (pin "1") (pinfunction "S_1") (pintype "passive"))
      (node (ref "Q11") (pin "2") (pinfunction "S_2") (pintype "passive"))
      (node (ref "Q11") (pin "3") (pinfunction "S_3") (pintype "passive"))
      (node (ref "Q12") (pin "1") (pinfunction "S_1") (pintype "passive"))
      (node (ref "Q12") (pin "2") (pinfunction "S_2") (pintype "passive"))
      (node (ref "Q12") (pin "3") (pinfunction "S_3") (pintype "passive"))
      (node (ref "Q17") (pin "1") (pinfunction "S_1") (pintype "passive"))
      (node (ref "Q17") (pin "2") (pinfunction "S_2") (pintype "passive"))
      (node (ref "Q17") (pin "3") (pinfunction "S_3") (pintype "passive"))
      (node (ref "Q18") (pin "1") (pinfunction "S_1") (pintype "passive"))
      (node (ref "Q18") (pin "2") (pinfunction "S_2") (pintype "passive"))
      (node (ref "Q18") (pin "3") (pinfunction "S_3") (pintype "passive"))
      (node (ref "Q19") (pin "1") (pinfunction "S_1") (pintype "passive"))
      (node (ref "Q19") (pin "2") (pinfunction "S_2") (pintype "passive"))
      (node (ref "Q19") (pin "3") (pinfunction "S_3") (pintype "passive"))
      (node (ref "Q20") (pin "1") (pinfunction "S_1") (pintype "passive"))
      (node (ref "Q20") (pin "2") (pinfunction "S_2") (pintype "passive"))
      (node (ref "Q20") (pin "3") (pinfunction "S_3") (pintype "passive"))
      (node (ref "Q21") (pin "1") (pinfunction "S_1") (pintype "passive"))
      (node (ref "Q21") (pin "2") (pinfunction "S_2") (pintype "passive"))
      (node (ref "Q21") (pin "3") (pinfunction "S_3") (pintype "passive"))
      (node (ref "Q22") (pin "1") (pinfunction "S_1") (pintype "passive"))
      (node (ref "Q22") (pin "2") (pinfunction "S_2") (pintype "passive"))
      (node (ref "Q22") (pin "3") (pinfunction "S_3") (pintype "passive"))
      (node (ref "Q23") (pin "1") (pinfunction "S_1") (pintype "passive"))
      (node (ref "Q23") (pin "2") (pinfunction "S_2") (pintype "passive"))
      (node (ref "Q23") (pin "3") (pinfunction "S_3") (pintype "passive"))
      (node (ref "Q24") (pin "1") (pinfunction "S_1") (pintype "passive"))
      (node (ref "Q24") (pin "2") (pinfunction "S_2") (pintype "passive"))
      (node (ref "Q24") (pin "3") (pinfunction "S_3") (pintype "passive"))
      (node (ref "Q29") (pin "1") (pinfunction "S_1") (pintype "passive"))
      (node (ref "Q29") (pin "2") (pinfunction "S_2") (pintype "passive"))
      (node (ref "Q29") (pin "3") (pinfunction "S_3") (pintype "passive"))
      (node (ref "Q30") (pin "1") (pinfunction "S_1") (pintype "passive"))
      (node (ref "Q30") (pin "2") (pinfunction "S_2") (pintype "passive"))
      (node (ref "Q30") (pin "3") (pinfunction "S_3") (pintype "passive"))
      (node (ref "Q31") (pin "1") (pinfunction "S_1") (pintype "passive"))
      (node (ref "Q31") (pin "2") (pinfunction "S_2") (pintype "passive"))
      (node (ref "Q31") (pin "3") (pinfunction "S_3") (pintype "passive"))
      (node (ref "Q32") (pin "1") (pinfunction "S_1") (pintype "passive"))
      (node (ref "Q32") (pin "2") (pinfunction "S_2") (pintype "passive"))
      (node (ref "Q32") (pin "3") (pinfunction "S_3") (pintype "passive"))
      (node (ref "Q33") (pin "1") (pinfunction "S_1") (pintype "passive"))
      (node (ref "Q33") (pin "2") (pinfunction "S_2") (pintype "passive"))
      (node (ref "Q33") (pin "3") (pinfunction "S_3") (pintype "passive"))
      (node (ref "Q34") (pin "1") (pinfunction "S_1") (pintype "passive"))
      (node (ref "Q34") (pin "2") (pinfunction "S_2") (pintype "passive"))
      (node (ref "Q34") (pin "3") (pinfunction "S_3") (pintype "passive"))
      (node (ref "Q35") (pin "1") (pinfunction "S_1") (pintype "passive"))
      (node (ref "Q35") (pin "2") (pinfunction "S_2") (pintype "passive"))
      (node (ref "Q35") (pin "3") (pinfunction "S_3") (pintype "passive"))
      (node (ref "Q36") (pin "1") (pinfunction "S_1") (pintype "passive"))
      (node (ref "Q36") (pin "2") (pinfunction "S_2") (pintype "passive"))
      (node (ref "Q36") (pin "3") (pinfunction "S_3") (pintype "passive"))
      (node (ref "Q41") (pin "1") (pinfunction "S_1") (pintype "passive"))
      (node (ref "Q41") (pin "2") (pinfunction "S_2") (pintype "passive"))
      (node (ref "Q41") (pin "3") (pinfunction "S_3") (pintype "passive"))
      (node (ref "Q42") (pin "1") (pinfunction "S_1") (pintype "passive"))
      (node (ref "Q42") (pin "2") (pinfunction "S_2") (pintype "passive"))
      (node (ref "Q42") (pin "3") (pinfunction "S_3") (pintype "passive"))
      (node (ref "Q43") (pin "1") (pinfunction "S_1") (pintype "passive"))
      (node (ref "Q43") (pin "2") (pinfunction "S_2") (pintype "passive"))
      (node (ref "Q43") (pin "3") (pinfunction "S_3") (pintype "passive"))
      (node (ref "Q44") (pin "1") (pinfunction "S_1") (pintype "passive"))
      (node (ref "Q44") (pin "2") (pinfunction "S_2") (pintype "passive"))
      (node (ref "Q44") (pin "3") (pinfunction "S_3") (pintype "passive"))
      (node (ref "Q45") (pin "1") (pinfunction "S_1") (pintype "passive"))
      (node (ref "Q45") (pin "2") (pinfunction "S_2") (pintype "passive"))
      (node (ref "Q45") (pin "3") (pinfunction "S_3") (pintype "passive"))
      (node (ref "Q46") (pin "1") (pinfunction "S_1") (pintype "passive"))
      (node (ref "Q46") (pin "2") (pinfunction "S_2") (pintype "passive"))
      (node (ref "Q46") (pin "3") (pinfunction "S_3") (pintype "passive"))
      (node (ref "Q47") (pin "1") (pinfunction "S_1") (pintype "passive"))
      (node (ref "Q47") (pin "2") (pinfunction "S_2") (pintype "passive"))
      (node (ref "Q47") (pin "3") (pinfunction "S_3") (pintype "passive"))
      (node (ref "Q48") (pin "1") (pinfunction "S_1") (pintype "passive"))
      (node (ref "Q48") (pin "2") (pinfunction "S_2") (pintype "passive"))
      (node (ref "Q48") (pin "3") (pinfunction "S_3") (pintype "passive"))
      (node (ref "Q5") (pin "1") (pinfunction "S_1") (pintype "passive"))
      (node (ref "Q5") (pin "2") (pinfunction "S_2") (pintype "passive"))
      (node (ref "Q5") (pin "3") (pinfunction "S_3") (pintype "passive"))
      (node (ref "Q6") (pin "1") (pinfunction "S_1") (pintype "passive"))
      (node (ref "Q6") (pin "2") (pinfunction "S_2") (pintype "passive"))
      (node (ref "Q6") (pin "3") (pinfunction "S_3") (pintype "passive"))
      (node (ref "Q7") (pin "1") (pinfunction "S_1") (pintype "passive"))
      (node (ref "Q7") (pin "2") (pinfunction "S_2") (pintype "passive"))
      (node (ref "Q7") (pin "3") (pinfunction "S_3") (pintype "passive"))
      (node (ref "Q8") (pin "1") (pinfunction "S_1") (pintype "passive"))
      (node (ref "Q8") (pin "2") (pinfunction "S_2") (pintype "passive"))
      (node (ref "Q8") (pin "3") (pinfunction "S_3") (pintype "passive"))
      (node (ref "Q9") (pin "1") (pinfunction "S_1") (pintype "passive"))
      (node (ref "Q9") (pin "2") (pinfunction "S_2") (pintype "passive"))
      (node (ref "Q9") (pin "3") (pinfunction "S_3") (pintype "passive"))
      (node (ref "U11") (pin "4") (pinfunction "GND_4") (pintype "passive"))
      (node (ref "U11") (pin "9") (pinfunction "EP_9") (pintype "passive"))
      (node (ref "U12") (pin "4") (pinfunction "GND_4") (pintype "passive"))
      (node (ref "U12") (pin "9") (pinfunction "EP_9") (pintype "passive"))
      (node (ref "U13") (pin "4") (pinfunction "GND_4") (pintype "passive"))
      (node (ref "U13") (pin "9") (pinfunction "EP_9") (pintype "passive"))
      (node (ref "U14") (pin "4") (pinfunction "GND_4") (pintype "passive"))
      (node (ref "U14") (pin "9") (pinfunction "EP_9") (pintype "passive"))
      (node (ref "U15") (pin "4") (pinfunction "GND_4") (pintype "passive"))
      (node (ref "U15") (pin "9") (pinfunction "EP_9") (pintype "passive"))
      (node (ref "U16") (pin "4") (pinfunction "GND_4") (pintype "passive"))
      (node (ref "U16") (pin "9") (pinfunction "EP_9") (pintype "passive"))
      (node (ref "U17") (pin "4") (pinfunction "GND_4") (pintype "passive"))
      (node (ref "U17") (pin "9") (pinfunction "EP_9") (pintype "passive"))
      (node (ref "U18") (pin "4") (pinfunction "GND_4") (pintype "passive"))
      (node (ref "U18") (pin "9") (pinfunction "EP_9") (pintype "passive"))
      (node (ref "U19") (pin "4") (pinfunction "GND_4") (pintype "passive"))
      (node (ref "U19") (pin "9") (pinfunction "EP_9") (pintype "passive"))
      (node (ref "U20") (pin "4") (pinfunction "GND_4") (pintype "passive"))
      (node (ref "U20") (pin "9") (pinfunction "EP_9") (pintype "passive"))
      (node (ref "U21") (pin "4") (pinfunction "GND_4") (pintype "passive"))
      (node (ref "U21") (pin "9") (pinfunction "EP_9") (pintype "passive"))
      (node (ref "U22") (pin "4") (pinfunction "GND_4") (pintype "passive"))
      (node (ref "U22") (pin "9") (pinfunction "EP_9") (pintype "passive"))
      (node (ref "U23") (pin "4") (pinfunction "GND_4") (pintype "passive"))
      (node (ref "U23") (pin "9") (pinfunction "EP_9") (pintype "passive"))
      (node (ref "U24") (pin "4") (pinfunction "GND_4") (pintype "passive"))
      (node (ref "U24") (pin "9") (pinfunction "EP_9") (pintype "passive"))
      (node (ref "U25") (pin "4") (pinfunction "GND_4") (pintype "passive"))
      (node (ref "U25") (pin "9") (pinfunction "EP_9") (pintype "passive"))
      (node (ref "U26") (pin "4") (pinfunction "GND_4") (pintype "passive"))
      (node (ref "U26") (pin "9") (pinfunction "EP_9") (pintype "passive"))
    )
    (net (code "78") (name "Net-(L1-Pad1)") (class "Default")
      (node (ref "L1") (pin "1") (pinfunction "1_1") (pintype "passive"))
      (node (ref "Q6") (pin "7") (pinfunction "D_7") (pintype "passive"))
    )
    (net (code "79") (name "Net-(Q1-S-Pad1)") (class "Default")
      (node (ref "Q1") (pin "1") (pinfunction "S_1") (pintype "passive"))
      (node (ref "Q5") (pin "7") (pinfunction "D_7") (pintype "passive"))
    )
    (net (code "80") (name "Net-(Q1-S-Pad2)") (class "Default")
      (node (ref "Q1") (pin "2") (pinfunction "S_2") (pintype "passive"))
      (node (ref "Q5") (pin "6") (pinfunction "D_6") (pintype "passive"))
    )
    (net (code "81") (name "Net-(Q1-S-Pad3)") (class "Default")
      (node (ref "Q1") (pin "3") (pinfunction "S_3") (pintype "passive"))
      (node (ref "Q5") (pin "5") (pinfunction "D_5") (pintype "passive"))
    )
  )
)
